# DuetReference.net
KiCad netlist of a schematic drawn in EAGLE
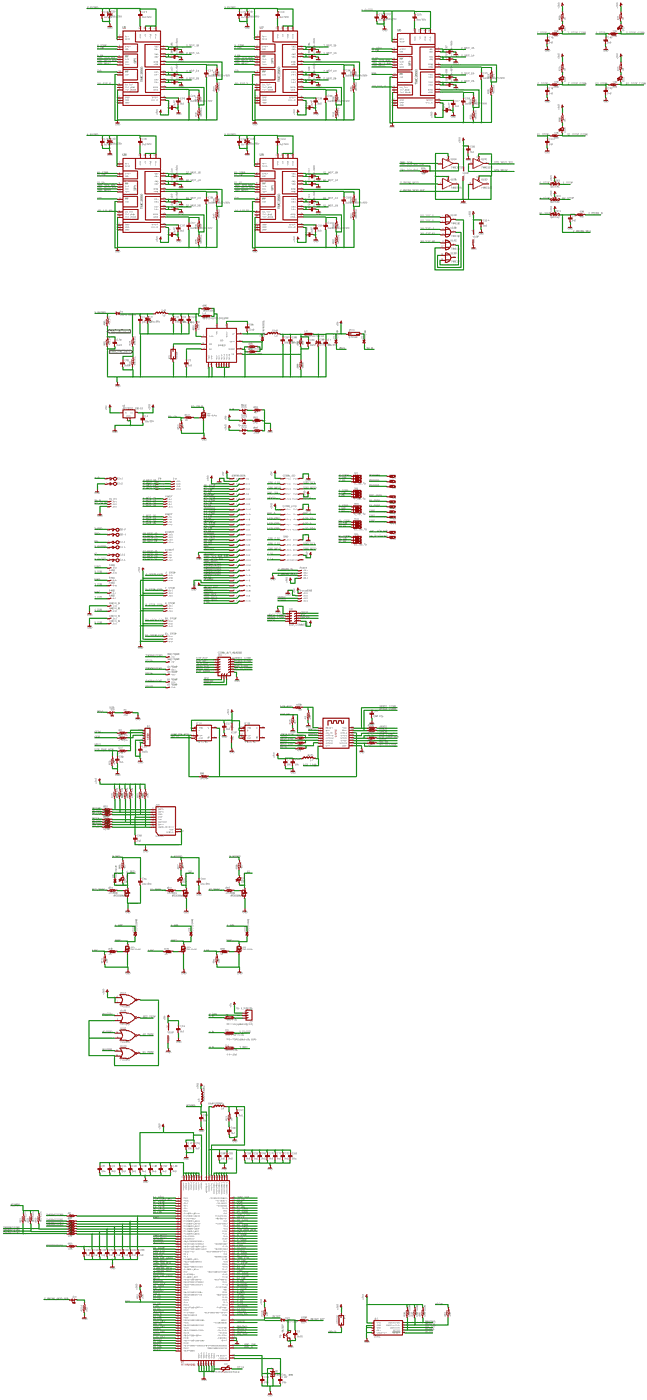
[diagram p0: schematic, sheet 1, overview]
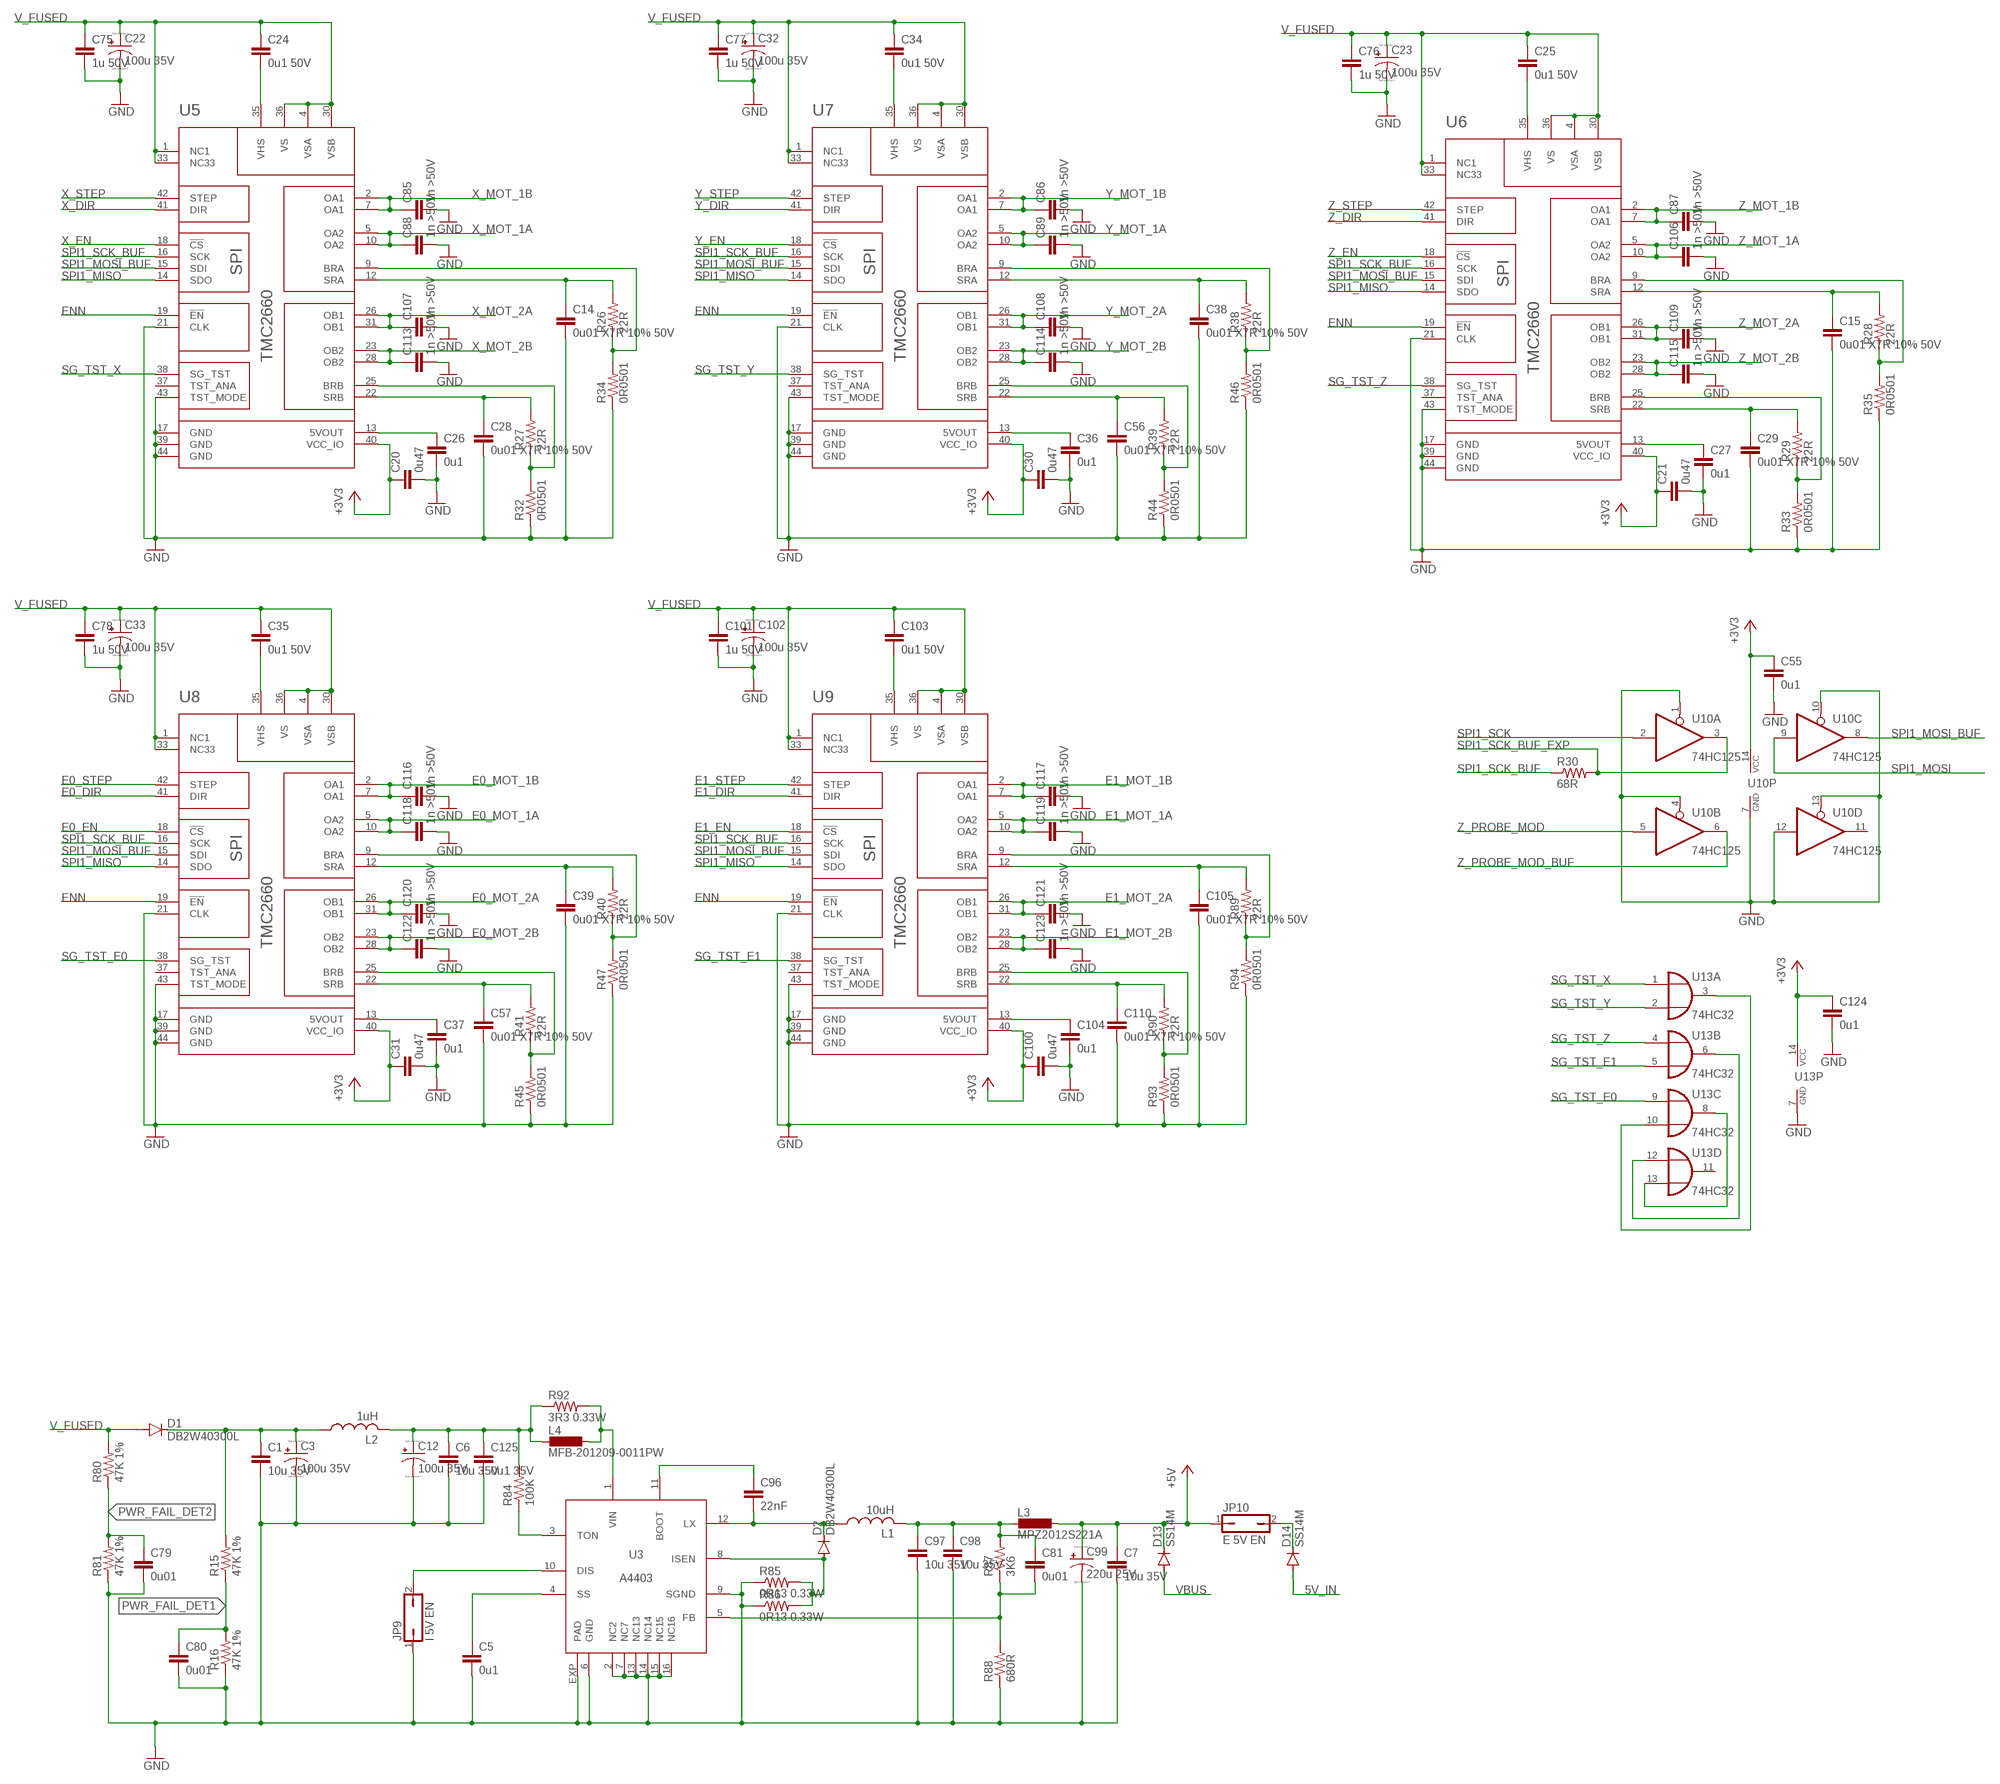
[diagram p1: schematic, sheet 1, part 1 of 5]
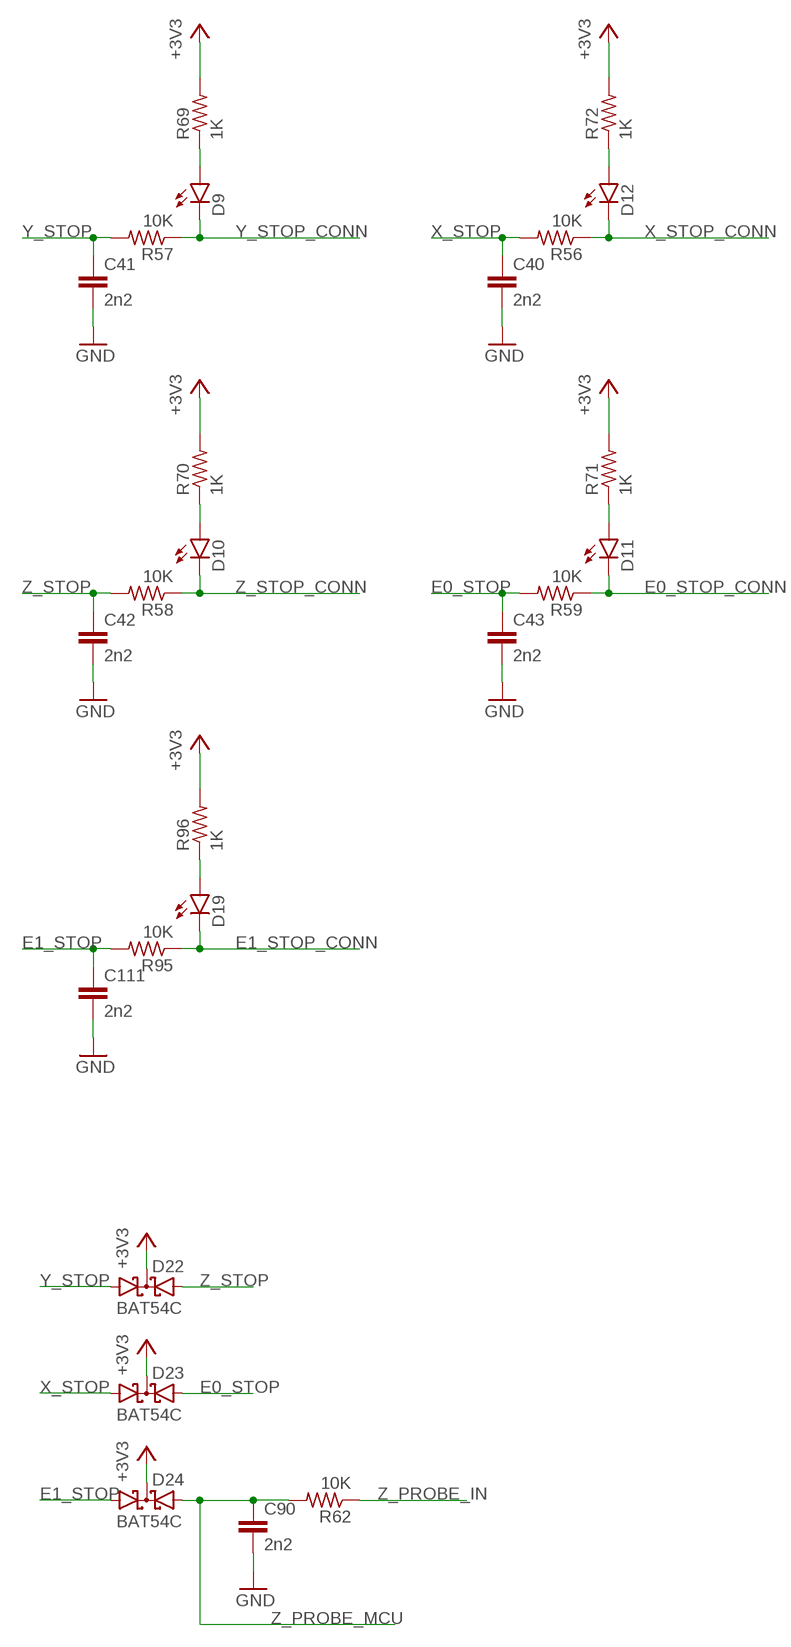
[diagram p2: schematic, sheet 1, part 2 of 5]
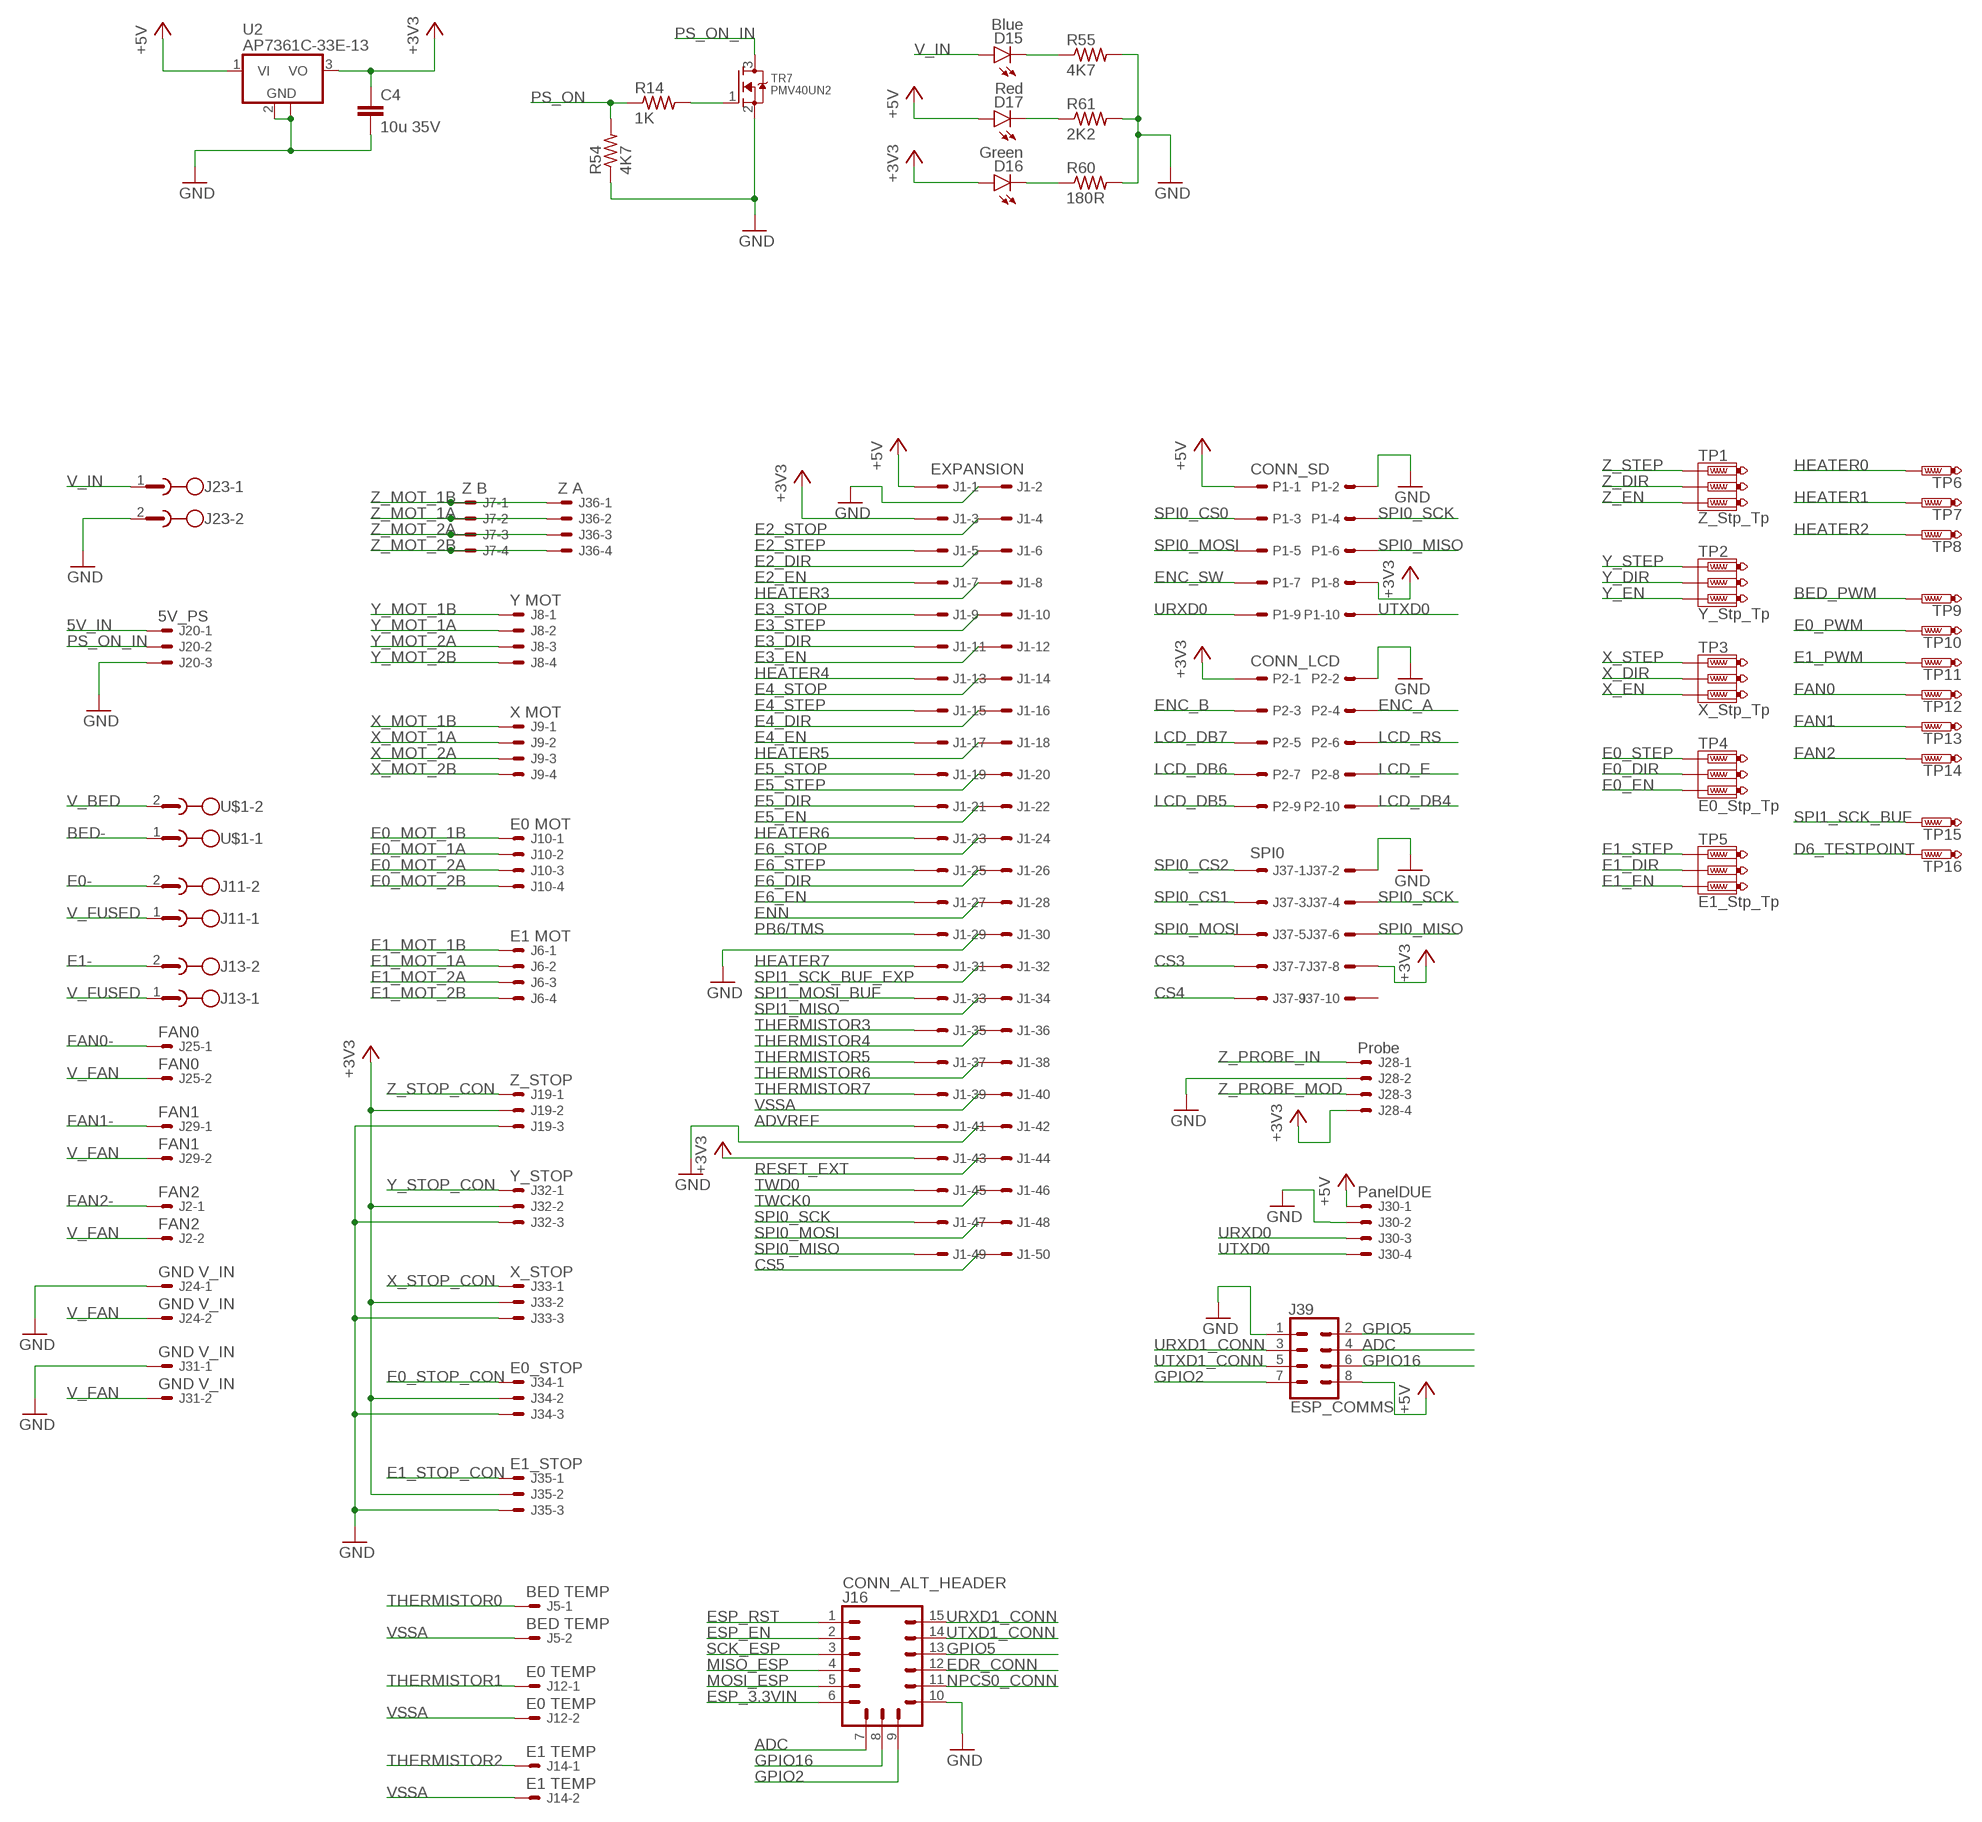
[diagram p3: schematic, sheet 1, part 3 of 5]
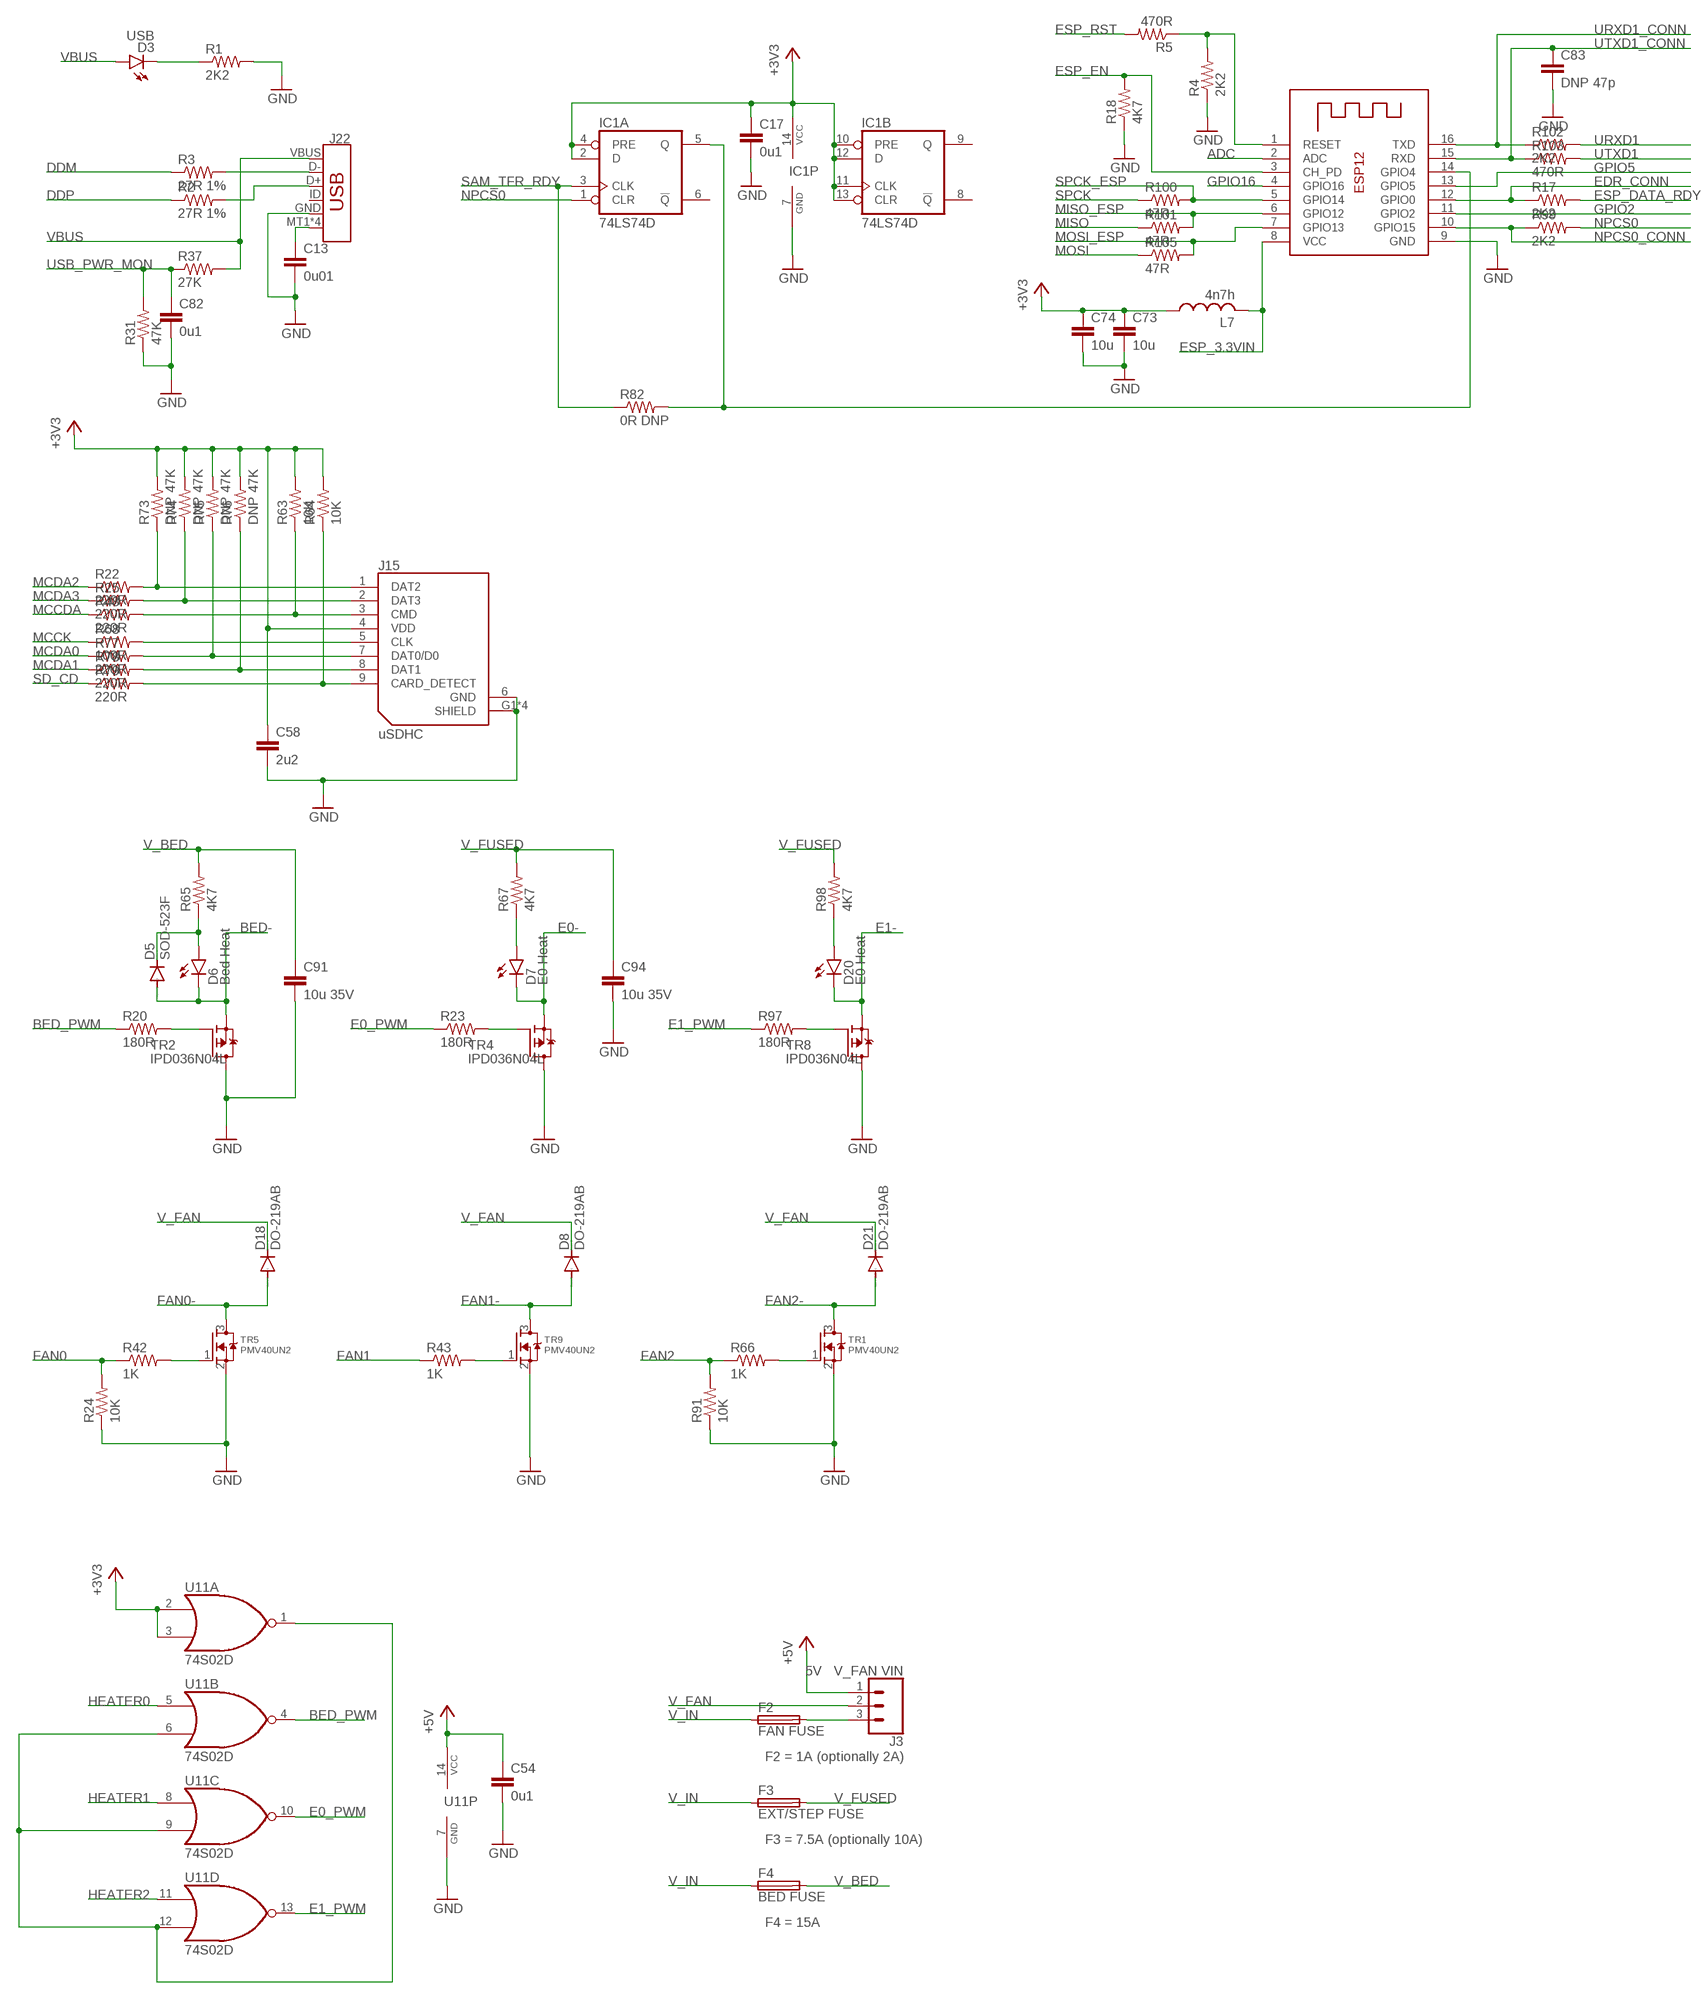
[diagram p4: schematic, sheet 1, part 4 of 5]
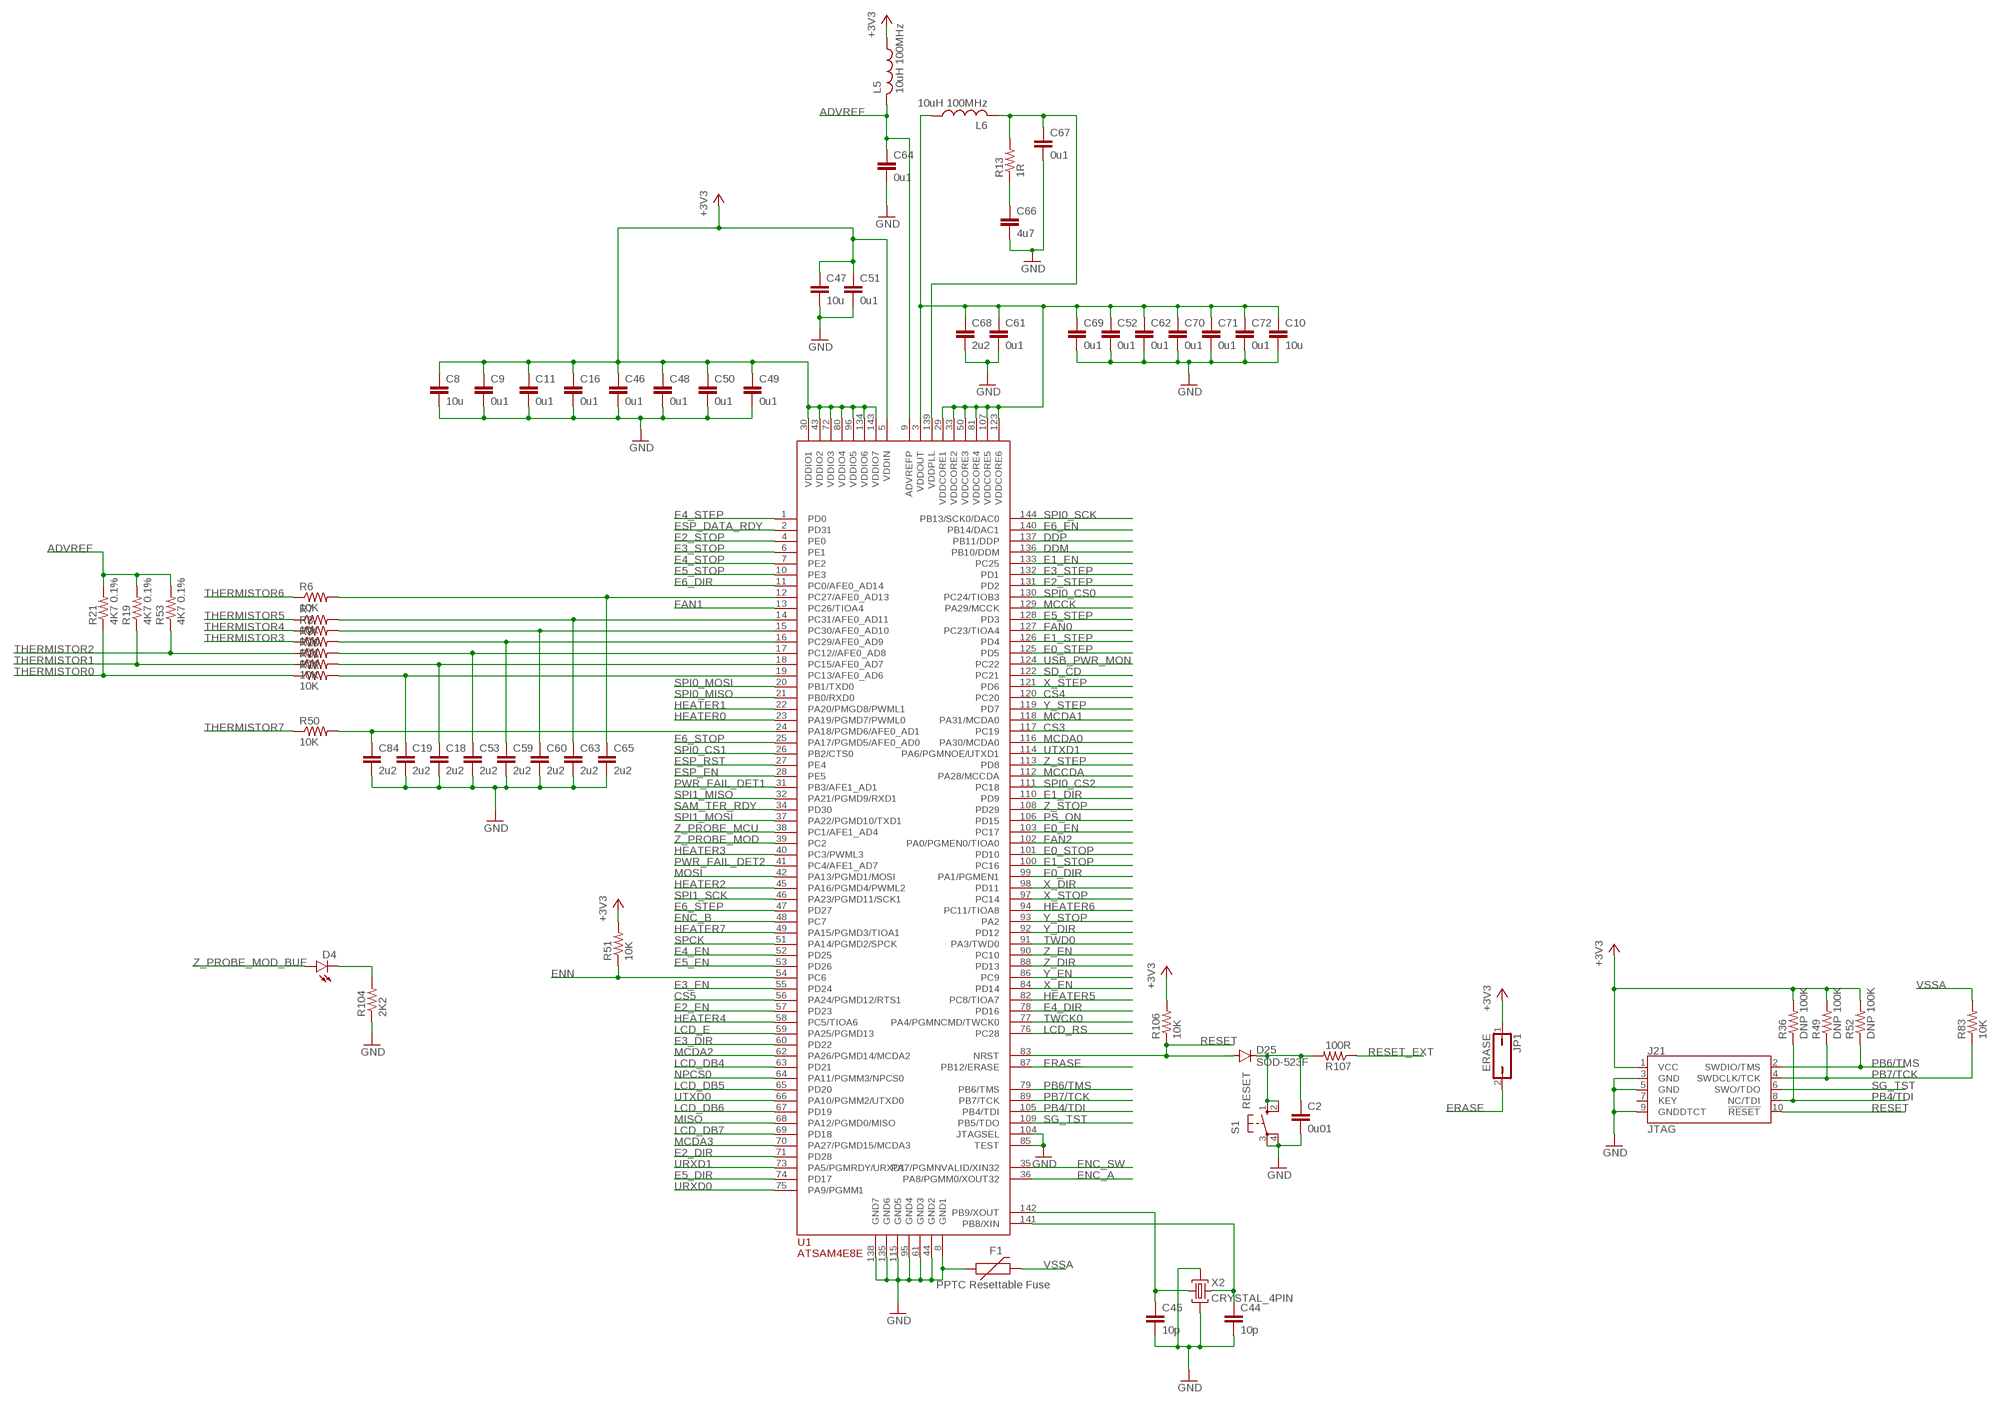
[diagram p5: schematic, sheet 1, part 5 of 5]

(export (version "E")
  (design (tool "Eeschema 10.0.6"))
  (components
    (comp (ref "C1")
      (value "10u 35V")
      (footprint "eagle-import:C0805")
      (libsource (lib "eagle-import") (part "C-EUC0805"))
    )
    (comp (ref "C2")
      (value "0u01")
      (footprint "eagle-import:C0805")
      (libsource (lib "eagle-import") (part "C-EUC0805"))
    )
    (comp (ref "C3")
      (value "100u 35V")
      (footprint "eagle-import:PANASONIC_D")
      (libsource (lib "eagle-import") (part "CPOL-USD"))
    )
    (comp (ref "C4")
      (value "10u 35V")
      (footprint "eagle-import:C0805")
      (libsource (lib "eagle-import") (part "C-EUC0805"))
    )
    (comp (ref "C5")
      (value "0u1")
      (footprint "eagle-import:C0805")
      (libsource (lib "eagle-import") (part "C-EUC0805"))
    )
    (comp (ref "C6")
      (value "10u 35V")
      (footprint "eagle-import:C0805")
      (libsource (lib "eagle-import") (part "C-EUC0805"))
    )
    (comp (ref "C7")
      (value "10u 35V")
      (footprint "eagle-import:C0805")
      (libsource (lib "eagle-import") (part "C-EUC0805"))
    )
    (comp (ref "C8")
      (value "10u")
      (footprint "eagle-import:C0805")
      (libsource (lib "eagle-import") (part "C-EUC0805"))
    )
    (comp (ref "C9")
      (value "0u1")
      (footprint "eagle-import:C0805")
      (libsource (lib "eagle-import") (part "C-EUC0805"))
    )
    (comp (ref "C10")
      (value "10u")
      (footprint "eagle-import:C0805")
      (libsource (lib "eagle-import") (part "C-EUC0805"))
    )
    (comp (ref "C11")
      (value "0u1")
      (footprint "eagle-import:C0805")
      (libsource (lib "eagle-import") (part "C-EUC0805"))
    )
    (comp (ref "C12")
      (value "100u 35V")
      (footprint "eagle-import:PANASONIC_D")
      (libsource (lib "eagle-import") (part "CPOL-USD"))
    )
    (comp (ref "C13")
      (value "0u01")
      (footprint "eagle-import:C0805")
      (libsource (lib "eagle-import") (part "C-EUC0805"))
    )
    (comp (ref "C14")
      (value "0u01 X7R 10% 50V")
      (footprint "eagle-import:C0805")
      (libsource (lib "eagle-import") (part "C-EUC0805"))
    )
    (comp (ref "C15")
      (value "0u01 X7R 10% 50V")
      (footprint "eagle-import:C0805")
      (libsource (lib "eagle-import") (part "C-EUC0805"))
    )
    (comp (ref "C16")
      (value "0u1")
      (footprint "eagle-import:C0805")
      (libsource (lib "eagle-import") (part "C-EUC0805"))
    )
    (comp (ref "C17")
      (value "0u1")
      (footprint "eagle-import:C0805")
      (libsource (lib "eagle-import") (part "C-EUC0805"))
    )
    (comp (ref "C18")
      (value "2u2")
      (footprint "eagle-import:C0805")
      (libsource (lib "eagle-import") (part "C-EUC0805"))
    )
    (comp (ref "C19")
      (value "2u2")
      (footprint "eagle-import:C0805")
      (libsource (lib "eagle-import") (part "C-EUC0805"))
    )
    (comp (ref "C20")
      (value "0u47")
      (footprint "eagle-import:C0805")
      (libsource (lib "eagle-import") (part "C-EUC0805"))
    )
    (comp (ref "C21")
      (value "0u47")
      (footprint "eagle-import:C0805")
      (libsource (lib "eagle-import") (part "C-EUC0805"))
    )
    (comp (ref "C22")
      (value "100u 35V")
      (footprint "eagle-import:PANASONIC_D")
      (libsource (lib "eagle-import") (part "CPOL-USD"))
    )
    (comp (ref "C23")
      (value "100u 35V")
      (footprint "eagle-import:PANASONIC_D")
      (libsource (lib "eagle-import") (part "CPOL-USD"))
    )
    (comp (ref "C24")
      (value "0u1 50V")
      (footprint "eagle-import:C0805")
      (libsource (lib "eagle-import") (part "C-EUC0805"))
    )
    (comp (ref "C25")
      (value "0u1 50V")
      (footprint "eagle-import:C0805")
      (libsource (lib "eagle-import") (part "C-EUC0805"))
    )
    (comp (ref "C26")
      (value "0u1")
      (footprint "eagle-import:C0805")
      (libsource (lib "eagle-import") (part "C-EUC0805"))
    )
    (comp (ref "C27")
      (value "0u1")
      (footprint "eagle-import:C0805")
      (libsource (lib "eagle-import") (part "C-EUC0805"))
    )
    (comp (ref "C28")
      (value "0u01 X7R 10% 50V")
      (footprint "eagle-import:C0805")
      (libsource (lib "eagle-import") (part "C-EUC0805"))
    )
    (comp (ref "C29")
      (value "0u01 X7R 10% 50V")
      (footprint "eagle-import:C0805")
      (libsource (lib "eagle-import") (part "C-EUC0805"))
    )
    (comp (ref "C30")
      (value "0u47")
      (footprint "eagle-import:C0805")
      (libsource (lib "eagle-import") (part "C-EUC0805"))
    )
    (comp (ref "C31")
      (value "0u47")
      (footprint "eagle-import:C0805")
      (libsource (lib "eagle-import") (part "C-EUC0805"))
    )
    (comp (ref "C32")
      (value "100u 35V")
      (footprint "eagle-import:PANASONIC_D")
      (libsource (lib "eagle-import") (part "CPOL-USD"))
    )
    (comp (ref "C33")
      (value "100u 35V")
      (footprint "eagle-import:PANASONIC_D")
      (libsource (lib "eagle-import") (part "CPOL-USD"))
    )
    (comp (ref "C34")
      (value "0u1 50V")
      (footprint "eagle-import:C0805")
      (libsource (lib "eagle-import") (part "C-EUC0805"))
    )
    (comp (ref "C35")
      (value "0u1 50V")
      (footprint "eagle-import:C0805")
      (libsource (lib "eagle-import") (part "C-EUC0805"))
    )
    (comp (ref "C36")
      (value "0u1")
      (footprint "eagle-import:C0805")
      (libsource (lib "eagle-import") (part "C-EUC0805"))
    )
    (comp (ref "C37")
      (value "0u1")
      (footprint "eagle-import:C0805")
      (libsource (lib "eagle-import") (part "C-EUC0805"))
    )
    (comp (ref "C38")
      (value "0u01 X7R 10% 50V")
      (footprint "eagle-import:C0805")
      (libsource (lib "eagle-import") (part "C-EUC0805"))
    )
    (comp (ref "C39")
      (value "0u01 X7R 10% 50V")
      (footprint "eagle-import:C0805")
      (libsource (lib "eagle-import") (part "C-EUC0805"))
    )
    (comp (ref "C40")
      (value "2n2")
      (footprint "eagle-import:C0805")
      (libsource (lib "eagle-import") (part "C-EUC0805"))
    )
    (comp (ref "C41")
      (value "2n2")
      (footprint "eagle-import:C0805")
      (libsource (lib "eagle-import") (part "C-EUC0805"))
    )
    (comp (ref "C42")
      (value "2n2")
      (footprint "eagle-import:C0805")
      (libsource (lib "eagle-import") (part "C-EUC0805"))
    )
    (comp (ref "C43")
      (value "2n2")
      (footprint "eagle-import:C0805")
      (libsource (lib "eagle-import") (part "C-EUC0805"))
    )
    (comp (ref "C44")
      (value "10p")
      (footprint "eagle-import:C0805")
      (libsource (lib "eagle-import") (part "C-EUC0805"))
    )
    (comp (ref "C45")
      (value "10p")
      (footprint "eagle-import:C0805")
      (libsource (lib "eagle-import") (part "C-EUC0805"))
    )
    (comp (ref "C46")
      (value "0u1")
      (footprint "eagle-import:C0805")
      (libsource (lib "eagle-import") (part "C-EUC0805"))
    )
    (comp (ref "C47")
      (value "10u")
      (footprint "eagle-import:C0805")
      (libsource (lib "eagle-import") (part "C-EUC0805"))
    )
    (comp (ref "C48")
      (value "0u1")
      (footprint "eagle-import:C0805")
      (libsource (lib "eagle-import") (part "C-EUC0805"))
    )
    (comp (ref "C49")
      (value "0u1")
      (footprint "eagle-import:C0805")
      (libsource (lib "eagle-import") (part "C-EUC0805"))
    )
    (comp (ref "C50")
      (value "0u1")
      (footprint "eagle-import:C0805")
      (libsource (lib "eagle-import") (part "C-EUC0805"))
    )
    (comp (ref "C51")
      (value "0u1")
      (footprint "eagle-import:C0805")
      (libsource (lib "eagle-import") (part "C-EUC0805"))
    )
    (comp (ref "C52")
      (value "0u1")
      (footprint "eagle-import:C0805")
      (libsource (lib "eagle-import") (part "C-EUC0805"))
    )
    (comp (ref "C53")
      (value "2u2")
      (footprint "eagle-import:C0805")
      (libsource (lib "eagle-import") (part "C-EUC0805"))
    )
    (comp (ref "C54")
      (value "0u1")
      (footprint "eagle-import:C0805")
      (libsource (lib "eagle-import") (part "C-EUC0805"))
    )
    (comp (ref "C55")
      (value "0u1")
      (footprint "eagle-import:C0805")
      (libsource (lib "eagle-import") (part "C-EUC0805"))
    )
    (comp (ref "C56")
      (value "0u01 X7R 10% 50V")
      (footprint "eagle-import:C0805")
      (libsource (lib "eagle-import") (part "C-EUC0805"))
    )
    (comp (ref "C57")
      (value "0u01 X7R 10% 50V")
      (footprint "eagle-import:C0805")
      (libsource (lib "eagle-import") (part "C-EUC0805"))
    )
    (comp (ref "C58")
      (value "2u2")
      (footprint "eagle-import:C0805")
      (libsource (lib "eagle-import") (part "C-EUC0805"))
    )
    (comp (ref "C59")
      (value "2u2")
      (footprint "eagle-import:C0805")
      (libsource (lib "eagle-import") (part "C-EUC0805"))
    )
    (comp (ref "C60")
      (value "2u2")
      (footprint "eagle-import:C0805")
      (libsource (lib "eagle-import") (part "C-EUC0805"))
    )
    (comp (ref "C61")
      (value "0u1")
      (footprint "eagle-import:C0805")
      (libsource (lib "eagle-import") (part "C-EUC0805"))
    )
    (comp (ref "C62")
      (value "0u1")
      (footprint "eagle-import:C0805")
      (libsource (lib "eagle-import") (part "C-EUC0805"))
    )
    (comp (ref "C63")
      (value "2u2")
      (footprint "eagle-import:C0805")
      (libsource (lib "eagle-import") (part "C-EUC0805"))
    )
    (comp (ref "C64")
      (value "0u1")
      (footprint "eagle-import:C0805")
      (libsource (lib "eagle-import") (part "C-EUC0805"))
    )
    (comp (ref "C65")
      (value "2u2")
      (footprint "eagle-import:C0805")
      (libsource (lib "eagle-import") (part "C-EUC0805"))
    )
    (comp (ref "C66")
      (value "4u7")
      (footprint "eagle-import:C0805")
      (libsource (lib "eagle-import") (part "C-EUC0805"))
    )
    (comp (ref "C67")
      (value "0u1")
      (footprint "eagle-import:C0805")
      (libsource (lib "eagle-import") (part "C-EUC0805"))
    )
    (comp (ref "C68")
      (value "2u2")
      (footprint "eagle-import:C0805")
      (libsource (lib "eagle-import") (part "C-EUC0805"))
    )
    (comp (ref "C69")
      (value "0u1")
      (footprint "eagle-import:C0805")
      (libsource (lib "eagle-import") (part "C-EUC0805"))
    )
    (comp (ref "C70")
      (value "0u1")
      (footprint "eagle-import:C0805")
      (libsource (lib "eagle-import") (part "C-EUC0805"))
    )
    (comp (ref "C71")
      (value "0u1")
      (footprint "eagle-import:C0805")
      (libsource (lib "eagle-import") (part "C-EUC0805"))
    )
    (comp (ref "C72")
      (value "0u1")
      (footprint "eagle-import:C0805")
      (libsource (lib "eagle-import") (part "C-EUC0805"))
    )
    (comp (ref "C73")
      (value "10u")
      (footprint "eagle-import:C0805")
      (libsource (lib "eagle-import") (part "C-EUC0805"))
    )
    (comp (ref "C74")
      (value "10u")
      (footprint "eagle-import:C0805")
      (libsource (lib "eagle-import") (part "C-EUC0805"))
    )
    (comp (ref "C75")
      (value "1u 50V")
      (footprint "eagle-import:C0805")
      (libsource (lib "eagle-import") (part "C-EUC0805"))
    )
    (comp (ref "C76")
      (value "1u 50V")
      (footprint "eagle-import:C0805")
      (libsource (lib "eagle-import") (part "C-EUC0805"))
    )
    (comp (ref "C77")
      (value "1u 50V")
      (footprint "eagle-import:C0805")
      (libsource (lib "eagle-import") (part "C-EUC0805"))
    )
    (comp (ref "C78")
      (value "1u 50V")
      (footprint "eagle-import:C0805")
      (libsource (lib "eagle-import") (part "C-EUC0805"))
    )
    (comp (ref "C79")
      (value "0u01")
      (footprint "eagle-import:C0805")
      (libsource (lib "eagle-import") (part "C-EUC0805"))
    )
    (comp (ref "C80")
      (value "0u01")
      (footprint "eagle-import:C0805")
      (libsource (lib "eagle-import") (part "C-EUC0805"))
    )
    (comp (ref "C81")
      (value "0u01")
      (footprint "eagle-import:C0805")
      (libsource (lib "eagle-import") (part "C-EUC0805"))
    )
    (comp (ref "C82")
      (value "0u1")
      (footprint "eagle-import:C0805")
      (libsource (lib "eagle-import") (part "C-EUC0805"))
    )
    (comp (ref "C83")
      (value "DNP 47p")
      (footprint "eagle-import:C0805")
      (libsource (lib "eagle-import") (part "C-EUC0805"))
    )
    (comp (ref "C84")
      (value "2u2")
      (footprint "eagle-import:C0805")
      (libsource (lib "eagle-import") (part "C-EUC0805"))
    )
    (comp (ref "C85")
      (value "1n >50V")
      (footprint "eagle-import:C0805")
      (libsource (lib "eagle-import") (part "C-EUC0805"))
    )
    (comp (ref "C86")
      (value "1n >50V")
      (footprint "eagle-import:C0805")
      (libsource (lib "eagle-import") (part "C-EUC0805"))
    )
    (comp (ref "C87")
      (value "1n >50V")
      (footprint "eagle-import:C0805")
      (libsource (lib "eagle-import") (part "C-EUC0805"))
    )
    (comp (ref "C88")
      (value "1n >50V")
      (footprint "eagle-import:C0805")
      (libsource (lib "eagle-import") (part "C-EUC0805"))
    )
    (comp (ref "C89")
      (value "1n >50V")
      (footprint "eagle-import:C0805")
      (libsource (lib "eagle-import") (part "C-EUC0805"))
    )
    (comp (ref "C90")
      (value "2n2")
      (footprint "eagle-import:C0805")
      (libsource (lib "eagle-import") (part "C-EUC0805"))
    )
    (comp (ref "C91")
      (value "10u 35V")
      (footprint "eagle-import:C0805")
      (libsource (lib "eagle-import") (part "C-EUC0805"))
    )
    (comp (ref "C94")
      (value "10u 35V")
      (footprint "eagle-import:C0805")
      (libsource (lib "eagle-import") (part "C-EUC0805"))
    )
    (comp (ref "C96")
      (value "22nF")
      (footprint "eagle-import:C0805")
      (libsource (lib "eagle-import") (part "C-EUC0805"))
    )
    (comp (ref "C97")
      (value "10u 35V")
      (footprint "eagle-import:C0805")
      (libsource (lib "eagle-import") (part "C-EUC0805"))
    )
    (comp (ref "C98")
      (value "10u 35V")
      (footprint "eagle-import:C0805")
      (libsource (lib "eagle-import") (part "C-EUC0805"))
    )
    (comp (ref "C99")
      (value "220u 25V")
      (footprint "eagle-import:PANASONIC_D")
      (libsource (lib "eagle-import") (part "CPOL-USD"))
    )
    (comp (ref "C100")
      (value "0u47")
      (footprint "eagle-import:C0805")
      (libsource (lib "eagle-import") (part "C-EUC0805"))
    )
    (comp (ref "C101")
      (value "1u 50V")
      (footprint "eagle-import:C0805")
      (libsource (lib "eagle-import") (part "C-EUC0805"))
    )
    (comp (ref "C102")
      (value "100u 35V")
      (footprint "eagle-import:PANASONIC_D")
      (libsource (lib "eagle-import") (part "CPOL-USD"))
    )
    (comp (ref "C103")
      (value "0u1 50V")
      (footprint "eagle-import:C0805")
      (libsource (lib "eagle-import") (part "C-EUC0805"))
    )
    (comp (ref "C104")
      (value "0u1")
      (footprint "eagle-import:C0805")
      (libsource (lib "eagle-import") (part "C-EUC0805"))
    )
    (comp (ref "C105")
      (value "0u01 X7R 10% 50V")
      (footprint "eagle-import:C0805")
      (libsource (lib "eagle-import") (part "C-EUC0805"))
    )
    (comp (ref "C106")
      (value "1n >50V")
      (footprint "eagle-import:C0805")
      (libsource (lib "eagle-import") (part "C-EUC0805"))
    )
    (comp (ref "C107")
      (value "1n >50V")
      (footprint "eagle-import:C0805")
      (libsource (lib "eagle-import") (part "C-EUC0805"))
    )
    (comp (ref "C108")
      (value "1n >50V")
      (footprint "eagle-import:C0805")
      (libsource (lib "eagle-import") (part "C-EUC0805"))
    )
    (comp (ref "C109")
      (value "1n >50V")
      (footprint "eagle-import:C0805")
      (libsource (lib "eagle-import") (part "C-EUC0805"))
    )
    (comp (ref "C110")
      (value "0u01 X7R 10% 50V")
      (footprint "eagle-import:C0805")
      (libsource (lib "eagle-import") (part "C-EUC0805"))
    )
    (comp (ref "C111")
      (value "2n2")
      (footprint "eagle-import:C0805")
      (libsource (lib "eagle-import") (part "C-EUC0805"))
    )
    (comp (ref "C113")
      (value "1n >50V")
      (footprint "eagle-import:C0805")
      (libsource (lib "eagle-import") (part "C-EUC0805"))
    )
    (comp (ref "C114")
      (value "1n >50V")
      (footprint "eagle-import:C0805")
      (libsource (lib "eagle-import") (part "C-EUC0805"))
    )
    (comp (ref "C115")
      (value "1n >50V")
      (footprint "eagle-import:C0805")
      (libsource (lib "eagle-import") (part "C-EUC0805"))
    )
    (comp (ref "C116")
      (value "1n >50V")
      (footprint "eagle-import:C0805")
      (libsource (lib "eagle-import") (part "C-EUC0805"))
    )
    (comp (ref "C117")
      (value "1n >50V")
      (footprint "eagle-import:C0805")
      (libsource (lib "eagle-import") (part "C-EUC0805"))
    )
    (comp (ref "C118")
      (value "1n >50V")
      (footprint "eagle-import:C0805")
      (libsource (lib "eagle-import") (part "C-EUC0805"))
    )
    (comp (ref "C119")
      (value "1n >50V")
      (footprint "eagle-import:C0805")
      (libsource (lib "eagle-import") (part "C-EUC0805"))
    )
    (comp (ref "C120")
      (value "1n >50V")
      (footprint "eagle-import:C0805")
      (libsource (lib "eagle-import") (part "C-EUC0805"))
    )
    (comp (ref "C121")
      (value "1n >50V")
      (footprint "eagle-import:C0805")
      (libsource (lib "eagle-import") (part "C-EUC0805"))
    )
    (comp (ref "C122")
      (value "1n >50V")
      (footprint "eagle-import:C0805")
      (libsource (lib "eagle-import") (part "C-EUC0805"))
    )
    (comp (ref "C123")
      (value "1n >50V")
      (footprint "eagle-import:C0805")
      (libsource (lib "eagle-import") (part "C-EUC0805"))
    )
    (comp (ref "C124")
      (value "0u1")
      (footprint "eagle-import:C0805")
      (libsource (lib "eagle-import") (part "C-EUC0805"))
    )
    (comp (ref "C125")
      (value "0u1 35V")
      (footprint "eagle-import:C0805")
      (libsource (lib "eagle-import") (part "C-EUC0805"))
    )
    (comp (ref "D1")
      (value "DB2W40300L")
      (footprint "eagle-import:SOD123")
      (libsource (lib "eagle-import") (part "DIODE-SOD123"))
    )
    (comp (ref "D2")
      (value "DB2W40300L")
      (footprint "eagle-import:SOD123")
      (libsource (lib "eagle-import") (part "DIODE-SOD123"))
    )
    (comp (ref "D3")
      (value "USB")
      (footprint "eagle-import:CHIPLED_0805")
      (libsource (lib "eagle-import") (part "LEDCHIPLED_0805"))
    )
    (comp (ref "D4")
      (value "LEDCHIPLED_0805")
      (footprint "eagle-import:CHIPLED_0805")
      (libsource (lib "eagle-import") (part "LEDCHIPLED_0805"))
    )
    (comp (ref "D5")
      (value "SOD-523F")
      (footprint "eagle-import:SOD523")
      (libsource (lib "eagle-import") (part "DIODE-SOD523"))
    )
    (comp (ref "D6")
      (value "Bed Heat")
      (footprint "eagle-import:CHIPLED_0805")
      (libsource (lib "eagle-import") (part "LEDCHIPLED_0805"))
    )
    (comp (ref "D7")
      (value "E0 Heat")
      (footprint "eagle-import:CHIPLED_0805")
      (libsource (lib "eagle-import") (part "LEDCHIPLED_0805"))
    )
    (comp (ref "D8")
      (value "DO-219AB")
      (footprint "eagle-import:SOD123")
      (libsource (lib "eagle-import") (part "DIODE-SOD123"))
    )
    (comp (ref "D9")
      (value "LEDCHIPLED_0805")
      (footprint "eagle-import:CHIPLED_0805")
      (libsource (lib "eagle-import") (part "LEDCHIPLED_0805"))
    )
    (comp (ref "D10")
      (value "LEDCHIPLED_0805")
      (footprint "eagle-import:CHIPLED_0805")
      (libsource (lib "eagle-import") (part "LEDCHIPLED_0805"))
    )
    (comp (ref "D11")
      (value "LEDCHIPLED_0805")
      (footprint "eagle-import:CHIPLED_0805")
      (libsource (lib "eagle-import") (part "LEDCHIPLED_0805"))
    )
    (comp (ref "D12")
      (value "LEDCHIPLED_0805")
      (footprint "eagle-import:CHIPLED_0805")
      (libsource (lib "eagle-import") (part "LEDCHIPLED_0805"))
    )
    (comp (ref "D13")
      (value "SS14M")
      (footprint "eagle-import:SMA")
      (libsource (lib "eagle-import") (part "S1M"))
    )
    (comp (ref "D14")
      (value "SS14M")
      (footprint "eagle-import:SMA")
      (libsource (lib "eagle-import") (part "S1M"))
    )
    (comp (ref "D15")
      (value "Blue")
      (footprint "eagle-import:CHIPLED_0805")
      (libsource (lib "eagle-import") (part "LEDCHIPLED_0805"))
    )
    (comp (ref "D16")
      (value "Green")
      (footprint "eagle-import:CHIPLED_0805")
      (libsource (lib "eagle-import") (part "LEDCHIPLED_0805"))
    )
    (comp (ref "D17")
      (value "Red")
      (footprint "eagle-import:CHIPLED_0805")
      (libsource (lib "eagle-import") (part "LEDCHIPLED_0805"))
    )
    (comp (ref "D18")
      (value "DO-219AB")
      (footprint "eagle-import:SOD123")
      (libsource (lib "eagle-import") (part "DIODE-SOD123"))
    )
    (comp (ref "D19")
      (value "LEDCHIPLED_0805")
      (footprint "eagle-import:CHIPLED_0805")
      (libsource (lib "eagle-import") (part "LEDCHIPLED_0805"))
    )
    (comp (ref "D20")
      (value "E0 Heat")
      (footprint "eagle-import:CHIPLED_0805")
      (libsource (lib "eagle-import") (part "LEDCHIPLED_0805"))
    )
    (comp (ref "D21")
      (value "DO-219AB")
      (footprint "eagle-import:SOD123")
      (libsource (lib "eagle-import") (part "DIODE-SOD123"))
    )
    (comp (ref "D22")
      (value "BAT54C")
      (footprint "eagle-import:SOT23")
      (libsource (lib "eagle-import") (part "BAT54C"))
    )
    (comp (ref "D23")
      (value "BAT54C")
      (footprint "eagle-import:SOT23")
      (libsource (lib "eagle-import") (part "BAT54C"))
    )
    (comp (ref "D24")
      (value "BAT54C")
      (footprint "eagle-import:SOT23")
      (libsource (lib "eagle-import") (part "BAT54C"))
    )
    (comp (ref "D25")
      (value "SOD-523F")
      (footprint "eagle-import:SOD523")
      (libsource (lib "eagle-import") (part "DIODE-SOD523"))
    )
    (comp (ref "F1")
      (value "PPTC Resettable Fuse")
      (footprint "eagle-import:1206")
      (libsource (lib "eagle-import") (part "PPTC_HALF-AMP"))
    )
    (comp (ref "F2")
      (value "FAN FUSE")
      (footprint "eagle-import:LITTLEFUSE")
      (libsource (lib "eagle-import") (part "FUSELITTLEFUSE"))
    )
    (comp (ref "F3")
      (value "EXT/STEP FUSE")
      (footprint "eagle-import:LITTLEFUSE")
      (libsource (lib "eagle-import") (part "FUSELITTLEFUSE"))
    )
    (comp (ref "F4")
      (value "BED FUSE")
      (footprint "eagle-import:LITTLEFUSE")
      (libsource (lib "eagle-import") (part "FUSELITTLEFUSE"))
    )
    (comp (ref "IC1")
      (value "74LS74D")
      (footprint "eagle-import:SO14")
      (libsource (lib "eagle-import") (part "7474DLS"))
    )
    (comp (ref "J1")
      (value "EXPANSION")
      (footprint "eagle-import:057-050-1")
      (libsource (lib "eagle-import") (part "057-050-1"))
    )
    (comp (ref "J2")
      (value "FAN2")
      (footprint "eagle-import:KK-156-2")
      (fields (field (name "MF") "MOLEX"))
      (libsource (lib "eagle-import") (part "KK-156-2"))
    )
    (comp (ref "J3")
      (value "5V V_FAN VIN")
      (footprint "eagle-import:1X03")
      (libsource (lib "eagle-import") (part "CONN_03"))
    )
    (comp (ref "J5")
      (value "BED TEMP")
      (footprint "eagle-import:KK-156-2")
      (fields (field (name "MF") "MOLEX"))
      (libsource (lib "eagle-import") (part "KK-156-2"))
    )
    (comp (ref "J6")
      (value "E1 MOT")
      (footprint "eagle-import:KK-156-4")
      (fields (field (name "MF") "MOLEX"))
      (libsource (lib "eagle-import") (part "KK-156-4"))
    )
    (comp (ref "J7")
      (value "Z B")
      (footprint "eagle-import:KK-156-4")
      (fields (field (name "MF") "MOLEX"))
      (libsource (lib "eagle-import") (part "KK-156-4"))
    )
    (comp (ref "J8")
      (value "Y MOT")
      (footprint "eagle-import:KK-156-4")
      (fields (field (name "MF") "MOLEX"))
      (libsource (lib "eagle-import") (part "KK-156-4"))
    )
    (comp (ref "J9")
      (value "X MOT")
      (footprint "eagle-import:KK-156-4")
      (fields (field (name "MF") "MOLEX"))
      (libsource (lib "eagle-import") (part "KK-156-4"))
    )
    (comp (ref "J10")
      (value "E0 MOT")
      (footprint "eagle-import:KK-156-4")
      (fields (field (name "MF") "MOLEX"))
      (libsource (lib "eagle-import") (part "KK-156-4"))
    )
    (comp (ref "J11")
      (value "E0 HEAT")
      (footprint "eagle-import:2-PIN-350")
      (libsource (lib "eagle-import") (part "2-PIN-350"))
    )
    (comp (ref "J12")
      (value "E0 TEMP")
      (footprint "eagle-import:KK-156-2")
      (fields (field (name "MF") "MOLEX"))
      (libsource (lib "eagle-import") (part "KK-156-2"))
    )
    (comp (ref "J13")
      (value "2-PIN-350")
      (footprint "eagle-import:2-PIN-350")
      (libsource (lib "eagle-import") (part "2-PIN-350"))
    )
    (comp (ref "J14")
      (value "E1 TEMP")
      (footprint "eagle-import:KK-156-2")
      (fields (field (name "MF") "MOLEX"))
      (libsource (lib "eagle-import") (part "KK-156-2"))
    )
    (comp (ref "J15")
      (value "uSDHC")
      (footprint "eagle-import:USDHC")
      (libsource (lib "eagle-import") (part "USDHC"))
    )
    (comp (ref "J16")
      (value "CONN_ALT_HEADER")
      (footprint "eagle-import:CONN_ALT_HEADER")
      (libsource (lib "eagle-import") (part "CONN_ALT_HEADER"))
    )
    (comp (ref "J19")
      (value "Z_STOP")
      (footprint "eagle-import:KK-156-3")
      (fields (field (name "MF") "MOLEX"))
      (libsource (lib "eagle-import") (part "KK-156-3"))
    )
    (comp (ref "J20")
      (value "5V_PS")
      (footprint "eagle-import:KK-156-3")
      (fields (field (name "MF") "MOLEX"))
      (libsource (lib "eagle-import") (part "KK-156-3"))
    )
    (comp (ref "J21")
      (value "JTAG")
      (footprint "eagle-import:2X5-PTH-1.27MM")
      (libsource (lib "eagle-import") (part "CORTEX_DEBUG_PTH"))
    )
    (comp (ref "J22")
      (value "USB_MICRO-B_SMT")
      (footprint "eagle-import:USB-MICROB")
      (libsource (lib "eagle-import") (part "USB_MICRO-B_SMT"))
    )
    (comp (ref "J23")
      (value "VIN")
      (footprint "eagle-import:2-PIN-635")
      (libsource (lib "eagle-import") (part "2-PIN-635"))
    )
    (comp (ref "J24")
      (value "GND V_IN")
      (footprint "eagle-import:KK-156-2")
      (fields (field (name "MF") "MOLEX"))
      (libsource (lib "eagle-import") (part "KK-156-2"))
    )
    (comp (ref "J25")
      (value "FAN0")
      (footprint "eagle-import:KK-156-2")
      (fields (field (name "MF") "MOLEX"))
      (libsource (lib "eagle-import") (part "KK-156-2"))
    )
    (comp (ref "J28")
      (value "Probe")
      (footprint "eagle-import:KK-156-4")
      (fields (field (name "MF") "MOLEX"))
      (libsource (lib "eagle-import") (part "KK-156-4"))
    )
    (comp (ref "J29")
      (value "FAN1")
      (footprint "eagle-import:KK-156-2")
      (fields (field (name "MF") "MOLEX"))
      (libsource (lib "eagle-import") (part "KK-156-2"))
    )
    (comp (ref "J30")
      (value "PanelDUE")
      (footprint "eagle-import:KK-156-4")
      (fields (field (name "MF") "MOLEX"))
      (libsource (lib "eagle-import") (part "KK-156-4"))
    )
    (comp (ref "J31")
      (value "GND V_IN")
      (footprint "eagle-import:KK-156-2")
      (fields (field (name "MF") "MOLEX"))
      (libsource (lib "eagle-import") (part "KK-156-2"))
    )
    (comp (ref "J32")
      (value "Y_STOP")
      (footprint "eagle-import:KK-156-3")
      (fields (field (name "MF") "MOLEX"))
      (libsource (lib "eagle-import") (part "KK-156-3"))
    )
    (comp (ref "J33")
      (value "X_STOP")
      (footprint "eagle-import:KK-156-3")
      (fields (field (name "MF") "MOLEX"))
      (libsource (lib "eagle-import") (part "KK-156-3"))
    )
    (comp (ref "J34")
      (value "E0_STOP")
      (footprint "eagle-import:KK-156-3")
      (fields (field (name "MF") "MOLEX"))
      (libsource (lib "eagle-import") (part "KK-156-3"))
    )
    (comp (ref "J35")
      (value "E1_STOP")
      (footprint "eagle-import:KK-156-3")
      (fields (field (name "MF") "MOLEX"))
      (libsource (lib "eagle-import") (part "KK-156-3"))
    )
    (comp (ref "J36")
      (value "Z A")
      (footprint "eagle-import:KK-156-4")
      (fields (field (name "MF") "MOLEX"))
      (libsource (lib "eagle-import") (part "KK-156-4"))
    )
    (comp (ref "J37")
      (value "SPI0")
      (footprint "eagle-import:057-010-1")
      (libsource (lib "eagle-import") (part "057-010-1"))
    )
    (comp (ref "J39")
      (value "ESP_COMMS")
      (footprint "eagle-import:2X4")
      (libsource (lib "eagle-import") (part "CONN_04X2"))
    )
    (comp (ref "JP1")
      (value "ERASE")
      (footprint "eagle-import:JP1")
      (libsource (lib "eagle-import") (part "JP1Q"))
    )
    (comp (ref "JP9")
      (value "I 5V EN")
      (footprint "eagle-import:JP1")
      (libsource (lib "eagle-import") (part "JP1Q"))
    )
    (comp (ref "JP10")
      (value "E 5V EN")
      (footprint "eagle-import:JP1")
      (libsource (lib "eagle-import") (part "JP1Q"))
    )
    (comp (ref "L1")
      (value "10uH")
      (footprint "eagle-import:L1812")
      (libsource (lib "eagle-import") (part "L-USL1812"))
    )
    (comp (ref "L2")
      (value "1uH")
      (footprint "eagle-import:L1812")
      (libsource (lib "eagle-import") (part "L-USL1812"))
    )
    (comp (ref "L3")
      (value "MPZ2012S221A")
      (footprint "eagle-import:L2012C")
      (libsource (lib "eagle-import") (part "L-EUL2012C"))
    )
    (comp (ref "L4")
      (value "MFB-201209-0011PW")
      (footprint "eagle-import:L2012C")
      (libsource (lib "eagle-import") (part "L-EUL2012C"))
    )
    (comp (ref "L5")
      (value "10uH 100MHz")
      (footprint "eagle-import:L1812")
      (libsource (lib "eagle-import") (part "L-USL1812"))
    )
    (comp (ref "L6")
      (value "10uH 100MHz")
      (footprint "eagle-import:L1812")
      (libsource (lib "eagle-import") (part "L-USL1812"))
    )
    (comp (ref "L7")
      (value "4n7h")
      (footprint "eagle-import:L1812")
      (libsource (lib "eagle-import") (part "L-USL1812"))
    )
    (comp (ref "P1")
      (value "CONN_SD")
      (footprint "eagle-import:057-010-1")
      (libsource (lib "eagle-import") (part "057-010-1"))
    )
    (comp (ref "P2")
      (value "CONN_LCD")
      (footprint "eagle-import:057-010-1")
      (libsource (lib "eagle-import") (part "057-010-1"))
    )
    (comp (ref "R1")
      (value "2K2")
      (footprint "eagle-import:R0805")
      (libsource (lib "eagle-import") (part "R-US_R0805"))
    )
    (comp (ref "R2")
      (value "27R 1%")
      (footprint "eagle-import:R0805")
      (libsource (lib "eagle-import") (part "R-US_R0805"))
    )
    (comp (ref "R3")
      (value "27R 1%")
      (footprint "eagle-import:R0805")
      (libsource (lib "eagle-import") (part "R-US_R0805"))
    )
    (comp (ref "R4")
      (value "2K2")
      (footprint "eagle-import:R0805")
      (libsource (lib "eagle-import") (part "R-US_R0805"))
    )
    (comp (ref "R5")
      (value "470R")
      (footprint "eagle-import:R0805")
      (libsource (lib "eagle-import") (part "R-US_R0805"))
    )
    (comp (ref "R6")
      (value "10K")
      (footprint "eagle-import:R0805")
      (libsource (lib "eagle-import") (part "R-US_R0805"))
    )
    (comp (ref "R7")
      (value "10K")
      (footprint "eagle-import:R0805")
      (libsource (lib "eagle-import") (part "R-US_R0805"))
    )
    (comp (ref "R8")
      (value "10K")
      (footprint "eagle-import:R0805")
      (libsource (lib "eagle-import") (part "R-US_R0805"))
    )
    (comp (ref "R9")
      (value "10K")
      (footprint "eagle-import:R0805")
      (libsource (lib "eagle-import") (part "R-US_R0805"))
    )
    (comp (ref "R10")
      (value "10K")
      (footprint "eagle-import:R0805")
      (libsource (lib "eagle-import") (part "R-US_R0805"))
    )
    (comp (ref "R11")
      (value "10K")
      (footprint "eagle-import:R0805")
      (libsource (lib "eagle-import") (part "R-US_R0805"))
    )
    (comp (ref "R12")
      (value "10K")
      (footprint "eagle-import:R0805")
      (libsource (lib "eagle-import") (part "R-US_R0805"))
    )
    (comp (ref "R13")
      (value "1R")
      (footprint "eagle-import:R0805")
      (libsource (lib "eagle-import") (part "R-US_R0805"))
    )
    (comp (ref "R14")
      (value "1K")
      (footprint "eagle-import:R0805")
      (libsource (lib "eagle-import") (part "R-US_R0805"))
    )
    (comp (ref "R15")
      (value "47K 1%")
      (footprint "eagle-import:R0805")
      (libsource (lib "eagle-import") (part "R-US_R0805"))
    )
    (comp (ref "R16")
      (value "47K 1%")
      (footprint "eagle-import:R0805")
      (libsource (lib "eagle-import") (part "R-US_R0805"))
    )
    (comp (ref "R17")
      (value "2K2")
      (footprint "eagle-import:R0805")
      (libsource (lib "eagle-import") (part "R-US_R0805"))
    )
    (comp (ref "R18")
      (value "4K7")
      (footprint "eagle-import:R0805")
      (libsource (lib "eagle-import") (part "R-US_R0805"))
    )
    (comp (ref "R19")
      (value "4K7 0.1%")
      (footprint "eagle-import:R0805")
      (libsource (lib "eagle-import") (part "R-US_R0805"))
    )
    (comp (ref "R20")
      (value "180R")
      (footprint "eagle-import:R0805")
      (libsource (lib "eagle-import") (part "R-US_R0805"))
    )
    (comp (ref "R21")
      (value "4K7 0.1%")
      (footprint "eagle-import:R0805")
      (libsource (lib "eagle-import") (part "R-US_R0805"))
    )
    (comp (ref "R22")
      (value "220R")
      (footprint "eagle-import:R0805")
      (libsource (lib "eagle-import") (part "R-US_R0805"))
    )
    (comp (ref "R23")
      (value "180R")
      (footprint "eagle-import:R0805")
      (libsource (lib "eagle-import") (part "R-US_R0805"))
    )
    (comp (ref "R24")
      (value "10K")
      (footprint "eagle-import:R0805")
      (libsource (lib "eagle-import") (part "R-US_R0805"))
    )
    (comp (ref "R25")
      (value "220R")
      (footprint "eagle-import:R0805")
      (libsource (lib "eagle-import") (part "R-US_R0805"))
    )
    (comp (ref "R26")
      (value "22R")
      (footprint "eagle-import:R0805")
      (libsource (lib "eagle-import") (part "R-US_R0805"))
    )
    (comp (ref "R27")
      (value "22R")
      (footprint "eagle-import:R0805")
      (libsource (lib "eagle-import") (part "R-US_R0805"))
    )
    (comp (ref "R28")
      (value "22R")
      (footprint "eagle-import:R0805")
      (libsource (lib "eagle-import") (part "R-US_R0805"))
    )
    (comp (ref "R29")
      (value "22R")
      (footprint "eagle-import:R0805")
      (libsource (lib "eagle-import") (part "R-US_R0805"))
    )
    (comp (ref "R30")
      (value "68R")
      (footprint "eagle-import:R0805")
      (libsource (lib "eagle-import") (part "R-US_R0805"))
    )
    (comp (ref "R31")
      (value "47K")
      (footprint "eagle-import:R0805")
      (libsource (lib "eagle-import") (part "R-US_R0805"))
    )
    (comp (ref "R32")
      (value "0R0501")
      (footprint "eagle-import:R0805")
      (libsource (lib "eagle-import") (part "R-US_R0805"))
    )
    (comp (ref "R33")
      (value "0R0501")
      (footprint "eagle-import:R0805")
      (libsource (lib "eagle-import") (part "R-US_R0805"))
    )
    (comp (ref "R34")
      (value "0R0501")
      (footprint "eagle-import:R0805")
      (libsource (lib "eagle-import") (part "R-US_R0805"))
    )
    (comp (ref "R35")
      (value "0R0501")
      (footprint "eagle-import:R0805")
      (libsource (lib "eagle-import") (part "R-US_R0805"))
    )
    (comp (ref "R36")
      (value "DNP 100K")
      (footprint "eagle-import:R0805")
      (libsource (lib "eagle-import") (part "R-US_R0805"))
    )
    (comp (ref "R37")
      (value "27K")
      (footprint "eagle-import:R0805")
      (libsource (lib "eagle-import") (part "R-US_R0805"))
    )
    (comp (ref "R38")
      (value "22R")
      (footprint "eagle-import:R0805")
      (libsource (lib "eagle-import") (part "R-US_R0805"))
    )
    (comp (ref "R39")
      (value "22R")
      (footprint "eagle-import:R0805")
      (libsource (lib "eagle-import") (part "R-US_R0805"))
    )
    (comp (ref "R40")
      (value "22R")
      (footprint "eagle-import:R0805")
      (libsource (lib "eagle-import") (part "R-US_R0805"))
    )
    (comp (ref "R41")
      (value "22R")
      (footprint "eagle-import:R0805")
      (libsource (lib "eagle-import") (part "R-US_R0805"))
    )
    (comp (ref "R42")
      (value "1K")
      (footprint "eagle-import:R0805")
      (libsource (lib "eagle-import") (part "R-US_R0805"))
    )
    (comp (ref "R43")
      (value "1K")
      (footprint "eagle-import:R0805")
      (libsource (lib "eagle-import") (part "R-US_R0805"))
    )
    (comp (ref "R44")
      (value "0R0501")
      (footprint "eagle-import:R0805")
      (libsource (lib "eagle-import") (part "R-US_R0805"))
    )
    (comp (ref "R45")
      (value "0R0501")
      (footprint "eagle-import:R0805")
      (libsource (lib "eagle-import") (part "R-US_R0805"))
    )
    (comp (ref "R46")
      (value "0R0501")
      (footprint "eagle-import:R0805")
      (libsource (lib "eagle-import") (part "R-US_R0805"))
    )
    (comp (ref "R47")
      (value "0R0501")
      (footprint "eagle-import:R0805")
      (libsource (lib "eagle-import") (part "R-US_R0805"))
    )
    (comp (ref "R48")
      (value "220R")
      (footprint "eagle-import:R0805")
      (libsource (lib "eagle-import") (part "R-US_R0805"))
    )
    (comp (ref "R49")
      (value "DNP 100K")
      (footprint "eagle-import:R0805")
      (libsource (lib "eagle-import") (part "R-US_R0805"))
    )
    (comp (ref "R50")
      (value "10K")
      (footprint "eagle-import:R0805")
      (libsource (lib "eagle-import") (part "R-US_R0805"))
    )
    (comp (ref "R51")
      (value "10K")
      (footprint "eagle-import:R0805")
      (libsource (lib "eagle-import") (part "R-US_R0805"))
    )
    (comp (ref "R52")
      (value "DNP 100K")
      (footprint "eagle-import:R0805")
      (libsource (lib "eagle-import") (part "R-US_R0805"))
    )
    (comp (ref "R53")
      (value "4K7 0.1%")
      (footprint "eagle-import:R0805")
      (libsource (lib "eagle-import") (part "R-US_R0805"))
    )
    (comp (ref "R54")
      (value "4K7")
      (footprint "eagle-import:R0805")
      (libsource (lib "eagle-import") (part "R-US_R0805"))
    )
    (comp (ref "R55")
      (value "4K7")
      (footprint "eagle-import:R0805")
      (libsource (lib "eagle-import") (part "R-US_R0805"))
    )
    (comp (ref "R56")
      (value "10K")
      (footprint "eagle-import:R0805")
      (libsource (lib "eagle-import") (part "R-US_R0805"))
    )
    (comp (ref "R57")
      (value "10K")
      (footprint "eagle-import:R0805")
      (libsource (lib "eagle-import") (part "R-US_R0805"))
    )
    (comp (ref "R58")
      (value "10K")
      (footprint "eagle-import:R0805")
      (libsource (lib "eagle-import") (part "R-US_R0805"))
    )
    (comp (ref "R59")
      (value "10K")
      (footprint "eagle-import:R0805")
      (libsource (lib "eagle-import") (part "R-US_R0805"))
    )
    (comp (ref "R60")
      (value "180R")
      (footprint "eagle-import:R0805")
      (libsource (lib "eagle-import") (part "R-US_R0805"))
    )
    (comp (ref "R61")
      (value "2K2")
      (footprint "eagle-import:R0805")
      (libsource (lib "eagle-import") (part "R-US_R0805"))
    )
    (comp (ref "R62")
      (value "10K")
      (footprint "eagle-import:R0805")
      (libsource (lib "eagle-import") (part "R-US_R0805"))
    )
    (comp (ref "R63")
      (value "10K")
      (footprint "eagle-import:R0805")
      (libsource (lib "eagle-import") (part "R-US_R0805"))
    )
    (comp (ref "R64")
      (value "10K")
      (footprint "eagle-import:R0805")
      (libsource (lib "eagle-import") (part "R-US_R0805"))
    )
    (comp (ref "R65")
      (value "4K7")
      (footprint "eagle-import:R0805")
      (libsource (lib "eagle-import") (part "R-US_R0805"))
    )
    (comp (ref "R66")
      (value "1K")
      (footprint "eagle-import:R0805")
      (libsource (lib "eagle-import") (part "R-US_R0805"))
    )
    (comp (ref "R67")
      (value "4K7")
      (footprint "eagle-import:R0805")
      (libsource (lib "eagle-import") (part "R-US_R0805"))
    )
    (comp (ref "R68")
      (value "100R")
      (footprint "eagle-import:R0805")
      (libsource (lib "eagle-import") (part "R-US_R0805"))
    )
    (comp (ref "R69")
      (value "1K")
      (footprint "eagle-import:R0805")
      (libsource (lib "eagle-import") (part "R-US_R0805"))
    )
    (comp (ref "R70")
      (value "1K")
      (footprint "eagle-import:R0805")
      (libsource (lib "eagle-import") (part "R-US_R0805"))
    )
    (comp (ref "R71")
      (value "1K")
      (footprint "eagle-import:R0805")
      (libsource (lib "eagle-import") (part "R-US_R0805"))
    )
    (comp (ref "R72")
      (value "1K")
      (footprint "eagle-import:R0805")
      (libsource (lib "eagle-import") (part "R-US_R0805"))
    )
    (comp (ref "R73")
      (value "DNP 47K")
      (footprint "eagle-import:R0805")
      (libsource (lib "eagle-import") (part "R-US_R0805"))
    )
    (comp (ref "R74")
      (value "DNP 47K")
      (footprint "eagle-import:R0805")
      (libsource (lib "eagle-import") (part "R-US_R0805"))
    )
    (comp (ref "R75")
      (value "DNP 47K")
      (footprint "eagle-import:R0805")
      (libsource (lib "eagle-import") (part "R-US_R0805"))
    )
    (comp (ref "R76")
      (value "DNP 47K")
      (footprint "eagle-import:R0805")
      (libsource (lib "eagle-import") (part "R-US_R0805"))
    )
    (comp (ref "R77")
      (value "220R")
      (footprint "eagle-import:R0805")
      (libsource (lib "eagle-import") (part "R-US_R0805"))
    )
    (comp (ref "R78")
      (value "220R")
      (footprint "eagle-import:R0805")
      (libsource (lib "eagle-import") (part "R-US_R0805"))
    )
    (comp (ref "R79")
      (value "220R")
      (footprint "eagle-import:R0805")
      (libsource (lib "eagle-import") (part "R-US_R0805"))
    )
    (comp (ref "R80")
      (value "47K 1%")
      (footprint "eagle-import:R0805")
      (libsource (lib "eagle-import") (part "R-US_R0805"))
    )
    (comp (ref "R81")
      (value "47K 1%")
      (footprint "eagle-import:R0805")
      (libsource (lib "eagle-import") (part "R-US_R0805"))
    )
    (comp (ref "R82")
      (value "0R DNP")
      (footprint "eagle-import:R0805")
      (libsource (lib "eagle-import") (part "R-US_R0805"))
    )
    (comp (ref "R83")
      (value "10K")
      (footprint "eagle-import:R0805")
      (libsource (lib "eagle-import") (part "R-US_R0805"))
    )
    (comp (ref "R84")
      (value "100K")
      (footprint "eagle-import:R0805")
      (libsource (lib "eagle-import") (part "R-US_R0805"))
    )
    (comp (ref "R85")
      (value "0R13 0.33W")
      (footprint "eagle-import:R0805")
      (libsource (lib "eagle-import") (part "R-US_R0805"))
    )
    (comp (ref "R86")
      (value "0R13 0.33W")
      (footprint "eagle-import:R0805")
      (libsource (lib "eagle-import") (part "R-US_R0805"))
    )
    (comp (ref "R87")
      (value "3K6")
      (footprint "eagle-import:R0805")
      (libsource (lib "eagle-import") (part "R-US_R0805"))
    )
    (comp (ref "R88")
      (value "680R")
      (footprint "eagle-import:R0805")
      (libsource (lib "eagle-import") (part "R-US_R0805"))
    )
    (comp (ref "R89")
      (value "22R")
      (footprint "eagle-import:R0805")
      (libsource (lib "eagle-import") (part "R-US_R0805"))
    )
    (comp (ref "R90")
      (value "22R")
      (footprint "eagle-import:R0805")
      (libsource (lib "eagle-import") (part "R-US_R0805"))
    )
    (comp (ref "R91")
      (value "10K")
      (footprint "eagle-import:R0805")
      (libsource (lib "eagle-import") (part "R-US_R0805"))
    )
    (comp (ref "R92")
      (value "3R3 0.33W")
      (footprint "eagle-import:R0805")
      (libsource (lib "eagle-import") (part "R-US_R0805"))
    )
    (comp (ref "R93")
      (value "0R0501")
      (footprint "eagle-import:R0805")
      (libsource (lib "eagle-import") (part "R-US_R0805"))
    )
    (comp (ref "R94")
      (value "0R0501")
      (footprint "eagle-import:R0805")
      (libsource (lib "eagle-import") (part "R-US_R0805"))
    )
    (comp (ref "R95")
      (value "10K")
      (footprint "eagle-import:R0805")
      (libsource (lib "eagle-import") (part "R-US_R0805"))
    )
    (comp (ref "R96")
      (value "1K")
      (footprint "eagle-import:R0805")
      (libsource (lib "eagle-import") (part "R-US_R0805"))
    )
    (comp (ref "R97")
      (value "180R")
      (footprint "eagle-import:R0805")
      (libsource (lib "eagle-import") (part "R-US_R0805"))
    )
    (comp (ref "R98")
      (value "4K7")
      (footprint "eagle-import:R0805")
      (libsource (lib "eagle-import") (part "R-US_R0805"))
    )
    (comp (ref "R99")
      (value "2K2")
      (footprint "eagle-import:R0805")
      (libsource (lib "eagle-import") (part "R-US_R0805"))
    )
    (comp (ref "R100")
      (value "47R")
      (footprint "eagle-import:R0805")
      (libsource (lib "eagle-import") (part "R-US_R0805"))
    )
    (comp (ref "R101")
      (value "47R")
      (footprint "eagle-import:R0805")
      (libsource (lib "eagle-import") (part "R-US_R0805"))
    )
    (comp (ref "R102")
      (value "2K2")
      (footprint "eagle-import:R0805")
      (libsource (lib "eagle-import") (part "R-US_R0805"))
    )
    (comp (ref "R103")
      (value "470R")
      (footprint "eagle-import:R0805")
      (libsource (lib "eagle-import") (part "R-US_R0805"))
    )
    (comp (ref "R104")
      (value "2K2")
      (footprint "eagle-import:R0805")
      (libsource (lib "eagle-import") (part "R-US_R0805"))
    )
    (comp (ref "R105")
      (value "47R")
      (footprint "eagle-import:R0805")
      (libsource (lib "eagle-import") (part "R-US_R0805"))
    )
    (comp (ref "R106")
      (value "10K")
      (footprint "eagle-import:R0805")
      (libsource (lib "eagle-import") (part "R-US_R0805"))
    )
    (comp (ref "R107")
      (value "100R")
      (footprint "eagle-import:R0805")
      (libsource (lib "eagle-import") (part "R-US_R0805"))
    )
    (comp (ref "S1")
      (value "RESET")
      (footprint "eagle-import:B3F-10XX")
      (fields (field (name "MPN") "B3F-1000"))
      (libsource (lib "eagle-import") (part "10-XX"))
    )
    (comp (ref "TP1")
      (value "Z_Stp_Tp")
      (footprint "eagle-import:TP-3-PIN")
      (libsource (lib "eagle-import") (part "TP-3PIN"))
    )
    (comp (ref "TP2")
      (value "Y_Stp_Tp")
      (footprint "eagle-import:TP-3-PIN")
      (libsource (lib "eagle-import") (part "TP-3PIN"))
    )
    (comp (ref "TP3")
      (value "X_Stp_Tp")
      (footprint "eagle-import:TP-3-PIN")
      (libsource (lib "eagle-import") (part "TP-3PIN"))
    )
    (comp (ref "TP4")
      (value "E0_Stp_Tp")
      (footprint "eagle-import:TP-3-PIN")
      (libsource (lib "eagle-import") (part "TP-3PIN"))
    )
    (comp (ref "TP5")
      (value "E1_Stp_Tp")
      (footprint "eagle-import:TP-3-PIN")
      (libsource (lib "eagle-import") (part "TP-3PIN"))
    )
    (comp (ref "TP6")
      (value "TP-VIA")
      (footprint "eagle-import:TP-VIA")
      (libsource (lib "eagle-import") (part "TP-VIA"))
    )
    (comp (ref "TP7")
      (value "TP-VIA")
      (footprint "eagle-import:TP-VIA")
      (libsource (lib "eagle-import") (part "TP-VIA"))
    )
    (comp (ref "TP8")
      (value "TP-VIA")
      (footprint "eagle-import:TP-VIA")
      (libsource (lib "eagle-import") (part "TP-VIA"))
    )
    (comp (ref "TP9")
      (value "TP-VIA")
      (footprint "eagle-import:TP-VIA")
      (libsource (lib "eagle-import") (part "TP-VIA"))
    )
    (comp (ref "TP10")
      (value "TP-VIA")
      (footprint "eagle-import:TP-VIA")
      (libsource (lib "eagle-import") (part "TP-VIA"))
    )
    (comp (ref "TP11")
      (value "TP-VIA")
      (footprint "eagle-import:TP-VIA")
      (libsource (lib "eagle-import") (part "TP-VIA"))
    )
    (comp (ref "TP12")
      (value "TP-VIA")
      (footprint "eagle-import:TP-VIA")
      (libsource (lib "eagle-import") (part "TP-VIA"))
    )
    (comp (ref "TP13")
      (value "TP-VIA")
      (footprint "eagle-import:TP-VIA")
      (libsource (lib "eagle-import") (part "TP-VIA"))
    )
    (comp (ref "TP14")
      (value "TP-VIA")
      (footprint "eagle-import:TP-VIA")
      (libsource (lib "eagle-import") (part "TP-VIA"))
    )
    (comp (ref "TP15")
      (value "TP-VIA")
      (footprint "eagle-import:TP-VIA")
      (libsource (lib "eagle-import") (part "TP-VIA"))
    )
    (comp (ref "TP16")
      (value "TP-VIA")
      (footprint "eagle-import:TP-VIA")
      (libsource (lib "eagle-import") (part "TP-VIA"))
    )
    (comp (ref "TR1")
      (value "PMV40UN2")
      (footprint "eagle-import:SOT23")
      (libsource (lib "eagle-import") (part "MOSFET-NREFLOW"))
    )
    (comp (ref "TR2")
      (value "IPD036N04L")
      (footprint "eagle-import:TO252")
      (libsource (lib "eagle-import") (part "SPD30P06PTO252"))
    )
    (comp (ref "TR4")
      (value "IPD036N04L")
      (footprint "eagle-import:TO252")
      (libsource (lib "eagle-import") (part "SPD30P06PTO252"))
    )
    (comp (ref "TR5")
      (value "PMV40UN2")
      (footprint "eagle-import:SOT23")
      (libsource (lib "eagle-import") (part "MOSFET-NREFLOW"))
    )
    (comp (ref "TR7")
      (value "PMV40UN2")
      (footprint "eagle-import:SOT23")
      (libsource (lib "eagle-import") (part "MOSFET-NREFLOW"))
    )
    (comp (ref "TR8")
      (value "IPD036N04L")
      (footprint "eagle-import:TO252")
      (libsource (lib "eagle-import") (part "SPD30P06PTO252"))
    )
    (comp (ref "TR9")
      (value "PMV40UN2")
      (footprint "eagle-import:SOT23")
      (libsource (lib "eagle-import") (part "MOSFET-NREFLOW"))
    )
    (comp (ref "U$1")
      (value "BED HEAT")
      (footprint "eagle-import:2-PIN-635")
      (libsource (lib "eagle-import") (part "2-PIN-635"))
    )
    (comp (ref "U1")
      (value "ATSAM4E8E")
      (footprint "eagle-import:LQFP144")
      (libsource (lib "eagle-import") (part "ATSAM4E8E"))
    )
    (comp (ref "U2")
      (value "AP7361C-33E-13")
      (footprint "eagle-import:SOT223")
      (libsource (lib "eagle-import") (part "UA78MDCY33"))
    )
    (comp (ref "U3")
      (value "A4403")
      (footprint "eagle-import:QFN16-4X4")
      (libsource (lib "eagle-import") (part "A4403"))
    )
    (comp (ref "U4")
      (value "ESP-12")
      (footprint "eagle-import:ESP-12")
      (libsource (lib "eagle-import") (part "ESP-12"))
    )
    (comp (ref "U5")
      (value "TMC2660")
      (footprint "eagle-import:TMC2660")
      (libsource (lib "eagle-import") (part "TMC2660"))
    )
    (comp (ref "U6")
      (value "TMC2660")
      (footprint "eagle-import:TMC2660")
      (libsource (lib "eagle-import") (part "TMC2660"))
    )
    (comp (ref "U7")
      (value "TMC2660")
      (footprint "eagle-import:TMC2660")
      (libsource (lib "eagle-import") (part "TMC2660"))
    )
    (comp (ref "U8")
      (value "TMC2660")
      (footprint "eagle-import:TMC2660")
      (libsource (lib "eagle-import") (part "TMC2660"))
    )
    (comp (ref "U9")
      (value "TMC2660")
      (footprint "eagle-import:TMC2660")
      (libsource (lib "eagle-import") (part "TMC2660"))
    )
    (comp (ref "U10")
      (value "74HC125")
      (footprint "eagle-import:SO14")
      (libsource (lib "eagle-import") (part "74125DAC"))
    )
    (comp (ref "U11")
      (value "74S02D")
      (footprint "eagle-import:SO14")
      (libsource (lib "eagle-import") (part "7402DS"))
    )
    (comp (ref "U13")
      (value "74HC32")
      (footprint "eagle-import:SO14")
      (libsource (lib "eagle-import") (part "7432DHC"))
    )
    (comp (ref "X2")
      (value "CRYSTAL_4PIN")
      (footprint "eagle-import:CRYSTAL-3.2-2.5")
      (libsource (lib "eagle-import") (part "CRYSTAL-3.2-2.5"))
    )
  )
  (nets
    (net (code "1") (name "+3V3") (class "Default")
      (node (ref "C100") (pin "1") (pinfunction "1_1") (pintype "passive"))
      (node (ref "C11") (pin "1") (pinfunction "1_1") (pintype "passive"))
      (node (ref "C124") (pin "1") (pinfunction "1_1") (pintype "passive"))
      (node (ref "C16") (pin "1") (pinfunction "1_1") (pintype "passive"))
      (node (ref "C17") (pin "1") (pinfunction "1_1") (pintype "passive"))
      (node (ref "C20") (pin "1") (pinfunction "1_1") (pintype "passive"))
      (node (ref "C21") (pin "1") (pinfunction "1_1") (pintype "passive"))
      (node (ref "C30") (pin "1") (pinfunction "1_1") (pintype "passive"))
      (node (ref "C31") (pin "1") (pinfunction "1_1") (pintype "passive"))
      (node (ref "C4") (pin "1") (pinfunction "1_1") (pintype "passive"))
      (node (ref "C46") (pin "1") (pinfunction "1_1") (pintype "passive"))
      (node (ref "C47") (pin "1") (pinfunction "1_1") (pintype "passive"))
      (node (ref "C48") (pin "1") (pinfunction "1_1") (pintype "passive"))
      (node (ref "C49") (pin "1") (pinfunction "1_1") (pintype "passive"))
      (node (ref "C50") (pin "1") (pinfunction "1_1") (pintype "passive"))
      (node (ref "C51") (pin "1") (pinfunction "1_1") (pintype "passive"))
      (node (ref "C55") (pin "1") (pinfunction "1_1") (pintype "passive"))
      (node (ref "C58") (pin "1") (pinfunction "1_1") (pintype "passive"))
      (node (ref "C73") (pin "1") (pinfunction "1_1") (pintype "passive"))
      (node (ref "C74") (pin "1") (pinfunction "1_1") (pintype "passive"))
      (node (ref "C8") (pin "1") (pinfunction "1_1") (pintype "passive"))
      (node (ref "C9") (pin "1") (pinfunction "1_1") (pintype "passive"))
      (node (ref "D16") (pin "A") (pinfunction "A_A") (pintype "passive"))
      (node (ref "D22") (pin "3") (pinfunction "CC_3") (pintype "passive"))
      (node (ref "D23") (pin "3") (pinfunction "CC_3") (pintype "passive"))
      (node (ref "D24") (pin "3") (pinfunction "CC_3") (pintype "passive"))
      (node (ref "IC1") (pin "10") (pinfunction "PRE_10") (pintype "input"))
      (node (ref "IC1") (pin "11") (pinfunction "CLK_11") (pintype "input"))
      (node (ref "IC1") (pin "12") (pinfunction "D_12") (pintype "input"))
      (node (ref "IC1") (pin "13") (pinfunction "CLR_13") (pintype "input"))
      (node (ref "IC1") (pin "14") (pinfunction "VCC_14") (pintype "power_in"))
      (node (ref "IC1") (pin "2") (pinfunction "D_2") (pintype "input"))
      (node (ref "IC1") (pin "4") (pinfunction "PRE_4") (pintype "input"))
      (node (ref "J1") (pin "3") (pinfunction "S_3") (pintype "passive"))
      (node (ref "J1") (pin "43") (pinfunction "S_43") (pintype "passive"))
      (node (ref "J15") (pin "4") (pinfunction "VDD_4") (pintype "bidirectional"))
      (node (ref "J19") (pin "2") (pinfunction "S_2") (pintype "passive"))
      (node (ref "J21") (pin "1") (pinfunction "VCC_1") (pintype "bidirectional"))
      (node (ref "J28") (pin "4") (pinfunction "S_4") (pintype "passive"))
      (node (ref "J32") (pin "2") (pinfunction "S_2") (pintype "passive"))
      (node (ref "J33") (pin "2") (pinfunction "S_2") (pintype "passive"))
      (node (ref "J34") (pin "2") (pinfunction "S_2") (pintype "passive"))
      (node (ref "J35") (pin "2") (pinfunction "S_2") (pintype "passive"))
      (node (ref "J37") (pin "8") (pinfunction "S_8") (pintype "passive"))
      (node (ref "JP1") (pin "1") (pinfunction "1_1") (pintype "passive"))
      (node (ref "L5") (pin "1") (pinfunction "1_1") (pintype "passive"))
      (node (ref "L7") (pin "1") (pinfunction "1_1") (pintype "passive"))
      (node (ref "P1") (pin "8") (pinfunction "S_8") (pintype "passive"))
      (node (ref "P2") (pin "1") (pinfunction "S_1") (pintype "passive"))
      (node (ref "R106") (pin "2") (pinfunction "2_2") (pintype "passive"))
      (node (ref "R36") (pin "2") (pinfunction "2_2") (pintype "passive"))
      (node (ref "R49") (pin "2") (pinfunction "2_2") (pintype "passive"))
      (node (ref "R51") (pin "2") (pinfunction "2_2") (pintype "passive"))
      (node (ref "R52") (pin "2") (pinfunction "2_2") (pintype "passive"))
      (node (ref "R63") (pin "2") (pinfunction "2_2") (pintype "passive"))
      (node (ref "R64") (pin "2") (pinfunction "2_2") (pintype "passive"))
      (node (ref "R69") (pin "2") (pinfunction "2_2") (pintype "passive"))
      (node (ref "R70") (pin "2") (pinfunction "2_2") (pintype "passive"))
      (node (ref "R71") (pin "2") (pinfunction "2_2") (pintype "passive"))
      (node (ref "R72") (pin "2") (pinfunction "2_2") (pintype "passive"))
      (node (ref "R73") (pin "2") (pinfunction "2_2") (pintype "passive"))
      (node (ref "R74") (pin "2") (pinfunction "2_2") (pintype "passive"))
      (node (ref "R75") (pin "2") (pinfunction "2_2") (pintype "passive"))
      (node (ref "R76") (pin "2") (pinfunction "2_2") (pintype "passive"))
      (node (ref "R96") (pin "2") (pinfunction "2_2") (pintype "passive"))
      (node (ref "U1") (pin "134") (pinfunction "VDDIO6_134") (pintype "power_in"))
      (node (ref "U1") (pin "143") (pinfunction "VDDIO7_143") (pintype "power_in"))
      (node (ref "U1") (pin "30") (pinfunction "VDDIO1_30") (pintype "power_in"))
      (node (ref "U1") (pin "43") (pinfunction "VDDIO2_43") (pintype "power_in"))
      (node (ref "U1") (pin "5") (pinfunction "VDDIN_5") (pintype "power_in"))
      (node (ref "U1") (pin "72") (pinfunction "VDDIO3_72") (pintype "power_in"))
      (node (ref "U1") (pin "80") (pinfunction "VDDIO4_80") (pintype "power_in"))
      (node (ref "U1") (pin "96") (pinfunction "VDDIO5_96") (pintype "power_in"))
      (node (ref "U10") (pin "14") (pinfunction "VCC_14") (pintype "power_in"))
      (node (ref "U11") (pin "2") (pinfunction "I0_2") (pintype "input"))
      (node (ref "U11") (pin "3") (pinfunction "I1_3") (pintype "input"))
      (node (ref "U13") (pin "14") (pinfunction "VCC_14") (pintype "power_in"))
      (node (ref "U2") (pin "3") (pinfunction "VO_3") (pintype "passive"))
      (node (ref "U5") (pin "40") (pinfunction "VCC_IO_40") (pintype "input"))
      (node (ref "U6") (pin "40") (pinfunction "VCC_IO_40") (pintype "input"))
      (node (ref "U7") (pin "40") (pinfunction "VCC_IO_40") (pintype "input"))
      (node (ref "U8") (pin "40") (pinfunction "VCC_IO_40") (pintype "input"))
      (node (ref "U9") (pin "40") (pinfunction "VCC_IO_40") (pintype "input"))
    )
    (net (code "2") (name "+5V") (class "Default")
      (node (ref "C54") (pin "1") (pinfunction "1_1") (pintype "passive"))
      (node (ref "C7") (pin "1") (pinfunction "1_1") (pintype "passive"))
      (node (ref "C99") (pin "+") (pinfunction "+_+") (pintype "passive"))
      (node (ref "D13") (pin "C") (pinfunction "C_C") (pintype "passive"))
      (node (ref "D17") (pin "A") (pinfunction "A_A") (pintype "passive"))
      (node (ref "J1") (pin "1") (pinfunction "S_1") (pintype "passive"))
      (node (ref "J3") (pin "1") (pinfunction "1_1") (pintype "passive"))
      (node (ref "J30") (pin "1") (pinfunction "S_1") (pintype "passive"))
      (node (ref "J39") (pin "8") (pinfunction "8_8") (pintype "passive"))
      (node (ref "JP10") (pin "1") (pinfunction "1_1") (pintype "passive"))
      (node (ref "L3") (pin "1") (pinfunction "1_1") (pintype "passive"))
      (node (ref "P1") (pin "1") (pinfunction "S_1") (pintype "passive"))
      (node (ref "U11") (pin "14") (pinfunction "VCC_14") (pintype "power_in"))
      (node (ref "U2") (pin "1") (pinfunction "VI_1") (pintype "input"))
    )
    (net (code "3") (name "/5V_IN") (class "Default")
      (node (ref "D14") (pin "A") (pinfunction "A_A") (pintype "passive"))
      (node (ref "J20") (pin "1") (pinfunction "S_1") (pintype "passive"))
    )
    (net (code "4") (name "/ADC") (class "Default")
      (node (ref "J16") (pin "7") (pinfunction "7_7") (pintype "passive"))
      (node (ref "J39") (pin "4") (pinfunction "4_4") (pintype "passive"))
      (node (ref "U4") (pin "2") (pinfunction "ADC_2") (pintype "passive"))
    )
    (net (code "5") (name "/ADVREF") (class "Default")
      (node (ref "C64") (pin "1") (pinfunction "1_1") (pintype "passive"))
      (node (ref "J1") (pin "41") (pinfunction "S_41") (pintype "passive"))
      (node (ref "L5") (pin "2") (pinfunction "2_2") (pintype "passive"))
      (node (ref "R19") (pin "2") (pinfunction "2_2") (pintype "passive"))
      (node (ref "R21") (pin "2") (pinfunction "2_2") (pintype "passive"))
      (node (ref "R53") (pin "2") (pinfunction "2_2") (pintype "passive"))
      (node (ref "U1") (pin "9") (pinfunction "ADVREFP_9") (pintype "power_in"))
    )
    (net (code "6") (name "/BED-") (class "Default")
      (node (ref "D5") (pin "A") (pinfunction "A_A") (pintype "passive"))
      (node (ref "D6") (pin "C") (pinfunction "C_C") (pintype "passive"))
      (node (ref "TR2") (pin "2") (pinfunction "S_2") (pintype "passive"))
      (node (ref "U$1") (pin "1") (pinfunction "1_1") (pintype "passive"))
    )
    (net (code "7") (name "/BED_PWM") (class "Default")
      (node (ref "R20") (pin "1") (pinfunction "1_1") (pintype "passive"))
      (node (ref "TP9") (pin "TP") (pinfunction "TP_TP") (pintype "input"))
      (node (ref "U11") (pin "4") (pinfunction "O_4") (pintype "output"))
    )
    (net (code "8") (name "/CS3") (class "Default")
      (node (ref "J37") (pin "7") (pinfunction "S_7") (pintype "passive"))
      (node (ref "U1") (pin "117") (pinfunction "PC19_117") (pintype "bidirectional"))
    )
    (net (code "9") (name "/CS4") (class "Default")
      (node (ref "J37") (pin "9") (pinfunction "S_9") (pintype "passive"))
      (node (ref "U1") (pin "120") (pinfunction "PC20_120") (pintype "bidirectional"))
    )
    (net (code "10") (name "/CS5") (class "Default")
      (node (ref "J1") (pin "50") (pinfunction "S_50") (pintype "passive"))
      (node (ref "U1") (pin "56") (pinfunction "PA24/PGMD12/RTS1_56") (pintype "bidirectional"))
    )
    (net (code "11") (name "/D6_TESTPOINT") (class "Default")
      (node (ref "TP16") (pin "TP") (pinfunction "TP_TP") (pintype "input"))
    )
    (net (code "12") (name "/DDM") (class "Default")
      (node (ref "R3") (pin "1") (pinfunction "1_1") (pintype "passive"))
      (node (ref "U1") (pin "136") (pinfunction "PB10/DDM_136") (pintype "bidirectional"))
    )
    (net (code "13") (name "/DDP") (class "Default")
      (node (ref "R2") (pin "1") (pinfunction "1_1") (pintype "passive"))
      (node (ref "U1") (pin "137") (pinfunction "PB11/DDP_137") (pintype "bidirectional"))
    )
    (net (code "14") (name "/E0-") (class "Default")
      (node (ref "D7") (pin "C") (pinfunction "C_C") (pintype "passive"))
      (node (ref "J11") (pin "2") (pinfunction "1_2") (pintype "passive"))
      (node (ref "TR4") (pin "2") (pinfunction "S_2") (pintype "passive"))
    )
    (net (code "15") (name "/E0_DIR") (class "Default")
      (node (ref "TP4") (pin "2") (pinfunction "TP1_2") (pintype "input"))
      (node (ref "U1") (pin "99") (pinfunction "PA1/PGMEN1_99") (pintype "bidirectional"))
      (node (ref "U8") (pin "41") (pinfunction "DIR_41") (pintype "input"))
    )
    (net (code "16") (name "/E0_EN") (class "Default")
      (node (ref "TP4") (pin "3") (pinfunction "TP2_3") (pintype "input"))
      (node (ref "U1") (pin "103") (pinfunction "PC17_103") (pintype "bidirectional"))
      (node (ref "U8") (pin "18") (pinfunction "~{CS}_18") (pintype "input"))
    )
    (net (code "17") (name "/E0_MOT_1A") (class "Default")
      (node (ref "C118") (pin "1") (pinfunction "1_1") (pintype "passive"))
      (node (ref "J10") (pin "2") (pinfunction "S_2") (pintype "passive"))
      (node (ref "U8") (pin "10") (pinfunction "OA2_10") (pintype "output"))
      (node (ref "U8") (pin "5") (pinfunction "OA2_5") (pintype "output"))
    )
    (net (code "18") (name "/E0_MOT_1B") (class "Default")
      (node (ref "C116") (pin "1") (pinfunction "1_1") (pintype "passive"))
      (node (ref "J10") (pin "1") (pinfunction "S_1") (pintype "passive"))
      (node (ref "U8") (pin "2") (pinfunction "OA1_2") (pintype "output"))
      (node (ref "U8") (pin "7") (pinfunction "OA1_7") (pintype "output"))
    )
    (net (code "19") (name "/E0_MOT_2A") (class "Default")
      (node (ref "C120") (pin "1") (pinfunction "1_1") (pintype "passive"))
      (node (ref "J10") (pin "3") (pinfunction "S_3") (pintype "passive"))
      (node (ref "U8") (pin "26") (pinfunction "OB1_26") (pintype "output"))
      (node (ref "U8") (pin "31") (pinfunction "OB1_31") (pintype "output"))
    )
    (net (code "20") (name "/E0_MOT_2B") (class "Default")
      (node (ref "C122") (pin "1") (pinfunction "1_1") (pintype "passive"))
      (node (ref "J10") (pin "4") (pinfunction "S_4") (pintype "passive"))
      (node (ref "U8") (pin "23") (pinfunction "OB2_23") (pintype "output"))
      (node (ref "U8") (pin "28") (pinfunction "OB2_28") (pintype "output"))
    )
    (net (code "21") (name "/E0_PWM") (class "Default")
      (node (ref "R23") (pin "1") (pinfunction "1_1") (pintype "passive"))
      (node (ref "TP10") (pin "TP") (pinfunction "TP_TP") (pintype "input"))
      (node (ref "U11") (pin "10") (pinfunction "O_10") (pintype "output"))
    )
    (net (code "22") (name "/E0_STEP") (class "Default")
      (node (ref "TP4") (pin "1") (pinfunction "TP_1") (pintype "input"))
      (node (ref "U1") (pin "125") (pinfunction "PD5_125") (pintype "bidirectional"))
      (node (ref "U8") (pin "42") (pinfunction "STEP_42") (pintype "input"))
    )
    (net (code "23") (name "/E0_STOP") (class "Default")
      (node (ref "C43") (pin "1") (pinfunction "1_1") (pintype "passive"))
      (node (ref "D23") (pin "2") (pinfunction "A2_2") (pintype "passive"))
      (node (ref "R59") (pin "2") (pinfunction "2_2") (pintype "passive"))
      (node (ref "U1") (pin "101") (pinfunction "PD10_101") (pintype "bidirectional"))
    )
    (net (code "24") (name "/E0_STOP_CON") (class "Default")
      (node (ref "J34") (pin "1") (pinfunction "S_1") (pintype "passive"))
    )
    (net (code "25") (name "/E0_STOP_CONN") (class "Default")
      (node (ref "D11") (pin "C") (pinfunction "C_C") (pintype "passive"))
      (node (ref "R59") (pin "1") (pinfunction "1_1") (pintype "passive"))
    )
    (net (code "26") (name "/E1-") (class "Default")
      (node (ref "D20") (pin "C") (pinfunction "C_C") (pintype "passive"))
      (node (ref "J13") (pin "2") (pinfunction "1_2") (pintype "passive"))
      (node (ref "TR8") (pin "2") (pinfunction "S_2") (pintype "passive"))
    )
    (net (code "27") (name "/E1_DIR") (class "Default")
      (node (ref "TP5") (pin "2") (pinfunction "TP1_2") (pintype "input"))
      (node (ref "U1") (pin "110") (pinfunction "PD9_110") (pintype "bidirectional"))
      (node (ref "U9") (pin "41") (pinfunction "DIR_41") (pintype "input"))
    )
    (net (code "28") (name "/E1_EN") (class "Default")
      (node (ref "TP5") (pin "3") (pinfunction "TP2_3") (pintype "input"))
      (node (ref "U1") (pin "133") (pinfunction "PC25_133") (pintype "bidirectional"))
      (node (ref "U9") (pin "18") (pinfunction "~{CS}_18") (pintype "input"))
    )
    (net (code "29") (name "/E1_MOT_1A") (class "Default")
      (node (ref "C119") (pin "1") (pinfunction "1_1") (pintype "passive"))
      (node (ref "J6") (pin "2") (pinfunction "S_2") (pintype "passive"))
      (node (ref "U9") (pin "10") (pinfunction "OA2_10") (pintype "output"))
      (node (ref "U9") (pin "5") (pinfunction "OA2_5") (pintype "output"))
    )
    (net (code "30") (name "/E1_MOT_1B") (class "Default")
      (node (ref "C117") (pin "1") (pinfunction "1_1") (pintype "passive"))
      (node (ref "J6") (pin "1") (pinfunction "S_1") (pintype "passive"))
      (node (ref "U9") (pin "2") (pinfunction "OA1_2") (pintype "output"))
      (node (ref "U9") (pin "7") (pinfunction "OA1_7") (pintype "output"))
    )
    (net (code "31") (name "/E1_MOT_2A") (class "Default")
      (node (ref "C121") (pin "1") (pinfunction "1_1") (pintype "passive"))
      (node (ref "J6") (pin "3") (pinfunction "S_3") (pintype "passive"))
      (node (ref "U9") (pin "26") (pinfunction "OB1_26") (pintype "output"))
      (node (ref "U9") (pin "31") (pinfunction "OB1_31") (pintype "output"))
    )
    (net (code "32") (name "/E1_MOT_2B") (class "Default")
      (node (ref "C123") (pin "1") (pinfunction "1_1") (pintype "passive"))
      (node (ref "J6") (pin "4") (pinfunction "S_4") (pintype "passive"))
      (node (ref "U9") (pin "23") (pinfunction "OB2_23") (pintype "output"))
      (node (ref "U9") (pin "28") (pinfunction "OB2_28") (pintype "output"))
    )
    (net (code "33") (name "/E1_PWM") (class "Default")
      (node (ref "R97") (pin "1") (pinfunction "1_1") (pintype "passive"))
      (node (ref "TP11") (pin "TP") (pinfunction "TP_TP") (pintype "input"))
      (node (ref "U11") (pin "13") (pinfunction "O_13") (pintype "output"))
    )
    (net (code "34") (name "/E1_STEP") (class "Default")
      (node (ref "TP5") (pin "1") (pinfunction "TP_1") (pintype "input"))
      (node (ref "U1") (pin "126") (pinfunction "PD4_126") (pintype "bidirectional"))
      (node (ref "U9") (pin "42") (pinfunction "STEP_42") (pintype "input"))
    )
    (net (code "35") (name "/E1_STOP") (class "Default")
      (node (ref "C111") (pin "1") (pinfunction "1_1") (pintype "passive"))
      (node (ref "D24") (pin "1") (pinfunction "A1_1") (pintype "passive"))
      (node (ref "R95") (pin "2") (pinfunction "2_2") (pintype "passive"))
      (node (ref "U1") (pin "100") (pinfunction "PC16_100") (pintype "bidirectional"))
    )
    (net (code "36") (name "/E1_STOP_CON") (class "Default")
      (node (ref "J35") (pin "1") (pinfunction "S_1") (pintype "passive"))
    )
    (net (code "37") (name "/E1_STOP_CONN") (class "Default")
      (node (ref "D19") (pin "C") (pinfunction "C_C") (pintype "passive"))
      (node (ref "R95") (pin "1") (pinfunction "1_1") (pintype "passive"))
    )
    (net (code "38") (name "/E2_DIR") (class "Default")
      (node (ref "J1") (pin "6") (pinfunction "S_6") (pintype "passive"))
      (node (ref "U1") (pin "71") (pinfunction "PD28_71") (pintype "bidirectional"))
    )
    (net (code "39") (name "/E2_EN") (class "Default")
      (node (ref "J1") (pin "7") (pinfunction "S_7") (pintype "passive"))
      (node (ref "U1") (pin "57") (pinfunction "PD23_57") (pintype "bidirectional"))
    )
    (net (code "40") (name "/E2_STEP") (class "Default")
      (node (ref "J1") (pin "5") (pinfunction "S_5") (pintype "passive"))
      (node (ref "U1") (pin "131") (pinfunction "PD2_131") (pintype "bidirectional"))
    )
    (net (code "41") (name "/E2_STOP") (class "Default")
      (node (ref "J1") (pin "4") (pinfunction "S_4") (pintype "passive"))
      (node (ref "U1") (pin "4") (pinfunction "PE0_4") (pintype "bidirectional"))
    )
    (net (code "42") (name "/E3_DIR") (class "Default")
      (node (ref "J1") (pin "11") (pinfunction "S_11") (pintype "passive"))
      (node (ref "U1") (pin "60") (pinfunction "PD22_60") (pintype "bidirectional"))
    )
    (net (code "43") (name "/E3_EN") (class "Default")
      (node (ref "J1") (pin "12") (pinfunction "S_12") (pintype "passive"))
      (node (ref "U1") (pin "55") (pinfunction "PD24_55") (pintype "bidirectional"))
    )
    (net (code "44") (name "/E3_STEP") (class "Default")
      (node (ref "J1") (pin "10") (pinfunction "S_10") (pintype "passive"))
      (node (ref "U1") (pin "132") (pinfunction "PD1_132") (pintype "bidirectional"))
    )
    (net (code "45") (name "/E3_STOP") (class "Default")
      (node (ref "J1") (pin "9") (pinfunction "S_9") (pintype "passive"))
      (node (ref "U1") (pin "6") (pinfunction "PE1_6") (pintype "bidirectional"))
    )
    (net (code "46") (name "/E4_DIR") (class "Default")
      (node (ref "J1") (pin "16") (pinfunction "S_16") (pintype "passive"))
      (node (ref "U1") (pin "78") (pinfunction "PD16_78") (pintype "bidirectional"))
    )
    (net (code "47") (name "/E4_EN") (class "Default")
      (node (ref "J1") (pin "17") (pinfunction "S_17") (pintype "passive"))
      (node (ref "U1") (pin "52") (pinfunction "PD25_52") (pintype "bidirectional"))
    )
    (net (code "48") (name "/E4_STEP") (class "Default")
      (node (ref "J1") (pin "15") (pinfunction "S_15") (pintype "passive"))
      (node (ref "U1") (pin "1") (pinfunction "PD0_1") (pintype "bidirectional"))
    )
    (net (code "49") (name "/E4_STOP") (class "Default")
      (node (ref "J1") (pin "14") (pinfunction "S_14") (pintype "passive"))
      (node (ref "U1") (pin "7") (pinfunction "PE2_7") (pintype "bidirectional"))
    )
    (net (code "50") (name "/E5_DIR") (class "Default")
      (node (ref "J1") (pin "21") (pinfunction "S_21") (pintype "passive"))
      (node (ref "U1") (pin "74") (pinfunction "PD17_74") (pintype "bidirectional"))
    )
    (net (code "51") (name "/E5_EN") (class "Default")
      (node (ref "J1") (pin "22") (pinfunction "S_22") (pintype "passive"))
      (node (ref "U1") (pin "53") (pinfunction "PD26_53") (pintype "bidirectional"))
    )
    (net (code "52") (name "/E5_STEP") (class "Default")
      (node (ref "J1") (pin "20") (pinfunction "S_20") (pintype "passive"))
      (node (ref "U1") (pin "128") (pinfunction "PD3_128") (pintype "bidirectional"))
    )
    (net (code "53") (name "/E5_STOP") (class "Default")
      (node (ref "J1") (pin "19") (pinfunction "S_19") (pintype "passive"))
      (node (ref "U1") (pin "10") (pinfunction "PE3_10") (pintype "bidirectional"))
    )
    (net (code "54") (name "/E6_DIR") (class "Default")
      (node (ref "J1") (pin "26") (pinfunction "S_26") (pintype "passive"))
      (node (ref "U1") (pin "11") (pinfunction "PC0/AFE0_AD14_11") (pintype "bidirectional"))
    )
    (net (code "55") (name "/E6_EN") (class "Default")
      (node (ref "J1") (pin "27") (pinfunction "S_27") (pintype "passive"))
      (node (ref "U1") (pin "140") (pinfunction "PB14/DAC1_140") (pintype "bidirectional"))
    )
    (net (code "56") (name "/E6_STEP") (class "Default")
      (node (ref "J1") (pin "25") (pinfunction "S_25") (pintype "passive"))
      (node (ref "U1") (pin "47") (pinfunction "PD27_47") (pintype "bidirectional"))
    )
    (net (code "57") (name "/E6_STOP") (class "Default")
      (node (ref "J1") (pin "24") (pinfunction "S_24") (pintype "passive"))
      (node (ref "U1") (pin "25") (pinfunction "PA17/PGMD5/AFE0_AD0_25") (pintype "bidirectional"))
    )
    (net (code "58") (name "/EDR_CONN") (class "Default")
      (node (ref "J16") (pin "12") (pinfunction "12_12") (pintype "passive"))
      (node (ref "R17") (pin "1") (pinfunction "1_1") (pintype "passive"))
      (node (ref "U4") (pin "12") (pinfunction "GPIO0_12") (pintype "bidirectional"))
    )
    (net (code "59") (name "/ENC_A") (class "Default")
      (node (ref "P2") (pin "4") (pinfunction "S_4") (pintype "passive"))
      (node (ref "U1") (pin "36") (pinfunction "PA8/PGMM0/XOUT32_36") (pintype "bidirectional"))
    )
    (net (code "60") (name "/ENC_B") (class "Default")
      (node (ref "P2") (pin "3") (pinfunction "S_3") (pintype "passive"))
      (node (ref "U1") (pin "48") (pinfunction "PC7_48") (pintype "bidirectional"))
    )
    (net (code "61") (name "/ENC_SW") (class "Default")
      (node (ref "P1") (pin "7") (pinfunction "S_7") (pintype "passive"))
      (node (ref "U1") (pin "35") (pinfunction "PA7/PGMNVALID/XIN32_35") (pintype "bidirectional"))
    )
    (net (code "62") (name "/ENN") (class "Default")
      (node (ref "J1") (pin "28") (pinfunction "S_28") (pintype "passive"))
      (node (ref "R51") (pin "1") (pinfunction "1_1") (pintype "passive"))
      (node (ref "U1") (pin "54") (pinfunction "PC6_54") (pintype "bidirectional"))
      (node (ref "U5") (pin "19") (pinfunction "~{EN}_19") (pintype "input"))
      (node (ref "U6") (pin "19") (pinfunction "~{EN}_19") (pintype "input"))
      (node (ref "U7") (pin "19") (pinfunction "~{EN}_19") (pintype "input"))
      (node (ref "U8") (pin "19") (pinfunction "~{EN}_19") (pintype "input"))
      (node (ref "U9") (pin "19") (pinfunction "~{EN}_19") (pintype "input"))
    )
    (net (code "63") (name "/ERASE") (class "Default")
      (node (ref "JP1") (pin "2") (pinfunction "2_2") (pintype "passive"))
      (node (ref "U1") (pin "87") (pinfunction "PB12/ERASE_87") (pintype "bidirectional"))
    )
    (net (code "64") (name "/ESP_3.3VIN") (class "Default")
      (node (ref "J16") (pin "6") (pinfunction "6_6") (pintype "passive"))
      (node (ref "L7") (pin "2") (pinfunction "2_2") (pintype "passive"))
      (node (ref "U4") (pin "8") (pinfunction "VCC_8") (pintype "power_in"))
    )
    (net (code "65") (name "/ESP_DATA_RDY") (class "Default")
      (node (ref "R17") (pin "2") (pinfunction "2_2") (pintype "passive"))
      (node (ref "U1") (pin "2") (pinfunction "PD31_2") (pintype "bidirectional"))
    )
    (net (code "66") (name "/ESP_EN") (class "Default")
      (node (ref "J16") (pin "2") (pinfunction "2_2") (pintype "passive"))
      (node (ref "R18") (pin "2") (pinfunction "2_2") (pintype "passive"))
      (node (ref "U1") (pin "28") (pinfunction "PE5_28") (pintype "bidirectional"))
      (node (ref "U4") (pin "3") (pinfunction "CH_PD_3") (pintype "input"))
    )
    (net (code "67") (name "/ESP_RST") (class "Default")
      (node (ref "J16") (pin "1") (pinfunction "1_1") (pintype "passive"))
      (node (ref "R5") (pin "2") (pinfunction "2_2") (pintype "passive"))
      (node (ref "U1") (pin "27") (pinfunction "PE4_27") (pintype "bidirectional"))
    )
    (net (code "68") (name "/FAN0") (class "Default")
      (node (ref "R24") (pin "2") (pinfunction "2_2") (pintype "passive"))
      (node (ref "R42") (pin "1") (pinfunction "1_1") (pintype "passive"))
      (node (ref "TP12") (pin "TP") (pinfunction "TP_TP") (pintype "input"))
      (node (ref "U1") (pin "127") (pinfunction "PC23/TIOA4_127") (pintype "bidirectional"))
    )
    (net (code "69") (name "/FAN0-") (class "Default")
      (node (ref "D18") (pin "A") (pinfunction "A_A") (pintype "passive"))
      (node (ref "J25") (pin "1") (pinfunction "S_1") (pintype "passive"))
      (node (ref "TR5") (pin "3") (pinfunction "D_3") (pintype "bidirectional"))
    )
    (net (code "70") (name "/FAN1") (class "Default")
      (node (ref "R43") (pin "1") (pinfunction "1_1") (pintype "passive"))
      (node (ref "TP13") (pin "TP") (pinfunction "TP_TP") (pintype "input"))
      (node (ref "U1") (pin "13") (pinfunction "PC26/TIOA4_13") (pintype "bidirectional"))
    )
    (net (code "71") (name "/FAN1-") (class "Default")
      (node (ref "D8") (pin "A") (pinfunction "A_A") (pintype "passive"))
      (node (ref "J29") (pin "1") (pinfunction "S_1") (pintype "passive"))
      (node (ref "TR9") (pin "3") (pinfunction "D_3") (pintype "bidirectional"))
    )
    (net (code "72") (name "/FAN2") (class "Default")
      (node (ref "R66") (pin "1") (pinfunction "1_1") (pintype "passive"))
      (node (ref "R91") (pin "2") (pinfunction "2_2") (pintype "passive"))
      (node (ref "TP14") (pin "TP") (pinfunction "TP_TP") (pintype "input"))
      (node (ref "U1") (pin "102") (pinfunction "PA0/PGMEN0/TIOA0_102") (pintype "bidirectional"))
    )
    (net (code "73") (name "/FAN2-") (class "Default")
      (node (ref "D21") (pin "A") (pinfunction "A_A") (pintype "passive"))
      (node (ref "J2") (pin "1") (pinfunction "S_1") (pintype "passive"))
      (node (ref "TR1") (pin "3") (pinfunction "D_3") (pintype "bidirectional"))
    )
    (net (code "74") (name "/GPIO2") (class "Default")
      (node (ref "J16") (pin "9") (pinfunction "9_9") (pintype "passive"))
      (node (ref "J39") (pin "7") (pinfunction "7_7") (pintype "passive"))
      (node (ref "U4") (pin "11") (pinfunction "GPIO2_11") (pintype "bidirectional"))
    )
    (net (code "75") (name "/GPIO5") (class "Default")
      (node (ref "J16") (pin "13") (pinfunction "13_13") (pintype "passive"))
      (node (ref "J39") (pin "2") (pinfunction "2_2") (pintype "passive"))
      (node (ref "U4") (pin "13") (pinfunction "GPIO5_13") (pintype "bidirectional"))
    )
    (net (code "76") (name "/GPIO16") (class "Default")
      (node (ref "J16") (pin "8") (pinfunction "8_8") (pintype "passive"))
      (node (ref "J39") (pin "6") (pinfunction "6_6") (pintype "passive"))
      (node (ref "U4") (pin "4") (pinfunction "GPIO16_4") (pintype "bidirectional"))
    )
    (net (code "77") (name "/HEATER0") (class "Default")
      (node (ref "TP6") (pin "TP") (pinfunction "TP_TP") (pintype "input"))
      (node (ref "U1") (pin "23") (pinfunction "PA19/PGMD7/PWML0_23") (pintype "bidirectional"))
      (node (ref "U11") (pin "5") (pinfunction "I0_5") (pintype "input"))
    )
    (net (code "78") (name "/HEATER1") (class "Default")
      (node (ref "TP7") (pin "TP") (pinfunction "TP_TP") (pintype "input"))
      (node (ref "U1") (pin "22") (pinfunction "PA20/PMGD8/PWML1_22") (pintype "bidirectional"))
      (node (ref "U11") (pin "8") (pinfunction "I0_8") (pintype "input"))
    )
    (net (code "79") (name "/HEATER2") (class "Default")
      (node (ref "TP8") (pin "TP") (pinfunction "TP_TP") (pintype "input"))
      (node (ref "U1") (pin "45") (pinfunction "PA16/PGMD4/PWML2_45") (pintype "bidirectional"))
      (node (ref "U11") (pin "11") (pinfunction "I0_11") (pintype "input"))
    )
    (net (code "80") (name "/HEATER3") (class "Default")
      (node (ref "J1") (pin "8") (pinfunction "S_8") (pintype "passive"))
      (node (ref "U1") (pin "40") (pinfunction "PC3/PWML3_40") (pintype "bidirectional"))
    )
    (net (code "81") (name "/HEATER4") (class "Default")
      (node (ref "J1") (pin "13") (pinfunction "S_13") (pintype "passive"))
      (node (ref "U1") (pin "58") (pinfunction "PC5/TIOA6_58") (pintype "bidirectional"))
    )
    (net (code "82") (name "/HEATER5") (class "Default")
      (node (ref "J1") (pin "18") (pinfunction "S_18") (pintype "passive"))
      (node (ref "U1") (pin "82") (pinfunction "PC8/TIOA7_82") (pintype "bidirectional"))
    )
    (net (code "83") (name "/HEATER6") (class "Default")
      (node (ref "J1") (pin "23") (pinfunction "S_23") (pintype "passive"))
      (node (ref "U1") (pin "94") (pinfunction "PC11/TIOA8_94") (pintype "bidirectional"))
    )
    (net (code "84") (name "/HEATER7") (class "Default")
      (node (ref "J1") (pin "31") (pinfunction "S_31") (pintype "passive"))
      (node (ref "U1") (pin "49") (pinfunction "PA15/PGMD3/TIOA1_49") (pintype "bidirectional"))
    )
    (net (code "85") (name "/LCD_DB4") (class "Default")
      (node (ref "P2") (pin "10") (pinfunction "S_10") (pintype "passive"))
      (node (ref "U1") (pin "63") (pinfunction "PD21_63") (pintype "bidirectional"))
    )
    (net (code "86") (name "/LCD_DB5") (class "Default")
      (node (ref "P2") (pin "9") (pinfunction "S_9") (pintype "passive"))
      (node (ref "U1") (pin "65") (pinfunction "PD20_65") (pintype "bidirectional"))
    )
    (net (code "87") (name "/LCD_DB6") (class "Default")
      (node (ref "P2") (pin "7") (pinfunction "S_7") (pintype "passive"))
      (node (ref "U1") (pin "67") (pinfunction "PD19_67") (pintype "bidirectional"))
    )
    (net (code "88") (name "/LCD_DB7") (class "Default")
      (node (ref "P2") (pin "5") (pinfunction "S_5") (pintype "passive"))
      (node (ref "U1") (pin "69") (pinfunction "PD18_69") (pintype "bidirectional"))
    )
    (net (code "89") (name "/LCD_E") (class "Default")
      (node (ref "P2") (pin "8") (pinfunction "S_8") (pintype "passive"))
      (node (ref "U1") (pin "59") (pinfunction "PA25/PGMD13_59") (pintype "bidirectional"))
    )
    (net (code "90") (name "/LCD_RS") (class "Default")
      (node (ref "P2") (pin "6") (pinfunction "S_6") (pintype "passive"))
      (node (ref "U1") (pin "76") (pinfunction "PC28_76") (pintype "bidirectional"))
    )
    (net (code "91") (name "/MCCDA") (class "Default")
      (node (ref "R48") (pin "1") (pinfunction "1_1") (pintype "passive"))
      (node (ref "U1") (pin "112") (pinfunction "PA28/MCCDA_112") (pintype "bidirectional"))
    )
    (net (code "92") (name "/MCCK") (class "Default")
      (node (ref "R68") (pin "1") (pinfunction "1_1") (pintype "passive"))
      (node (ref "U1") (pin "129") (pinfunction "PA29/MCCK_129") (pintype "bidirectional"))
    )
    (net (code "93") (name "/MCDA0") (class "Default")
      (node (ref "R77") (pin "1") (pinfunction "1_1") (pintype "passive"))
      (node (ref "U1") (pin "116") (pinfunction "PA30/MCDA0_116") (pintype "bidirectional"))
    )
    (net (code "94") (name "/MCDA1") (class "Default")
      (node (ref "R78") (pin "1") (pinfunction "1_1") (pintype "passive"))
      (node (ref "U1") (pin "118") (pinfunction "PA31/MCDA0_118") (pintype "bidirectional"))
    )
    (net (code "95") (name "/MCDA2") (class "Default")
      (node (ref "R22") (pin "1") (pinfunction "1_1") (pintype "passive"))
      (node (ref "U1") (pin "62") (pinfunction "PA26/PGMD14/MCDA2_62") (pintype "bidirectional"))
    )
    (net (code "96") (name "/MCDA3") (class "Default")
      (node (ref "R25") (pin "1") (pinfunction "1_1") (pintype "passive"))
      (node (ref "U1") (pin "70") (pinfunction "PA27/PGMD15/MCDA3_70") (pintype "bidirectional"))
    )
    (net (code "97") (name "/MISO") (class "Default")
      (node (ref "R101") (pin "1") (pinfunction "1_1") (pintype "passive"))
      (node (ref "U1") (pin "68") (pinfunction "PA12/PGMD0/MISO_68") (pintype "bidirectional"))
    )
    (net (code "98") (name "/MISO_ESP") (class "Default")
      (node (ref "J16") (pin "4") (pinfunction "4_4") (pintype "passive"))
      (node (ref "R101") (pin "2") (pinfunction "2_2") (pintype "passive"))
      (node (ref "U4") (pin "6") (pinfunction "GPIO12_6") (pintype "bidirectional"))
    )
    (net (code "99") (name "/MOSI") (class "Default")
      (node (ref "R105") (pin "1") (pinfunction "1_1") (pintype "passive"))
      (node (ref "U1") (pin "42") (pinfunction "PA13/PGMD1/MOSI_42") (pintype "bidirectional"))
    )
    (net (code "100") (name "/MOSI_ESP") (class "Default")
      (node (ref "J16") (pin "5") (pinfunction "5_5") (pintype "passive"))
      (node (ref "R105") (pin "2") (pinfunction "2_2") (pintype "passive"))
      (node (ref "U4") (pin "7") (pinfunction "GPIO13_7") (pintype "bidirectional"))
    )
    (net (code "101") (name "/NPCS0") (class "Default")
      (node (ref "IC1") (pin "1") (pinfunction "CLR_1") (pintype "input"))
      (node (ref "R99") (pin "2") (pinfunction "2_2") (pintype "passive"))
      (node (ref "U1") (pin "64") (pinfunction "PA11/PGMM3/NPCS0_64") (pintype "bidirectional"))
    )
    (net (code "102") (name "/NPCS0_CONN") (class "Default")
      (node (ref "J16") (pin "11") (pinfunction "11_11") (pintype "passive"))
      (node (ref "R99") (pin "1") (pinfunction "1_1") (pintype "passive"))
      (node (ref "U4") (pin "10") (pinfunction "GPIO15_10") (pintype "bidirectional"))
    )
    (net (code "103") (name "/PB4{slash}TDI") (class "Default")
      (node (ref "J21") (pin "8") (pinfunction "NC/TDI_8") (pintype "bidirectional"))
      (node (ref "R36") (pin "1") (pinfunction "1_1") (pintype "passive"))
      (node (ref "U1") (pin "105") (pinfunction "PB4/TDI_105") (pintype "bidirectional"))
    )
    (net (code "104") (name "/PB6{slash}TMS") (class "Default")
      (node (ref "J1") (pin "29") (pinfunction "S_29") (pintype "passive"))
      (node (ref "J21") (pin "2") (pinfunction "SWDIO/TMS_2") (pintype "bidirectional"))
      (node (ref "R52") (pin "1") (pinfunction "1_1") (pintype "passive"))
      (node (ref "U1") (pin "79") (pinfunction "PB6/TMS_79") (pintype "bidirectional"))
    )
    (net (code "105") (name "/PB7{slash}TCK") (class "Default")
      (node (ref "J21") (pin "4") (pinfunction "SWDCLK/TCK_4") (pintype "bidirectional"))
      (node (ref "R49") (pin "1") (pinfunction "1_1") (pintype "passive"))
      (node (ref "R83") (pin "1") (pinfunction "1_1") (pintype "passive"))
      (node (ref "U1") (pin "89") (pinfunction "PB7/TCK_89") (pintype "bidirectional"))
    )
    (net (code "106") (name "/PS_ON") (class "Default")
      (node (ref "R14") (pin "1") (pinfunction "1_1") (pintype "passive"))
      (node (ref "R54") (pin "2") (pinfunction "2_2") (pintype "passive"))
      (node (ref "U1") (pin "106") (pinfunction "PD15_106") (pintype "bidirectional"))
    )
    (net (code "107") (name "/PS_ON_IN") (class "Default")
      (node (ref "J20") (pin "2") (pinfunction "S_2") (pintype "passive"))
      (node (ref "TR7") (pin "3") (pinfunction "D_3") (pintype "bidirectional"))
    )
    (net (code "108") (name "/RESET") (class "Default")
      (node (ref "D25") (pin "A") (pinfunction "A_A") (pintype "passive"))
      (node (ref "J21") (pin "10") (pinfunction "~{RESET}_10") (pintype "bidirectional"))
      (node (ref "R106") (pin "1") (pinfunction "1_1") (pintype "passive"))
      (node (ref "U1") (pin "83") (pinfunction "NRST_83") (pintype "bidirectional"))
    )
    (net (code "109") (name "/RESET_EXT") (class "Default")
      (node (ref "J1") (pin "44") (pinfunction "S_44") (pintype "passive"))
      (node (ref "R107") (pin "1") (pinfunction "1_1") (pintype "passive"))
    )
    (net (code "110") (name "/SAM_TFR_RDY") (class "Default")
      (node (ref "IC1") (pin "3") (pinfunction "CLK_3") (pintype "input"))
      (node (ref "R82") (pin "1") (pinfunction "1_1") (pintype "passive"))
      (node (ref "U1") (pin "34") (pinfunction "PD30_34") (pintype "bidirectional"))
    )
    (net (code "111") (name "/SCK_ESP") (class "Default")
      (node (ref "J16") (pin "3") (pinfunction "3_3") (pintype "passive"))
    )
    (net (code "112") (name "/SD_CD") (class "Default")
      (node (ref "R79") (pin "1") (pinfunction "1_1") (pintype "passive"))
      (node (ref "U1") (pin "122") (pinfunction "PC21_122") (pintype "bidirectional"))
    )
    (net (code "113") (name "/SG_TST") (class "Default")
      (node (ref "J21") (pin "6") (pinfunction "SWO/TDO_6") (pintype "bidirectional"))
      (node (ref "U1") (pin "109") (pinfunction "PB5/TDO_109") (pintype "bidirectional"))
    )
    (net (code "114") (name "/SG_TST_E0") (class "Default")
      (node (ref "U13") (pin "9") (pinfunction "I0_9") (pintype "input"))
      (node (ref "U8") (pin "38") (pinfunction "SG_TST_38") (pintype "output"))
    )
    (net (code "115") (name "/SG_TST_E1") (class "Default")
      (node (ref "U13") (pin "5") (pinfunction "I1_5") (pintype "input"))
      (node (ref "U9") (pin "38") (pinfunction "SG_TST_38") (pintype "output"))
    )
    (net (code "116") (name "/SG_TST_X") (class "Default")
      (node (ref "U13") (pin "1") (pinfunction "I0_1") (pintype "input"))
      (node (ref "U5") (pin "38") (pinfunction "SG_TST_38") (pintype "output"))
    )
    (net (code "117") (name "/SG_TST_Y") (class "Default")
      (node (ref "U13") (pin "2") (pinfunction "I1_2") (pintype "input"))
      (node (ref "U7") (pin "38") (pinfunction "SG_TST_38") (pintype "output"))
    )
    (net (code "118") (name "/SG_TST_Z") (class "Default")
      (node (ref "U13") (pin "4") (pinfunction "I0_4") (pintype "input"))
      (node (ref "U6") (pin "38") (pinfunction "SG_TST_38") (pintype "output"))
    )
    (net (code "119") (name "/SPCK") (class "Default")
      (node (ref "R100") (pin "1") (pinfunction "1_1") (pintype "passive"))
      (node (ref "U1") (pin "51") (pinfunction "PA14/PGMD2/SPCK_51") (pintype "bidirectional"))
    )
    (net (code "120") (name "/SPCK_ESP") (class "Default")
      (node (ref "R100") (pin "2") (pinfunction "2_2") (pintype "passive"))
      (node (ref "U4") (pin "5") (pinfunction "GPIO14_5") (pintype "bidirectional"))
    )
    (net (code "121") (name "/SPI0_CS0") (class "Default")
      (node (ref "P1") (pin "3") (pinfunction "S_3") (pintype "passive"))
      (node (ref "U1") (pin "130") (pinfunction "PC24/TIOB3_130") (pintype "bidirectional"))
    )
    (net (code "122") (name "/SPI0_CS1") (class "Default")
      (node (ref "J37") (pin "3") (pinfunction "S_3") (pintype "passive"))
      (node (ref "U1") (pin "26") (pinfunction "PB2/CTS0_26") (pintype "bidirectional"))
    )
    (net (code "123") (name "/SPI0_CS2") (class "Default")
      (node (ref "J37") (pin "1") (pinfunction "S_1") (pintype "passive"))
      (node (ref "U1") (pin "111") (pinfunction "PC18_111") (pintype "bidirectional"))
    )
    (net (code "124") (name "/SPI0_MISO") (class "Default")
      (node (ref "J1") (pin "49") (pinfunction "S_49") (pintype "passive"))
      (node (ref "J37") (pin "6") (pinfunction "S_6") (pintype "passive"))
      (node (ref "P1") (pin "6") (pinfunction "S_6") (pintype "passive"))
      (node (ref "U1") (pin "21") (pinfunction "PB0/RXD0_21") (pintype "bidirectional"))
    )
    (net (code "125") (name "/SPI0_MOSI") (class "Default")
      (node (ref "J1") (pin "48") (pinfunction "S_48") (pintype "passive"))
      (node (ref "J37") (pin "5") (pinfunction "S_5") (pintype "passive"))
      (node (ref "P1") (pin "5") (pinfunction "S_5") (pintype "passive"))
      (node (ref "U1") (pin "20") (pinfunction "PB1/TXD0_20") (pintype "bidirectional"))
    )
    (net (code "126") (name "/SPI0_SCK") (class "Default")
      (node (ref "J1") (pin "47") (pinfunction "S_47") (pintype "passive"))
      (node (ref "J37") (pin "4") (pinfunction "S_4") (pintype "passive"))
      (node (ref "P1") (pin "4") (pinfunction "S_4") (pintype "passive"))
      (node (ref "U1") (pin "144") (pinfunction "PB13/SCK0/DAC0_144") (pintype "bidirectional"))
    )
    (net (code "127") (name "/SPI1_MISO") (class "Default")
      (node (ref "J1") (pin "34") (pinfunction "S_34") (pintype "passive"))
      (node (ref "U1") (pin "32") (pinfunction "PA21/PGMD9/RXD1_32") (pintype "bidirectional"))
      (node (ref "U5") (pin "14") (pinfunction "SDO_14") (pintype "tri_state"))
      (node (ref "U6") (pin "14") (pinfunction "SDO_14") (pintype "tri_state"))
      (node (ref "U7") (pin "14") (pinfunction "SDO_14") (pintype "tri_state"))
      (node (ref "U8") (pin "14") (pinfunction "SDO_14") (pintype "tri_state"))
      (node (ref "U9") (pin "14") (pinfunction "SDO_14") (pintype "tri_state"))
    )
    (net (code "128") (name "/SPI1_MOSI") (class "Default")
      (node (ref "U1") (pin "37") (pinfunction "PA22/PGMD10/TXD1_37") (pintype "bidirectional"))
      (node (ref "U10") (pin "9") (pinfunction "I_9") (pintype "input"))
    )
    (net (code "129") (name "/SPI1_MOSI_BUF") (class "Default")
      (node (ref "J1") (pin "33") (pinfunction "S_33") (pintype "passive"))
      (node (ref "U10") (pin "8") (pinfunction "O_8") (pintype "tri_state"))
      (node (ref "U5") (pin "15") (pinfunction "SDI_15") (pintype "input"))
      (node (ref "U6") (pin "15") (pinfunction "SDI_15") (pintype "input"))
      (node (ref "U7") (pin "15") (pinfunction "SDI_15") (pintype "input"))
      (node (ref "U8") (pin "15") (pinfunction "SDI_15") (pintype "input"))
      (node (ref "U9") (pin "15") (pinfunction "SDI_15") (pintype "input"))
    )
    (net (code "130") (name "/SPI1_SCK") (class "Default")
      (node (ref "U1") (pin "46") (pinfunction "PA23/PGMD11/SCK1_46") (pintype "bidirectional"))
      (node (ref "U10") (pin "2") (pinfunction "I_2") (pintype "input"))
    )
    (net (code "131") (name "/SPI1_SCK_BUF") (class "Default")
      (node (ref "R30") (pin "1") (pinfunction "1_1") (pintype "passive"))
      (node (ref "TP15") (pin "TP") (pinfunction "TP_TP") (pintype "input"))
      (node (ref "U5") (pin "16") (pinfunction "SCK_16") (pintype "input"))
      (node (ref "U6") (pin "16") (pinfunction "SCK_16") (pintype "input"))
      (node (ref "U7") (pin "16") (pinfunction "SCK_16") (pintype "input"))
      (node (ref "U8") (pin "16") (pinfunction "SCK_16") (pintype "input"))
      (node (ref "U9") (pin "16") (pinfunction "SCK_16") (pintype "input"))
    )
    (net (code "132") (name "/SPI1_SCK_BUF_EXP") (class "Default")
      (node (ref "J1") (pin "32") (pinfunction "S_32") (pintype "passive"))
      (node (ref "R30") (pin "2") (pinfunction "2_2") (pintype "passive"))
      (node (ref "U10") (pin "3") (pinfunction "O_3") (pintype "tri_state"))
    )
    (net (code "133") (name "/THERMISTOR0") (class "Default")
      (node (ref "J5") (pin "1") (pinfunction "S_1") (pintype "passive"))
      (node (ref "R12") (pin "1") (pinfunction "1_1") (pintype "passive"))
      (node (ref "R21") (pin "1") (pinfunction "1_1") (pintype "passive"))
    )
    (net (code "134") (name "/THERMISTOR1") (class "Default")
      (node (ref "J12") (pin "1") (pinfunction "S_1") (pintype "passive"))
      (node (ref "R11") (pin "1") (pinfunction "1_1") (pintype "passive"))
      (node (ref "R19") (pin "1") (pinfunction "1_1") (pintype "passive"))
    )
    (net (code "135") (name "/THERMISTOR2") (class "Default")
      (node (ref "J14") (pin "1") (pinfunction "S_1") (pintype "passive"))
      (node (ref "R10") (pin "1") (pinfunction "1_1") (pintype "passive"))
      (node (ref "R53") (pin "1") (pinfunction "1_1") (pintype "passive"))
    )
    (net (code "136") (name "/THERMISTOR3") (class "Default")
      (node (ref "J1") (pin "35") (pinfunction "S_35") (pintype "passive"))
      (node (ref "R9") (pin "1") (pinfunction "1_1") (pintype "passive"))
    )
    (net (code "137") (name "/THERMISTOR4") (class "Default")
      (node (ref "J1") (pin "36") (pinfunction "S_36") (pintype "passive"))
      (node (ref "R8") (pin "1") (pinfunction "1_1") (pintype "passive"))
    )
    (net (code "138") (name "/THERMISTOR5") (class "Default")
      (node (ref "J1") (pin "37") (pinfunction "S_37") (pintype "passive"))
      (node (ref "R7") (pin "1") (pinfunction "1_1") (pintype "passive"))
    )
    (net (code "139") (name "/THERMISTOR6") (class "Default")
      (node (ref "J1") (pin "38") (pinfunction "S_38") (pintype "passive"))
      (node (ref "R6") (pin "1") (pinfunction "1_1") (pintype "passive"))
    )
    (net (code "140") (name "/THERMISTOR7") (class "Default")
      (node (ref "J1") (pin "39") (pinfunction "S_39") (pintype "passive"))
      (node (ref "R50") (pin "1") (pinfunction "1_1") (pintype "passive"))
    )
    (net (code "141") (name "/TWCK0") (class "Default")
      (node (ref "J1") (pin "46") (pinfunction "S_46") (pintype "passive"))
      (node (ref "U1") (pin "77") (pinfunction "PA4/PGMNCMD/TWCK0_77") (pintype "bidirectional"))
    )
    (net (code "142") (name "/TWD0") (class "Default")
      (node (ref "J1") (pin "45") (pinfunction "S_45") (pintype "passive"))
      (node (ref "U1") (pin "91") (pinfunction "PA3/TWD0_91") (pintype "bidirectional"))
    )
    (net (code "143") (name "/URXD0") (class "Default")
      (node (ref "J30") (pin "3") (pinfunction "S_3") (pintype "passive"))
      (node (ref "P1") (pin "9") (pinfunction "S_9") (pintype "passive"))
      (node (ref "U1") (pin "75") (pinfunction "PA9/PGMM1_75") (pintype "bidirectional"))
    )
    (net (code "144") (name "/URXD1") (class "Default")
      (node (ref "R102") (pin "2") (pinfunction "2_2") (pintype "passive"))
      (node (ref "U1") (pin "73") (pinfunction "PA5/PGMRDY/URXD1_73") (pintype "bidirectional"))
    )
    (net (code "145") (name "/URXD1_CONN") (class "Default")
      (node (ref "J16") (pin "15") (pinfunction "15_15") (pintype "passive"))
      (node (ref "J39") (pin "3") (pinfunction "3_3") (pintype "passive"))
      (node (ref "R102") (pin "1") (pinfunction "1_1") (pintype "passive"))
      (node (ref "U4") (pin "16") (pinfunction "TXD_16") (pintype "output"))
    )
    (net (code "146") (name "/USB_PWR_MON") (class "Default")
      (node (ref "C82") (pin "1") (pinfunction "1_1") (pintype "passive"))
      (node (ref "R31") (pin "2") (pinfunction "2_2") (pintype "passive"))
      (node (ref "R37") (pin "1") (pinfunction "1_1") (pintype "passive"))
      (node (ref "U1") (pin "124") (pinfunction "PC22_124") (pintype "bidirectional"))
    )
    (net (code "147") (name "/UTXD0") (class "Default")
      (node (ref "J30") (pin "4") (pinfunction "S_4") (pintype "passive"))
      (node (ref "P1") (pin "10") (pinfunction "S_10") (pintype "passive"))
      (node (ref "U1") (pin "66") (pinfunction "PA10/PGMM2/UTXD0_66") (pintype "bidirectional"))
    )
    (net (code "148") (name "/UTXD1") (class "Default")
      (node (ref "R103") (pin "2") (pinfunction "2_2") (pintype "passive"))
      (node (ref "U1") (pin "114") (pinfunction "PA6/PGMNOE/UTXD1_114") (pintype "bidirectional"))
    )
    (net (code "149") (name "/UTXD1_CONN") (class "Default")
      (node (ref "C83") (pin "1") (pinfunction "1_1") (pintype "passive"))
      (node (ref "J16") (pin "14") (pinfunction "14_14") (pintype "passive"))
      (node (ref "J39") (pin "5") (pinfunction "5_5") (pintype "passive"))
      (node (ref "R103") (pin "1") (pinfunction "1_1") (pintype "passive"))
      (node (ref "U4") (pin "15") (pinfunction "RXD_15") (pintype "input"))
    )
    (net (code "150") (name "/VBUS") (class "Default")
      (node (ref "D13") (pin "A") (pinfunction "A_A") (pintype "passive"))
      (node (ref "D3") (pin "A") (pinfunction "A_A") (pintype "passive"))
      (node (ref "J22") (pin "VBUS") (pinfunction "VBUS_VBUS") (pintype "power_in"))
      (node (ref "R37") (pin "2") (pinfunction "2_2") (pintype "passive"))
    )
    (net (code "151") (name "/VSSA") (class "Default")
      (node (ref "F1") (pin "2") (pinfunction "2_2") (pintype "bidirectional"))
      (node (ref "J1") (pin "40") (pinfunction "S_40") (pintype "passive"))
      (node (ref "J12") (pin "2") (pinfunction "S_2") (pintype "passive"))
      (node (ref "J14") (pin "2") (pinfunction "S_2") (pintype "passive"))
      (node (ref "J5") (pin "2") (pinfunction "S_2") (pintype "passive"))
      (node (ref "R83") (pin "2") (pinfunction "2_2") (pintype "passive"))
    )
    (net (code "152") (name "/V_BED") (class "Default")
      (node (ref "C91") (pin "1") (pinfunction "1_1") (pintype "passive"))
      (node (ref "F4") (pin "2") (pinfunction "2_2") (pintype "passive"))
      (node (ref "R65") (pin "2") (pinfunction "2_2") (pintype "passive"))
      (node (ref "U$1") (pin "2") (pinfunction "1_2") (pintype "passive"))
    )
    (net (code "153") (name "/V_FAN") (class "Default")
      (node (ref "D18") (pin "C") (pinfunction "C_C") (pintype "passive"))
      (node (ref "D21") (pin "C") (pinfunction "C_C") (pintype "passive"))
      (node (ref "D8") (pin "C") (pinfunction "C_C") (pintype "passive"))
      (node (ref "J2") (pin "2") (pinfunction "S_2") (pintype "passive"))
      (node (ref "J24") (pin "2") (pinfunction "S_2") (pintype "passive"))
      (node (ref "J25") (pin "2") (pinfunction "S_2") (pintype "passive"))
      (node (ref "J29") (pin "2") (pinfunction "S_2") (pintype "passive"))
      (node (ref "J3") (pin "2") (pinfunction "2_2") (pintype "passive"))
      (node (ref "J31") (pin "2") (pinfunction "S_2") (pintype "passive"))
    )
    (net (code "154") (name "/V_FUSED") (class "Default")
      (node (ref "C101") (pin "1") (pinfunction "1_1") (pintype "passive"))
      (node (ref "C102") (pin "+") (pinfunction "+_+") (pintype "passive"))
      (node (ref "C103") (pin "1") (pinfunction "1_1") (pintype "passive"))
      (node (ref "C22") (pin "+") (pinfunction "+_+") (pintype "passive"))
      (node (ref "C23") (pin "+") (pinfunction "+_+") (pintype "passive"))
      (node (ref "C24") (pin "1") (pinfunction "1_1") (pintype "passive"))
      (node (ref "C25") (pin "1") (pinfunction "1_1") (pintype "passive"))
      (node (ref "C32") (pin "+") (pinfunction "+_+") (pintype "passive"))
      (node (ref "C33") (pin "+") (pinfunction "+_+") (pintype "passive"))
      (node (ref "C34") (pin "1") (pinfunction "1_1") (pintype "passive"))
      (node (ref "C35") (pin "1") (pinfunction "1_1") (pintype "passive"))
      (node (ref "C75") (pin "1") (pinfunction "1_1") (pintype "passive"))
      (node (ref "C76") (pin "1") (pinfunction "1_1") (pintype "passive"))
      (node (ref "C77") (pin "1") (pinfunction "1_1") (pintype "passive"))
      (node (ref "C78") (pin "1") (pinfunction "1_1") (pintype "passive"))
      (node (ref "C94") (pin "1") (pinfunction "1_1") (pintype "passive"))
      (node (ref "D1") (pin "A") (pinfunction "A_A") (pintype "passive"))
      (node (ref "F3") (pin "2") (pinfunction "2_2") (pintype "passive"))
      (node (ref "J11") (pin "1") (pinfunction "1_1") (pintype "passive"))
      (node (ref "J13") (pin "1") (pinfunction "1_1") (pintype "passive"))
      (node (ref "R67") (pin "2") (pinfunction "2_2") (pintype "passive"))
      (node (ref "R80") (pin "2") (pinfunction "2_2") (pintype "passive"))
      (node (ref "R98") (pin "2") (pinfunction "2_2") (pintype "passive"))
      (node (ref "U5") (pin "1") (pinfunction "NC1_1") (pintype "input"))
      (node (ref "U5") (pin "30") (pinfunction "VSB_30") (pintype "input"))
      (node (ref "U5") (pin "33") (pinfunction "NC33_33") (pintype "input"))
      (node (ref "U5") (pin "36") (pinfunction "VS_36") (pintype "input"))
      (node (ref "U5") (pin "4") (pinfunction "VSA_4") (pintype "input"))
      (node (ref "U6") (pin "1") (pinfunction "NC1_1") (pintype "input"))
      (node (ref "U6") (pin "30") (pinfunction "VSB_30") (pintype "input"))
      (node (ref "U6") (pin "33") (pinfunction "NC33_33") (pintype "input"))
      (node (ref "U6") (pin "36") (pinfunction "VS_36") (pintype "input"))
      (node (ref "U6") (pin "4") (pinfunction "VSA_4") (pintype "input"))
      (node (ref "U7") (pin "1") (pinfunction "NC1_1") (pintype "input"))
      (node (ref "U7") (pin "30") (pinfunction "VSB_30") (pintype "input"))
      (node (ref "U7") (pin "33") (pinfunction "NC33_33") (pintype "input"))
      (node (ref "U7") (pin "36") (pinfunction "VS_36") (pintype "input"))
      (node (ref "U7") (pin "4") (pinfunction "VSA_4") (pintype "input"))
      (node (ref "U8") (pin "1") (pinfunction "NC1_1") (pintype "input"))
      (node (ref "U8") (pin "30") (pinfunction "VSB_30") (pintype "input"))
      (node (ref "U8") (pin "33") (pinfunction "NC33_33") (pintype "input"))
      (node (ref "U8") (pin "36") (pinfunction "VS_36") (pintype "input"))
      (node (ref "U8") (pin "4") (pinfunction "VSA_4") (pintype "input"))
      (node (ref "U9") (pin "1") (pinfunction "NC1_1") (pintype "input"))
      (node (ref "U9") (pin "30") (pinfunction "VSB_30") (pintype "input"))
      (node (ref "U9") (pin "33") (pinfunction "NC33_33") (pintype "input"))
      (node (ref "U9") (pin "36") (pinfunction "VS_36") (pintype "input"))
      (node (ref "U9") (pin "4") (pinfunction "VSA_4") (pintype "input"))
    )
    (net (code "155") (name "/V_IN") (class "Default")
      (node (ref "D15") (pin "A") (pinfunction "A_A") (pintype "passive"))
      (node (ref "F2") (pin "1") (pinfunction "1_1") (pintype "passive"))
      (node (ref "F3") (pin "1") (pinfunction "1_1") (pintype "passive"))
      (node (ref "F4") (pin "1") (pinfunction "1_1") (pintype "passive"))
      (node (ref "J23") (pin "1") (pinfunction "1_1") (pintype "passive"))
    )
    (net (code "156") (name "/X_DIR") (class "Default")
      (node (ref "TP3") (pin "2") (pinfunction "TP1_2") (pintype "input"))
      (node (ref "U1") (pin "98") (pinfunction "PD11_98") (pintype "bidirectional"))
      (node (ref "U5") (pin "41") (pinfunction "DIR_41") (pintype "input"))
    )
    (net (code "157") (name "/X_EN") (class "Default")
      (node (ref "TP3") (pin "3") (pinfunction "TP2_3") (pintype "input"))
      (node (ref "U1") (pin "84") (pinfunction "PD14_84") (pintype "bidirectional"))
      (node (ref "U5") (pin "18") (pinfunction "~{CS}_18") (pintype "input"))
    )
    (net (code "158") (name "/X_MOT_1A") (class "Default")
      (node (ref "C88") (pin "1") (pinfunction "1_1") (pintype "passive"))
      (node (ref "J9") (pin "2") (pinfunction "S_2") (pintype "passive"))
      (node (ref "U5") (pin "10") (pinfunction "OA2_10") (pintype "output"))
      (node (ref "U5") (pin "5") (pinfunction "OA2_5") (pintype "output"))
    )
    (net (code "159") (name "/X_MOT_1B") (class "Default")
      (node (ref "C85") (pin "1") (pinfunction "1_1") (pintype "passive"))
      (node (ref "J9") (pin "1") (pinfunction "S_1") (pintype "passive"))
      (node (ref "U5") (pin "2") (pinfunction "OA1_2") (pintype "output"))
      (node (ref "U5") (pin "7") (pinfunction "OA1_7") (pintype "output"))
    )
    (net (code "160") (name "/X_MOT_2A") (class "Default")
      (node (ref "C107") (pin "1") (pinfunction "1_1") (pintype "passive"))
      (node (ref "J9") (pin "3") (pinfunction "S_3") (pintype "passive"))
      (node (ref "U5") (pin "26") (pinfunction "OB1_26") (pintype "output"))
      (node (ref "U5") (pin "31") (pinfunction "OB1_31") (pintype "output"))
    )
    (net (code "161") (name "/X_MOT_2B") (class "Default")
      (node (ref "C113") (pin "1") (pinfunction "1_1") (pintype "passive"))
      (node (ref "J9") (pin "4") (pinfunction "S_4") (pintype "passive"))
      (node (ref "U5") (pin "23") (pinfunction "OB2_23") (pintype "output"))
      (node (ref "U5") (pin "28") (pinfunction "OB2_28") (pintype "output"))
    )
    (net (code "162") (name "/X_STEP") (class "Default")
      (node (ref "TP3") (pin "1") (pinfunction "TP_1") (pintype "input"))
      (node (ref "U1") (pin "121") (pinfunction "PD6_121") (pintype "bidirectional"))
      (node (ref "U5") (pin "42") (pinfunction "STEP_42") (pintype "input"))
    )
    (net (code "163") (name "/X_STOP") (class "Default")
      (node (ref "C40") (pin "1") (pinfunction "1_1") (pintype "passive"))
      (node (ref "D23") (pin "1") (pinfunction "A1_1") (pintype "passive"))
      (node (ref "R56") (pin "2") (pinfunction "2_2") (pintype "passive"))
      (node (ref "U1") (pin "97") (pinfunction "PC14_97") (pintype "bidirectional"))
    )
    (net (code "164") (name "/X_STOP_CON") (class "Default")
      (node (ref "J33") (pin "1") (pinfunction "S_1") (pintype "passive"))
    )
    (net (code "165") (name "/X_STOP_CONN") (class "Default")
      (node (ref "D12") (pin "C") (pinfunction "C_C") (pintype "passive"))
      (node (ref "R56") (pin "1") (pinfunction "1_1") (pintype "passive"))
    )
    (net (code "166") (name "/Y_DIR") (class "Default")
      (node (ref "TP2") (pin "2") (pinfunction "TP1_2") (pintype "input"))
      (node (ref "U1") (pin "92") (pinfunction "PD12_92") (pintype "bidirectional"))
      (node (ref "U7") (pin "41") (pinfunction "DIR_41") (pintype "input"))
    )
    (net (code "167") (name "/Y_EN") (class "Default")
      (node (ref "TP2") (pin "3") (pinfunction "TP2_3") (pintype "input"))
      (node (ref "U1") (pin "86") (pinfunction "PC9_86") (pintype "bidirectional"))
      (node (ref "U7") (pin "18") (pinfunction "~{CS}_18") (pintype "input"))
    )
    (net (code "168") (name "/Y_MOT_1A") (class "Default")
      (node (ref "C89") (pin "1") (pinfunction "1_1") (pintype "passive"))
      (node (ref "J8") (pin "2") (pinfunction "S_2") (pintype "passive"))
      (node (ref "U7") (pin "10") (pinfunction "OA2_10") (pintype "output"))
      (node (ref "U7") (pin "5") (pinfunction "OA2_5") (pintype "output"))
    )
    (net (code "169") (name "/Y_MOT_1B") (class "Default")
      (node (ref "C86") (pin "1") (pinfunction "1_1") (pintype "passive"))
      (node (ref "J8") (pin "1") (pinfunction "S_1") (pintype "passive"))
      (node (ref "U7") (pin "2") (pinfunction "OA1_2") (pintype "output"))
      (node (ref "U7") (pin "7") (pinfunction "OA1_7") (pintype "output"))
    )
    (net (code "170") (name "/Y_MOT_2A") (class "Default")
      (node (ref "C108") (pin "1") (pinfunction "1_1") (pintype "passive"))
      (node (ref "J8") (pin "3") (pinfunction "S_3") (pintype "passive"))
      (node (ref "U7") (pin "26") (pinfunction "OB1_26") (pintype "output"))
      (node (ref "U7") (pin "31") (pinfunction "OB1_31") (pintype "output"))
    )
    (net (code "171") (name "/Y_MOT_2B") (class "Default")
      (node (ref "C114") (pin "1") (pinfunction "1_1") (pintype "passive"))
      (node (ref "J8") (pin "4") (pinfunction "S_4") (pintype "passive"))
      (node (ref "U7") (pin "23") (pinfunction "OB2_23") (pintype "output"))
      (node (ref "U7") (pin "28") (pinfunction "OB2_28") (pintype "output"))
    )
    (net (code "172") (name "/Y_STEP") (class "Default")
      (node (ref "TP2") (pin "1") (pinfunction "TP_1") (pintype "input"))
      (node (ref "U1") (pin "119") (pinfunction "PD7_119") (pintype "bidirectional"))
      (node (ref "U7") (pin "42") (pinfunction "STEP_42") (pintype "input"))
    )
    (net (code "173") (name "/Y_STOP") (class "Default")
      (node (ref "C41") (pin "1") (pinfunction "1_1") (pintype "passive"))
      (node (ref "D22") (pin "1") (pinfunction "A1_1") (pintype "passive"))
      (node (ref "R57") (pin "2") (pinfunction "2_2") (pintype "passive"))
      (node (ref "U1") (pin "93") (pinfunction "PA2_93") (pintype "bidirectional"))
    )
    (net (code "174") (name "/Y_STOP_CON") (class "Default")
      (node (ref "J32") (pin "1") (pinfunction "S_1") (pintype "passive"))
    )
    (net (code "175") (name "/Y_STOP_CONN") (class "Default")
      (node (ref "D9") (pin "C") (pinfunction "C_C") (pintype "passive"))
      (node (ref "R57") (pin "1") (pinfunction "1_1") (pintype "passive"))
    )
    (net (code "176") (name "/Z_DIR") (class "Default")
      (node (ref "TP1") (pin "2") (pinfunction "TP1_2") (pintype "input"))
      (node (ref "U1") (pin "88") (pinfunction "PD13_88") (pintype "bidirectional"))
      (node (ref "U6") (pin "41") (pinfunction "DIR_41") (pintype "input"))
    )
    (net (code "177") (name "/Z_EN") (class "Default")
      (node (ref "TP1") (pin "3") (pinfunction "TP2_3") (pintype "input"))
      (node (ref "U1") (pin "90") (pinfunction "PC10_90") (pintype "bidirectional"))
      (node (ref "U6") (pin "18") (pinfunction "~{CS}_18") (pintype "input"))
    )
    (net (code "178") (name "/Z_MOT_1A") (class "Default")
      (node (ref "C106") (pin "1") (pinfunction "1_1") (pintype "passive"))
      (node (ref "J36") (pin "2") (pinfunction "S_2") (pintype "passive"))
      (node (ref "J7") (pin "2") (pinfunction "S_2") (pintype "passive"))
      (node (ref "U6") (pin "10") (pinfunction "OA2_10") (pintype "output"))
      (node (ref "U6") (pin "5") (pinfunction "OA2_5") (pintype "output"))
    )
    (net (code "179") (name "/Z_MOT_1B") (class "Default")
      (node (ref "C87") (pin "1") (pinfunction "1_1") (pintype "passive"))
      (node (ref "J36") (pin "1") (pinfunction "S_1") (pintype "passive"))
      (node (ref "J7") (pin "1") (pinfunction "S_1") (pintype "passive"))
      (node (ref "U6") (pin "2") (pinfunction "OA1_2") (pintype "output"))
      (node (ref "U6") (pin "7") (pinfunction "OA1_7") (pintype "output"))
    )
    (net (code "180") (name "/Z_MOT_2A") (class "Default")
      (node (ref "C109") (pin "1") (pinfunction "1_1") (pintype "passive"))
      (node (ref "J36") (pin "3") (pinfunction "S_3") (pintype "passive"))
      (node (ref "J7") (pin "3") (pinfunction "S_3") (pintype "passive"))
      (node (ref "U6") (pin "26") (pinfunction "OB1_26") (pintype "output"))
      (node (ref "U6") (pin "31") (pinfunction "OB1_31") (pintype "output"))
    )
    (net (code "181") (name "/Z_MOT_2B") (class "Default")
      (node (ref "C115") (pin "1") (pinfunction "1_1") (pintype "passive"))
      (node (ref "J36") (pin "4") (pinfunction "S_4") (pintype "passive"))
      (node (ref "J7") (pin "4") (pinfunction "S_4") (pintype "passive"))
      (node (ref "U6") (pin "23") (pinfunction "OB2_23") (pintype "output"))
      (node (ref "U6") (pin "28") (pinfunction "OB2_28") (pintype "output"))
    )
    (net (code "182") (name "/Z_PROBE_IN") (class "Default")
      (node (ref "J28") (pin "1") (pinfunction "S_1") (pintype "passive"))
      (node (ref "R62") (pin "1") (pinfunction "1_1") (pintype "passive"))
    )
    (net (code "183") (name "/Z_PROBE_MCU") (class "Default")
      (node (ref "C90") (pin "1") (pinfunction "1_1") (pintype "passive"))
      (node (ref "D24") (pin "2") (pinfunction "A2_2") (pintype "passive"))
      (node (ref "R62") (pin "2") (pinfunction "2_2") (pintype "passive"))
      (node (ref "U1") (pin "38") (pinfunction "PC1/AFE1_AD4_38") (pintype "bidirectional"))
    )
    (net (code "184") (name "/Z_PROBE_MOD") (class "Default")
      (node (ref "J28") (pin "3") (pinfunction "S_3") (pintype "passive"))
      (node (ref "U1") (pin "39") (pinfunction "PC2_39") (pintype "bidirectional"))
      (node (ref "U10") (pin "5") (pinfunction "I_5") (pintype "input"))
    )
    (net (code "185") (name "/Z_PROBE_MOD_BUF") (class "Default")
      (node (ref "D4") (pin "A") (pinfunction "A_A") (pintype "passive"))
      (node (ref "U10") (pin "6") (pinfunction "O_6") (pintype "tri_state"))
    )
    (net (code "186") (name "/Z_STEP") (class "Default")
      (node (ref "TP1") (pin "1") (pinfunction "TP_1") (pintype "input"))
      (node (ref "U1") (pin "113") (pinfunction "PD8_113") (pintype "bidirectional"))
      (node (ref "U6") (pin "42") (pinfunction "STEP_42") (pintype "input"))
    )
    (net (code "187") (name "/Z_STOP") (class "Default")
      (node (ref "C42") (pin "1") (pinfunction "1_1") (pintype "passive"))
      (node (ref "D22") (pin "2") (pinfunction "A2_2") (pintype "passive"))
      (node (ref "R58") (pin "2") (pinfunction "2_2") (pintype "passive"))
      (node (ref "U1") (pin "108") (pinfunction "PD29_108") (pintype "bidirectional"))
    )
    (net (code "188") (name "/Z_STOP_CON") (class "Default")
      (node (ref "J19") (pin "1") (pinfunction "S_1") (pintype "passive"))
    )
    (net (code "189") (name "/Z_STOP_CONN") (class "Default")
      (node (ref "D10") (pin "C") (pinfunction "C_C") (pintype "passive"))
      (node (ref "R58") (pin "1") (pinfunction "1_1") (pintype "passive"))
    )
    (net (code "190") (name "GND") (class "Default")
      (node (ref "C1") (pin "2") (pinfunction "2_2") (pintype "passive"))
      (node (ref "C10") (pin "2") (pinfunction "2_2") (pintype "passive"))
      (node (ref "C100") (pin "2") (pinfunction "2_2") (pintype "passive"))
      (node (ref "C101") (pin "2") (pinfunction "2_2") (pintype "passive"))
      (node (ref "C102") (pin "-") (pinfunction "-_-") (pintype "passive"))
      (node (ref "C104") (pin "2") (pinfunction "2_2") (pintype "passive"))
      (node (ref "C105") (pin "2") (pinfunction "2_2") (pintype "passive"))
      (node (ref "C106") (pin "2") (pinfunction "2_2") (pintype "passive"))
      (node (ref "C107") (pin "2") (pinfunction "2_2") (pintype "passive"))
      (node (ref "C108") (pin "2") (pinfunction "2_2") (pintype "passive"))
      (node (ref "C109") (pin "2") (pinfunction "2_2") (pintype "passive"))
      (node (ref "C11") (pin "2") (pinfunction "2_2") (pintype "passive"))
      (node (ref "C110") (pin "2") (pinfunction "2_2") (pintype "passive"))
      (node (ref "C111") (pin "2") (pinfunction "2_2") (pintype "passive"))
      (node (ref "C113") (pin "2") (pinfunction "2_2") (pintype "passive"))
      (node (ref "C114") (pin "2") (pinfunction "2_2") (pintype "passive"))
      (node (ref "C115") (pin "2") (pinfunction "2_2") (pintype "passive"))
      (node (ref "C116") (pin "2") (pinfunction "2_2") (pintype "passive"))
      (node (ref "C117") (pin "2") (pinfunction "2_2") (pintype "passive"))
      (node (ref "C118") (pin "2") (pinfunction "2_2") (pintype "passive"))
      (node (ref "C119") (pin "2") (pinfunction "2_2") (pintype "passive"))
      (node (ref "C12") (pin "-") (pinfunction "-_-") (pintype "passive"))
      (node (ref "C120") (pin "2") (pinfunction "2_2") (pintype "passive"))
      (node (ref "C121") (pin "2") (pinfunction "2_2") (pintype "passive"))
      (node (ref "C122") (pin "2") (pinfunction "2_2") (pintype "passive"))
      (node (ref "C123") (pin "2") (pinfunction "2_2") (pintype "passive"))
      (node (ref "C124") (pin "2") (pinfunction "2_2") (pintype "passive"))
      (node (ref "C125") (pin "2") (pinfunction "2_2") (pintype "passive"))
      (node (ref "C13") (pin "2") (pinfunction "2_2") (pintype "passive"))
      (node (ref "C14") (pin "2") (pinfunction "2_2") (pintype "passive"))
      (node (ref "C15") (pin "2") (pinfunction "2_2") (pintype "passive"))
      (node (ref "C16") (pin "2") (pinfunction "2_2") (pintype "passive"))
      (node (ref "C17") (pin "2") (pinfunction "2_2") (pintype "passive"))
      (node (ref "C18") (pin "2") (pinfunction "2_2") (pintype "passive"))
      (node (ref "C19") (pin "2") (pinfunction "2_2") (pintype "passive"))
      (node (ref "C2") (pin "2") (pinfunction "2_2") (pintype "passive"))
      (node (ref "C20") (pin "2") (pinfunction "2_2") (pintype "passive"))
      (node (ref "C21") (pin "2") (pinfunction "2_2") (pintype "passive"))
      (node (ref "C22") (pin "-") (pinfunction "-_-") (pintype "passive"))
      (node (ref "C23") (pin "-") (pinfunction "-_-") (pintype "passive"))
      (node (ref "C26") (pin "2") (pinfunction "2_2") (pintype "passive"))
      (node (ref "C27") (pin "2") (pinfunction "2_2") (pintype "passive"))
      (node (ref "C28") (pin "2") (pinfunction "2_2") (pintype "passive"))
      (node (ref "C29") (pin "2") (pinfunction "2_2") (pintype "passive"))
      (node (ref "C3") (pin "-") (pinfunction "-_-") (pintype "passive"))
      (node (ref "C30") (pin "2") (pinfunction "2_2") (pintype "passive"))
      (node (ref "C31") (pin "2") (pinfunction "2_2") (pintype "passive"))
      (node (ref "C32") (pin "-") (pinfunction "-_-") (pintype "passive"))
      (node (ref "C33") (pin "-") (pinfunction "-_-") (pintype "passive"))
      (node (ref "C36") (pin "2") (pinfunction "2_2") (pintype "passive"))
      (node (ref "C37") (pin "2") (pinfunction "2_2") (pintype "passive"))
      (node (ref "C38") (pin "2") (pinfunction "2_2") (pintype "passive"))
      (node (ref "C39") (pin "2") (pinfunction "2_2") (pintype "passive"))
      (node (ref "C4") (pin "2") (pinfunction "2_2") (pintype "passive"))
      (node (ref "C40") (pin "2") (pinfunction "2_2") (pintype "passive"))
      (node (ref "C41") (pin "2") (pinfunction "2_2") (pintype "passive"))
      (node (ref "C42") (pin "2") (pinfunction "2_2") (pintype "passive"))
      (node (ref "C43") (pin "2") (pinfunction "2_2") (pintype "passive"))
      (node (ref "C44") (pin "2") (pinfunction "2_2") (pintype "passive"))
      (node (ref "C45") (pin "2") (pinfunction "2_2") (pintype "passive"))
      (node (ref "C46") (pin "2") (pinfunction "2_2") (pintype "passive"))
      (node (ref "C47") (pin "2") (pinfunction "2_2") (pintype "passive"))
      (node (ref "C48") (pin "2") (pinfunction "2_2") (pintype "passive"))
      (node (ref "C49") (pin "2") (pinfunction "2_2") (pintype "passive"))
      (node (ref "C5") (pin "2") (pinfunction "2_2") (pintype "passive"))
      (node (ref "C50") (pin "2") (pinfunction "2_2") (pintype "passive"))
      (node (ref "C51") (pin "2") (pinfunction "2_2") (pintype "passive"))
      (node (ref "C52") (pin "2") (pinfunction "2_2") (pintype "passive"))
      (node (ref "C53") (pin "2") (pinfunction "2_2") (pintype "passive"))
      (node (ref "C54") (pin "2") (pinfunction "2_2") (pintype "passive"))
      (node (ref "C55") (pin "2") (pinfunction "2_2") (pintype "passive"))
      (node (ref "C56") (pin "2") (pinfunction "2_2") (pintype "passive"))
      (node (ref "C57") (pin "2") (pinfunction "2_2") (pintype "passive"))
      (node (ref "C58") (pin "2") (pinfunction "2_2") (pintype "passive"))
      (node (ref "C59") (pin "2") (pinfunction "2_2") (pintype "passive"))
      (node (ref "C6") (pin "2") (pinfunction "2_2") (pintype "passive"))
      (node (ref "C60") (pin "2") (pinfunction "2_2") (pintype "passive"))
      (node (ref "C61") (pin "2") (pinfunction "2_2") (pintype "passive"))
      (node (ref "C62") (pin "2") (pinfunction "2_2") (pintype "passive"))
      (node (ref "C63") (pin "2") (pinfunction "2_2") (pintype "passive"))
      (node (ref "C64") (pin "2") (pinfunction "2_2") (pintype "passive"))
      (node (ref "C65") (pin "2") (pinfunction "2_2") (pintype "passive"))
      (node (ref "C66") (pin "2") (pinfunction "2_2") (pintype "passive"))
      (node (ref "C67") (pin "2") (pinfunction "2_2") (pintype "passive"))
      (node (ref "C68") (pin "2") (pinfunction "2_2") (pintype "passive"))
      (node (ref "C69") (pin "2") (pinfunction "2_2") (pintype "passive"))
      (node (ref "C7") (pin "2") (pinfunction "2_2") (pintype "passive"))
      (node (ref "C70") (pin "2") (pinfunction "2_2") (pintype "passive"))
      (node (ref "C71") (pin "2") (pinfunction "2_2") (pintype "passive"))
      (node (ref "C72") (pin "2") (pinfunction "2_2") (pintype "passive"))
      (node (ref "C73") (pin "2") (pinfunction "2_2") (pintype "passive"))
      (node (ref "C74") (pin "2") (pinfunction "2_2") (pintype "passive"))
      (node (ref "C75") (pin "2") (pinfunction "2_2") (pintype "passive"))
      (node (ref "C76") (pin "2") (pinfunction "2_2") (pintype "passive"))
      (node (ref "C77") (pin "2") (pinfunction "2_2") (pintype "passive"))
      (node (ref "C78") (pin "2") (pinfunction "2_2") (pintype "passive"))
      (node (ref "C79") (pin "2") (pinfunction "2_2") (pintype "passive"))
      (node (ref "C8") (pin "2") (pinfunction "2_2") (pintype "passive"))
      (node (ref "C80") (pin "2") (pinfunction "2_2") (pintype "passive"))
      (node (ref "C82") (pin "2") (pinfunction "2_2") (pintype "passive"))
      (node (ref "C83") (pin "2") (pinfunction "2_2") (pintype "passive"))
      (node (ref "C84") (pin "2") (pinfunction "2_2") (pintype "passive"))
      (node (ref "C85") (pin "2") (pinfunction "2_2") (pintype "passive"))
      (node (ref "C86") (pin "2") (pinfunction "2_2") (pintype "passive"))
      (node (ref "C87") (pin "2") (pinfunction "2_2") (pintype "passive"))
      (node (ref "C88") (pin "2") (pinfunction "2_2") (pintype "passive"))
      (node (ref "C89") (pin "2") (pinfunction "2_2") (pintype "passive"))
      (node (ref "C9") (pin "2") (pinfunction "2_2") (pintype "passive"))
      (node (ref "C90") (pin "2") (pinfunction "2_2") (pintype "passive"))
      (node (ref "C91") (pin "2") (pinfunction "2_2") (pintype "passive"))
      (node (ref "C94") (pin "2") (pinfunction "2_2") (pintype "passive"))
      (node (ref "C97") (pin "2") (pinfunction "2_2") (pintype "passive"))
      (node (ref "C98") (pin "2") (pinfunction "2_2") (pintype "passive"))
      (node (ref "C99") (pin "-") (pinfunction "-_-") (pintype "passive"))
      (node (ref "F1") (pin "1") (pinfunction "1_1") (pintype "bidirectional"))
      (node (ref "IC1") (pin "7") (pinfunction "GND_7") (pintype "power_in"))
      (node (ref "J1") (pin "2") (pinfunction "S_2") (pintype "passive"))
      (node (ref "J1") (pin "30") (pinfunction "S_30") (pintype "passive"))
      (node (ref "J1") (pin "42") (pinfunction "S_42") (pintype "passive"))
      (node (ref "J15") (pin "6") (pinfunction "GND_6") (pintype "bidirectional"))
      (node (ref "J15") (pin "G1") (pinfunction "SHIELD_G1") (pintype "bidirectional"))
      (node (ref "J15") (pin "G2") (pinfunction "SHIELD_G2") (pintype "bidirectional"))
      (node (ref "J15") (pin "G3") (pinfunction "SHIELD_G3") (pintype "bidirectional"))
      (node (ref "J15") (pin "G4") (pinfunction "SHIELD_G4") (pintype "bidirectional"))
      (node (ref "J16") (pin "10") (pinfunction "10_10") (pintype "passive"))
      (node (ref "J19") (pin "3") (pinfunction "S_3") (pintype "passive"))
      (node (ref "J20") (pin "3") (pinfunction "S_3") (pintype "passive"))
      (node (ref "J21") (pin "3") (pinfunction "GND_3") (pintype "bidirectional"))
      (node (ref "J21") (pin "5") (pinfunction "GND_5") (pintype "bidirectional"))
      (node (ref "J21") (pin "9") (pinfunction "GNDDTCT_9") (pintype "bidirectional"))
      (node (ref "J22") (pin "GND") (pinfunction "GND_GND") (pintype "power_in"))
      (node (ref "J23") (pin "2") (pinfunction "1_2") (pintype "passive"))
      (node (ref "J24") (pin "1") (pinfunction "S_1") (pintype "passive"))
      (node (ref "J28") (pin "2") (pinfunction "S_2") (pintype "passive"))
      (node (ref "J30") (pin "2") (pinfunction "S_2") (pintype "passive"))
      (node (ref "J31") (pin "1") (pinfunction "S_1") (pintype "passive"))
      (node (ref "J32") (pin "3") (pinfunction "S_3") (pintype "passive"))
      (node (ref "J33") (pin "3") (pinfunction "S_3") (pintype "passive"))
      (node (ref "J34") (pin "3") (pinfunction "S_3") (pintype "passive"))
      (node (ref "J35") (pin "3") (pinfunction "S_3") (pintype "passive"))
      (node (ref "J37") (pin "2") (pinfunction "S_2") (pintype "passive"))
      (node (ref "J39") (pin "1") (pinfunction "1_1") (pintype "passive"))
      (node (ref "JP9") (pin "1") (pinfunction "1_1") (pintype "passive"))
      (node (ref "P1") (pin "2") (pinfunction "S_2") (pintype "passive"))
      (node (ref "P2") (pin "2") (pinfunction "S_2") (pintype "passive"))
      (node (ref "R1") (pin "2") (pinfunction "2_2") (pintype "passive"))
      (node (ref "R104") (pin "1") (pinfunction "1_1") (pintype "passive"))
      (node (ref "R16") (pin "1") (pinfunction "1_1") (pintype "passive"))
      (node (ref "R18") (pin "1") (pinfunction "1_1") (pintype "passive"))
      (node (ref "R24") (pin "1") (pinfunction "1_1") (pintype "passive"))
      (node (ref "R31") (pin "1") (pinfunction "1_1") (pintype "passive"))
      (node (ref "R32") (pin "1") (pinfunction "1_1") (pintype "passive"))
      (node (ref "R33") (pin "1") (pinfunction "1_1") (pintype "passive"))
      (node (ref "R34") (pin "1") (pinfunction "1_1") (pintype "passive"))
      (node (ref "R35") (pin "1") (pinfunction "1_1") (pintype "passive"))
      (node (ref "R4") (pin "1") (pinfunction "1_1") (pintype "passive"))
      (node (ref "R44") (pin "1") (pinfunction "1_1") (pintype "passive"))
      (node (ref "R45") (pin "1") (pinfunction "1_1") (pintype "passive"))
      (node (ref "R46") (pin "1") (pinfunction "1_1") (pintype "passive"))
      (node (ref "R47") (pin "1") (pinfunction "1_1") (pintype "passive"))
      (node (ref "R54") (pin "1") (pinfunction "1_1") (pintype "passive"))
      (node (ref "R55") (pin "2") (pinfunction "2_2") (pintype "passive"))
      (node (ref "R60") (pin "2") (pinfunction "2_2") (pintype "passive"))
      (node (ref "R61") (pin "2") (pinfunction "2_2") (pintype "passive"))
      (node (ref "R81") (pin "1") (pinfunction "1_1") (pintype "passive"))
      (node (ref "R85") (pin "1") (pinfunction "1_1") (pintype "passive"))
      (node (ref "R86") (pin "1") (pinfunction "1_1") (pintype "passive"))
      (node (ref "R88") (pin "1") (pinfunction "1_1") (pintype "passive"))
      (node (ref "R91") (pin "1") (pinfunction "1_1") (pintype "passive"))
      (node (ref "R93") (pin "1") (pinfunction "1_1") (pintype "passive"))
      (node (ref "R94") (pin "1") (pinfunction "1_1") (pintype "passive"))
      (node (ref "S1") (pin "3") (pinfunction "P_3") (pintype "passive"))
      (node (ref "S1") (pin "4") (pinfunction "P1_4") (pintype "passive"))
      (node (ref "TR1") (pin "2") (pinfunction "S_2") (pintype "bidirectional"))
      (node (ref "TR2") (pin "3") (pinfunction "D_3") (pintype "passive"))
      (node (ref "TR4") (pin "3") (pinfunction "D_3") (pintype "passive"))
      (node (ref "TR5") (pin "2") (pinfunction "S_2") (pintype "bidirectional"))
      (node (ref "TR7") (pin "2") (pinfunction "S_2") (pintype "bidirectional"))
      (node (ref "TR8") (pin "3") (pinfunction "D_3") (pintype "passive"))
      (node (ref "TR9") (pin "2") (pinfunction "S_2") (pintype "bidirectional"))
      (node (ref "U1") (pin "104") (pinfunction "JTAGSEL_104") (pintype "input"))
      (node (ref "U1") (pin "115") (pinfunction "GND5_115") (pintype "power_in"))
      (node (ref "U1") (pin "135") (pinfunction "GND6_135") (pintype "power_in"))
      (node (ref "U1") (pin "138") (pinfunction "GND7_138") (pintype "power_in"))
      (node (ref "U1") (pin "44") (pinfunction "GND2_44") (pintype "power_in"))
      (node (ref "U1") (pin "61") (pinfunction "GND3_61") (pintype "power_in"))
      (node (ref "U1") (pin "8") (pinfunction "GND1_8") (pintype "power_in"))
      (node (ref "U1") (pin "85") (pinfunction "TEST_85") (pintype "input"))
      (node (ref "U1") (pin "95") (pinfunction "GND4_95") (pintype "power_in"))
      (node (ref "U10") (pin "1") (pinfunction "OE_1") (pintype "input"))
      (node (ref "U10") (pin "10") (pinfunction "OE_10") (pintype "input"))
      (node (ref "U10") (pin "12") (pinfunction "I_12") (pintype "input"))
      (node (ref "U10") (pin "13") (pinfunction "OE_13") (pintype "input"))
      (node (ref "U10") (pin "4") (pinfunction "OE_4") (pintype "input"))
      (node (ref "U10") (pin "7") (pinfunction "GND_7") (pintype "power_in"))
      (node (ref "U11") (pin "7") (pinfunction "GND_7") (pintype "power_in"))
      (node (ref "U13") (pin "7") (pinfunction "GND_7") (pintype "power_in"))
      (node (ref "U2") (pin "2") (pinfunction "GND_2") (pintype "passive"))
      (node (ref "U2") (pin "4") (pinfunction "GND_4") (pintype "passive"))
      (node (ref "U3") (pin "13") (pinfunction "NC13_13") (pintype "bidirectional"))
      (node (ref "U3") (pin "14") (pinfunction "NC14_14") (pintype "bidirectional"))
      (node (ref "U3") (pin "15") (pinfunction "NC15_15") (pintype "bidirectional"))
      (node (ref "U3") (pin "16") (pinfunction "NC16_16") (pintype "bidirectional"))
      (node (ref "U3") (pin "2") (pinfunction "NC2_2") (pintype "bidirectional"))
      (node (ref "U3") (pin "6") (pinfunction "GND_6") (pintype "bidirectional"))
      (node (ref "U3") (pin "7") (pinfunction "NC7_7") (pintype "bidirectional"))
      (node (ref "U3") (pin "9") (pinfunction "SGND_9") (pintype "bidirectional"))
      (node (ref "U3") (pin "EXP") (pinfunction "PAD_EXP") (pintype "bidirectional"))
      (node (ref "U4") (pin "9") (pinfunction "GND_9") (pintype "power_in"))
      (node (ref "U5") (pin "17") (pinfunction "GND_17") (pintype "input"))
      (node (ref "U5") (pin "21") (pinfunction "CLK_21") (pintype "input"))
      (node (ref "U5") (pin "39") (pinfunction "GND_39") (pintype "input"))
      (node (ref "U5") (pin "43") (pinfunction "TST_MODE_43") (pintype "input"))
      (node (ref "U5") (pin "44") (pinfunction "GND_44") (pintype "input"))
      (node (ref "U6") (pin "17") (pinfunction "GND_17") (pintype "input"))
      (node (ref "U6") (pin "21") (pinfunction "CLK_21") (pintype "input"))
      (node (ref "U6") (pin "39") (pinfunction "GND_39") (pintype "input"))
      (node (ref "U6") (pin "43") (pinfunction "TST_MODE_43") (pintype "input"))
      (node (ref "U6") (pin "44") (pinfunction "GND_44") (pintype "input"))
      (node (ref "U7") (pin "17") (pinfunction "GND_17") (pintype "input"))
      (node (ref "U7") (pin "21") (pinfunction "CLK_21") (pintype "input"))
      (node (ref "U7") (pin "39") (pinfunction "GND_39") (pintype "input"))
      (node (ref "U7") (pin "43") (pinfunction "TST_MODE_43") (pintype "input"))
      (node (ref "U7") (pin "44") (pinfunction "GND_44") (pintype "input"))
      (node (ref "U8") (pin "17") (pinfunction "GND_17") (pintype "input"))
      (node (ref "U8") (pin "21") (pinfunction "CLK_21") (pintype "input"))
      (node (ref "U8") (pin "39") (pinfunction "GND_39") (pintype "input"))
      (node (ref "U8") (pin "43") (pinfunction "TST_MODE_43") (pintype "input"))
      (node (ref "U8") (pin "44") (pinfunction "GND_44") (pintype "input"))
      (node (ref "U9") (pin "17") (pinfunction "GND_17") (pintype "input"))
      (node (ref "U9") (pin "21") (pinfunction "CLK_21") (pintype "input"))
      (node (ref "U9") (pin "39") (pinfunction "GND_39") (pintype "input"))
      (node (ref "U9") (pin "43") (pinfunction "TST_MODE_43") (pintype "input"))
      (node (ref "U9") (pin "44") (pinfunction "GND_44") (pintype "input"))
      (node (ref "X2") (pin "2") (pinfunction "GND_2") (pintype "passive"))
      (node (ref "X2") (pin "4") (pinfunction "GND_4") (pintype "passive"))
    )
    (net (code "191") (name "Net-(C1-Pad1)") (class "Default")
      (node (ref "C1") (pin "1") (pinfunction "1_1") (pintype "passive"))
      (node (ref "C3") (pin "+") (pinfunction "+_+") (pintype "passive"))
      (node (ref "D1") (pin "C") (pinfunction "C_C") (pintype "passive"))
      (node (ref "L2") (pin "1") (pinfunction "1_1") (pintype "passive"))
      (node (ref "R15") (pin "2") (pinfunction "2_2") (pintype "passive"))
    )
    (net (code "192") (name "Net-(C12-Pad+)") (class "Default")
      (node (ref "C12") (pin "+") (pinfunction "+_+") (pintype "passive"))
      (node (ref "C125") (pin "1") (pinfunction "1_1") (pintype "passive"))
      (node (ref "C6") (pin "1") (pinfunction "1_1") (pintype "passive"))
      (node (ref "L2") (pin "2") (pinfunction "2_2") (pintype "passive"))
      (node (ref "L4") (pin "2") (pinfunction "2_2") (pintype "passive"))
      (node (ref "R84") (pin "2") (pinfunction "2_2") (pintype "passive"))
      (node (ref "R92") (pin "1") (pinfunction "1_1") (pintype "passive"))
    )
    (net (code "193") (name "Net-(C13-Pad1)") (class "Default")
      (node (ref "C13") (pin "1") (pinfunction "1_1") (pintype "passive"))
      (node (ref "J22") (pin "MT1") (pinfunction "SHIELD_MT1") (pintype "bidirectional"))
      (node (ref "J22") (pin "MT2") (pinfunction "SHIELD_MT2") (pintype "bidirectional"))
      (node (ref "J22") (pin "P$1") (pinfunction "SHIELD_P$1") (pintype "bidirectional"))
      (node (ref "J22") (pin "P$2") (pinfunction "SHIELD_P$2") (pintype "bidirectional"))
    )
    (net (code "194") (name "Net-(C66-Pad1)") (class "Default")
      (node (ref "C66") (pin "1") (pinfunction "1_1") (pintype "passive"))
      (node (ref "R13") (pin "1") (pinfunction "1_1") (pintype "passive"))
    )
    (net (code "195") (name "Net-(C81-Pad1)") (class "Default")
      (node (ref "C81") (pin "1") (pinfunction "1_1") (pintype "passive"))
      (node (ref "C97") (pin "1") (pinfunction "1_1") (pintype "passive"))
      (node (ref "C98") (pin "1") (pinfunction "1_1") (pintype "passive"))
      (node (ref "L1") (pin "2") (pinfunction "2_2") (pintype "passive"))
      (node (ref "L3") (pin "2") (pinfunction "2_2") (pintype "passive"))
      (node (ref "R87") (pin "2") (pinfunction "2_2") (pintype "passive"))
    )
    (net (code "196") (name "Net-(D3-PadC)") (class "Default")
      (node (ref "D3") (pin "C") (pinfunction "C_C") (pintype "passive"))
      (node (ref "R1") (pin "1") (pinfunction "1_1") (pintype "passive"))
    )
    (net (code "197") (name "Net-(D4-PadC)") (class "Default")
      (node (ref "D4") (pin "C") (pinfunction "C_C") (pintype "passive"))
      (node (ref "R104") (pin "2") (pinfunction "2_2") (pintype "passive"))
    )
    (net (code "198") (name "Net-(D5-PadC)") (class "Default")
      (node (ref "D5") (pin "C") (pinfunction "C_C") (pintype "passive"))
      (node (ref "D6") (pin "A") (pinfunction "A_A") (pintype "passive"))
      (node (ref "R65") (pin "1") (pinfunction "1_1") (pintype "passive"))
    )
    (net (code "199") (name "Net-(D7-PadA)") (class "Default")
      (node (ref "D7") (pin "A") (pinfunction "A_A") (pintype "passive"))
      (node (ref "R67") (pin "1") (pinfunction "1_1") (pintype "passive"))
    )
    (net (code "200") (name "Net-(D9-PadA)") (class "Default")
      (node (ref "D9") (pin "A") (pinfunction "A_A") (pintype "passive"))
      (node (ref "R69") (pin "1") (pinfunction "1_1") (pintype "passive"))
    )
    (net (code "201") (name "Net-(D10-PadA)") (class "Default")
      (node (ref "D10") (pin "A") (pinfunction "A_A") (pintype "passive"))
      (node (ref "R70") (pin "1") (pinfunction "1_1") (pintype "passive"))
    )
    (net (code "202") (name "Net-(D11-PadA)") (class "Default")
      (node (ref "D11") (pin "A") (pinfunction "A_A") (pintype "passive"))
      (node (ref "R71") (pin "1") (pinfunction "1_1") (pintype "passive"))
    )
    (net (code "203") (name "Net-(D12-PadA)") (class "Default")
      (node (ref "D12") (pin "A") (pinfunction "A_A") (pintype "passive"))
      (node (ref "R72") (pin "1") (pinfunction "1_1") (pintype "passive"))
    )
    (net (code "204") (name "Net-(D14-PadC)") (class "Default")
      (node (ref "D14") (pin "C") (pinfunction "C_C") (pintype "passive"))
      (node (ref "JP10") (pin "2") (pinfunction "2_2") (pintype "passive"))
    )
    (net (code "205") (name "Net-(D15-PadC)") (class "Default")
      (node (ref "D15") (pin "C") (pinfunction "C_C") (pintype "passive"))
      (node (ref "R55") (pin "1") (pinfunction "1_1") (pintype "passive"))
    )
    (net (code "206") (name "Net-(D16-PadC)") (class "Default")
      (node (ref "D16") (pin "C") (pinfunction "C_C") (pintype "passive"))
      (node (ref "R60") (pin "1") (pinfunction "1_1") (pintype "passive"))
    )
    (net (code "207") (name "Net-(D17-PadC)") (class "Default")
      (node (ref "D17") (pin "C") (pinfunction "C_C") (pintype "passive"))
      (node (ref "R61") (pin "1") (pinfunction "1_1") (pintype "passive"))
    )
    (net (code "208") (name "Net-(D19-PadA)") (class "Default")
      (node (ref "D19") (pin "A") (pinfunction "A_A") (pintype "passive"))
      (node (ref "R96") (pin "1") (pinfunction "1_1") (pintype "passive"))
    )
    (net (code "209") (name "Net-(D20-PadA)") (class "Default")
      (node (ref "D20") (pin "A") (pinfunction "A_A") (pintype "passive"))
      (node (ref "R98") (pin "1") (pinfunction "1_1") (pintype "passive"))
    )
    (net (code "210") (name "Net-(F2-Pad2)") (class "Default")
      (node (ref "F2") (pin "2") (pinfunction "2_2") (pintype "passive"))
      (node (ref "J3") (pin "3") (pinfunction "3_3") (pintype "passive"))
    )
    (net (code "211") (name "Net-(IC1A-Q)") (class "Default")
      (node (ref "IC1") (pin "5") (pinfunction "Q_5") (pintype "output"))
      (node (ref "R82") (pin "2") (pinfunction "2_2") (pintype "passive"))
      (node (ref "U4") (pin "14") (pinfunction "GPIO4_14") (pintype "bidirectional"))
    )
    (net (code "212") (name "Net-(J15-CARD_DETECT)") (class "Default")
      (node (ref "J15") (pin "9") (pinfunction "CARD_DETECT_9") (pintype "bidirectional"))
      (node (ref "R64") (pin "1") (pinfunction "1_1") (pintype "passive"))
      (node (ref "R79") (pin "2") (pinfunction "2_2") (pintype "passive"))
    )
    (net (code "213") (name "Net-(J15-CLK)") (class "Default")
      (node (ref "J15") (pin "5") (pinfunction "CLK_5") (pintype "bidirectional"))
      (node (ref "R68") (pin "2") (pinfunction "2_2") (pintype "passive"))
    )
    (net (code "214") (name "Net-(J15-CMD)") (class "Default")
      (node (ref "J15") (pin "3") (pinfunction "CMD_3") (pintype "bidirectional"))
      (node (ref "R48") (pin "2") (pinfunction "2_2") (pintype "passive"))
      (node (ref "R63") (pin "1") (pinfunction "1_1") (pintype "passive"))
    )
    (net (code "215") (name "Net-(J15-DAT0{slash}D0)") (class "Default")
      (node (ref "J15") (pin "7") (pinfunction "DAT0/D0_7") (pintype "bidirectional"))
      (node (ref "R75") (pin "1") (pinfunction "1_1") (pintype "passive"))
      (node (ref "R77") (pin "2") (pinfunction "2_2") (pintype "passive"))
    )
    (net (code "216") (name "Net-(J15-DAT1)") (class "Default")
      (node (ref "J15") (pin "8") (pinfunction "DAT1_8") (pintype "bidirectional"))
      (node (ref "R76") (pin "1") (pinfunction "1_1") (pintype "passive"))
      (node (ref "R78") (pin "2") (pinfunction "2_2") (pintype "passive"))
    )
    (net (code "217") (name "Net-(J15-DAT2)") (class "Default")
      (node (ref "J15") (pin "1") (pinfunction "DAT2_1") (pintype "bidirectional"))
      (node (ref "R22") (pin "2") (pinfunction "2_2") (pintype "passive"))
      (node (ref "R73") (pin "1") (pinfunction "1_1") (pintype "passive"))
    )
    (net (code "218") (name "Net-(J15-DAT3)") (class "Default")
      (node (ref "J15") (pin "2") (pinfunction "DAT3_2") (pintype "bidirectional"))
      (node (ref "R25") (pin "2") (pinfunction "2_2") (pintype "passive"))
      (node (ref "R74") (pin "1") (pinfunction "1_1") (pintype "passive"))
    )
    (net (code "219") (name "Net-(J22-PadD+)") (class "Default")
      (node (ref "J22") (pin "D+") (pinfunction "D+_D+") (pintype "bidirectional"))
      (node (ref "R2") (pin "2") (pinfunction "2_2") (pintype "passive"))
    )
    (net (code "220") (name "Net-(J22-PadD-)") (class "Default")
      (node (ref "J22") (pin "D-") (pinfunction "D-_D-") (pintype "bidirectional"))
      (node (ref "R3") (pin "2") (pinfunction "2_2") (pintype "passive"))
    )
    (net (code "221") (name "Net-(S1-S)") (class "Default")
      (node (ref "C2") (pin "1") (pinfunction "1_1") (pintype "passive"))
      (node (ref "D25") (pin "C") (pinfunction "C_C") (pintype "passive"))
      (node (ref "R107") (pin "2") (pinfunction "2_2") (pintype "passive"))
      (node (ref "S1") (pin "1") (pinfunction "S_1") (pintype "passive"))
      (node (ref "S1") (pin "2") (pinfunction "S1_2") (pintype "passive"))
    )
    (net (code "222") (name "Net-(TR1-G)") (class "Default")
      (node (ref "R66") (pin "2") (pinfunction "2_2") (pintype "passive"))
      (node (ref "TR1") (pin "1") (pinfunction "G_1") (pintype "bidirectional"))
    )
    (net (code "223") (name "Net-(TR2-G)") (class "Default")
      (node (ref "R20") (pin "2") (pinfunction "2_2") (pintype "passive"))
      (node (ref "TR2") (pin "1") (pinfunction "G_1") (pintype "passive"))
    )
    (net (code "224") (name "Net-(TR4-G)") (class "Default")
      (node (ref "R23") (pin "2") (pinfunction "2_2") (pintype "passive"))
      (node (ref "TR4") (pin "1") (pinfunction "G_1") (pintype "passive"))
    )
    (net (code "225") (name "Net-(TR5-G)") (class "Default")
      (node (ref "R42") (pin "2") (pinfunction "2_2") (pintype "passive"))
      (node (ref "TR5") (pin "1") (pinfunction "G_1") (pintype "bidirectional"))
    )
    (net (code "226") (name "Net-(TR7-G)") (class "Default")
      (node (ref "R14") (pin "2") (pinfunction "2_2") (pintype "passive"))
      (node (ref "TR7") (pin "1") (pinfunction "G_1") (pintype "bidirectional"))
    )
    (net (code "227") (name "Net-(TR8-G)") (class "Default")
      (node (ref "R97") (pin "2") (pinfunction "2_2") (pintype "passive"))
      (node (ref "TR8") (pin "1") (pinfunction "G_1") (pintype "passive"))
    )
    (net (code "228") (name "Net-(TR9-G)") (class "Default")
      (node (ref "R43") (pin "2") (pinfunction "2_2") (pintype "passive"))
      (node (ref "TR9") (pin "1") (pinfunction "G_1") (pintype "bidirectional"))
    )
    (net (code "229") (name "Net-(U1-PA18{slash}PGMD6{slash}AFE0_AD1)") (class "Default")
      (node (ref "C84") (pin "1") (pinfunction "1_1") (pintype "passive"))
      (node (ref "R50") (pin "2") (pinfunction "2_2") (pintype "passive"))
      (node (ref "U1") (pin "24") (pinfunction "PA18/PGMD6/AFE0_AD1_24") (pintype "bidirectional"))
    )
    (net (code "230") (name "Net-(U1-PB8{slash}XIN)") (class "Default")
      (node (ref "C44") (pin "1") (pinfunction "1_1") (pintype "passive"))
      (node (ref "U1") (pin "141") (pinfunction "PB8/XIN_141") (pintype "bidirectional"))
      (node (ref "X2") (pin "3") (pinfunction "C2_3") (pintype "passive"))
    )
    (net (code "231") (name "Net-(U1-PB9{slash}XOUT)") (class "Default")
      (node (ref "C45") (pin "1") (pinfunction "1_1") (pintype "passive"))
      (node (ref "U1") (pin "142") (pinfunction "PB9/XOUT_142") (pintype "bidirectional"))
      (node (ref "X2") (pin "1") (pinfunction "C1_1") (pintype "passive"))
    )
    (net (code "232") (name "Net-(U1-PC12{slash}{slash}AFE0_AD8)") (class "Default")
      (node (ref "C53") (pin "1") (pinfunction "1_1") (pintype "passive"))
      (node (ref "R10") (pin "2") (pinfunction "2_2") (pintype "passive"))
      (node (ref "U1") (pin "17") (pinfunction "PC12//AFE0_AD8_17") (pintype "bidirectional"))
    )
    (net (code "233") (name "Net-(U1-PC13{slash}AFE0_AD6)") (class "Default")
      (node (ref "C19") (pin "1") (pinfunction "1_1") (pintype "passive"))
      (node (ref "R12") (pin "2") (pinfunction "2_2") (pintype "passive"))
      (node (ref "U1") (pin "19") (pinfunction "PC13/AFE0_AD6_19") (pintype "bidirectional"))
    )
    (net (code "234") (name "Net-(U1-PC15{slash}AFE0_AD7)") (class "Default")
      (node (ref "C18") (pin "1") (pinfunction "1_1") (pintype "passive"))
      (node (ref "R11") (pin "2") (pinfunction "2_2") (pintype "passive"))
      (node (ref "U1") (pin "18") (pinfunction "PC15/AFE0_AD7_18") (pintype "bidirectional"))
    )
    (net (code "235") (name "Net-(U1-PC27{slash}AFE0_AD13)") (class "Default")
      (node (ref "C65") (pin "1") (pinfunction "1_1") (pintype "passive"))
      (node (ref "R6") (pin "2") (pinfunction "2_2") (pintype "passive"))
      (node (ref "U1") (pin "12") (pinfunction "PC27/AFE0_AD13_12") (pintype "bidirectional"))
    )
    (net (code "236") (name "Net-(U1-PC29{slash}AFE0_AD9)") (class "Default")
      (node (ref "C59") (pin "1") (pinfunction "1_1") (pintype "passive"))
      (node (ref "R9") (pin "2") (pinfunction "2_2") (pintype "passive"))
      (node (ref "U1") (pin "16") (pinfunction "PC29/AFE0_AD9_16") (pintype "bidirectional"))
    )
    (net (code "237") (name "Net-(U1-PC30{slash}AFE0_AD10)") (class "Default")
      (node (ref "C60") (pin "1") (pinfunction "1_1") (pintype "passive"))
      (node (ref "R8") (pin "2") (pinfunction "2_2") (pintype "passive"))
      (node (ref "U1") (pin "15") (pinfunction "PC30/AFE0_AD10_15") (pintype "bidirectional"))
    )
    (net (code "238") (name "Net-(U1-PC31{slash}AFE0_AD11)") (class "Default")
      (node (ref "C63") (pin "1") (pinfunction "1_1") (pintype "passive"))
      (node (ref "R7") (pin "2") (pinfunction "2_2") (pintype "passive"))
      (node (ref "U1") (pin "14") (pinfunction "PC31/AFE0_AD11_14") (pintype "bidirectional"))
    )
    (net (code "239") (name "Net-(U1-VDDCORE1)") (class "Default")
      (node (ref "C10") (pin "1") (pinfunction "1_1") (pintype "passive"))
      (node (ref "C52") (pin "1") (pinfunction "1_1") (pintype "passive"))
      (node (ref "C61") (pin "1") (pinfunction "1_1") (pintype "passive"))
      (node (ref "C62") (pin "1") (pinfunction "1_1") (pintype "passive"))
      (node (ref "C68") (pin "1") (pinfunction "1_1") (pintype "passive"))
      (node (ref "C69") (pin "1") (pinfunction "1_1") (pintype "passive"))
      (node (ref "C70") (pin "1") (pinfunction "1_1") (pintype "passive"))
      (node (ref "C71") (pin "1") (pinfunction "1_1") (pintype "passive"))
      (node (ref "C72") (pin "1") (pinfunction "1_1") (pintype "passive"))
      (node (ref "L6") (pin "1") (pinfunction "1_1") (pintype "passive"))
      (node (ref "U1") (pin "107") (pinfunction "VDDCORE5_107") (pintype "input"))
      (node (ref "U1") (pin "123") (pinfunction "VDDCORE6_123") (pintype "input"))
      (node (ref "U1") (pin "29") (pinfunction "VDDCORE1_29") (pintype "input"))
      (node (ref "U1") (pin "3") (pinfunction "VDDOUT_3") (pintype "output"))
      (node (ref "U1") (pin "33") (pinfunction "VDDCORE2_33") (pintype "input"))
      (node (ref "U1") (pin "50") (pinfunction "VDDCORE3_50") (pintype "input"))
      (node (ref "U1") (pin "81") (pinfunction "VDDCORE4_81") (pintype "input"))
    )
    (net (code "240") (name "Net-(U1-VDDPLL)") (class "Default")
      (node (ref "C67") (pin "1") (pinfunction "1_1") (pintype "passive"))
      (node (ref "L6") (pin "2") (pinfunction "2_2") (pintype "passive"))
      (node (ref "R13") (pin "2") (pinfunction "2_2") (pintype "passive"))
      (node (ref "U1") (pin "139") (pinfunction "VDDPLL_139") (pintype "input"))
    )
    (net (code "241") (name "Net-(U3-BOOT)") (class "Default")
      (node (ref "C96") (pin "1") (pinfunction "1_1") (pintype "passive"))
      (node (ref "U3") (pin "11") (pinfunction "BOOT_11") (pintype "bidirectional"))
    )
    (net (code "242") (name "Net-(U3-DIS)") (class "Default")
      (node (ref "JP9") (pin "2") (pinfunction "2_2") (pintype "passive"))
      (node (ref "U3") (pin "10") (pinfunction "DIS_10") (pintype "bidirectional"))
    )
    (net (code "243") (name "Net-(U3-FB)") (class "Default")
      (node (ref "C81") (pin "2") (pinfunction "2_2") (pintype "passive"))
      (node (ref "R87") (pin "1") (pinfunction "1_1") (pintype "passive"))
      (node (ref "R88") (pin "2") (pinfunction "2_2") (pintype "passive"))
      (node (ref "U3") (pin "5") (pinfunction "FB_5") (pintype "bidirectional"))
    )
    (net (code "244") (name "Net-(U3-ISEN)") (class "Default")
      (node (ref "D2") (pin "A") (pinfunction "A_A") (pintype "passive"))
      (node (ref "R85") (pin "2") (pinfunction "2_2") (pintype "passive"))
      (node (ref "R86") (pin "2") (pinfunction "2_2") (pintype "passive"))
      (node (ref "U3") (pin "8") (pinfunction "ISEN_8") (pintype "bidirectional"))
    )
    (net (code "245") (name "Net-(U3-LX)") (class "Default")
      (node (ref "C96") (pin "2") (pinfunction "2_2") (pintype "passive"))
      (node (ref "D2") (pin "C") (pinfunction "C_C") (pintype "passive"))
      (node (ref "L1") (pin "1") (pinfunction "1_1") (pintype "passive"))
      (node (ref "U3") (pin "12") (pinfunction "LX_12") (pintype "bidirectional"))
    )
    (net (code "246") (name "Net-(U3-SS)") (class "Default")
      (node (ref "C5") (pin "1") (pinfunction "1_1") (pintype "passive"))
      (node (ref "U3") (pin "4") (pinfunction "SS_4") (pintype "bidirectional"))
    )
    (net (code "247") (name "Net-(U3-TON)") (class "Default")
      (node (ref "R84") (pin "1") (pinfunction "1_1") (pintype "passive"))
      (node (ref "U3") (pin "3") (pinfunction "TON_3") (pintype "bidirectional"))
    )
    (net (code "248") (name "Net-(U3-VIN)") (class "Default")
      (node (ref "L4") (pin "1") (pinfunction "1_1") (pintype "passive"))
      (node (ref "R92") (pin "2") (pinfunction "2_2") (pintype "passive"))
      (node (ref "U3") (pin "1") (pinfunction "VIN_1") (pintype "bidirectional"))
    )
    (net (code "249") (name "Net-(U4-RESET)") (class "Default")
      (node (ref "R4") (pin "2") (pinfunction "2_2") (pintype "passive"))
      (node (ref "R5") (pin "1") (pinfunction "1_1") (pintype "passive"))
      (node (ref "U4") (pin "1") (pinfunction "RESET_1") (pintype "input"))
    )
    (net (code "250") (name "Net-(U5-5VOUT)") (class "Default")
      (node (ref "C26") (pin "1") (pinfunction "1_1") (pintype "passive"))
      (node (ref "U5") (pin "13") (pinfunction "5VOUT_13") (pintype "output"))
    )
    (net (code "251") (name "Net-(U5-BRA)") (class "Default")
      (node (ref "R26") (pin "1") (pinfunction "1_1") (pintype "passive"))
      (node (ref "R34") (pin "2") (pinfunction "2_2") (pintype "passive"))
      (node (ref "U5") (pin "9") (pinfunction "BRA_9") (pintype "input"))
    )
    (net (code "252") (name "Net-(U5-BRB)") (class "Default")
      (node (ref "R27") (pin "1") (pinfunction "1_1") (pintype "passive"))
      (node (ref "R32") (pin "2") (pinfunction "2_2") (pintype "passive"))
      (node (ref "U5") (pin "25") (pinfunction "BRB_25") (pintype "input"))
    )
    (net (code "253") (name "Net-(U5-SRA)") (class "Default")
      (node (ref "C14") (pin "1") (pinfunction "1_1") (pintype "passive"))
      (node (ref "R26") (pin "2") (pinfunction "2_2") (pintype "passive"))
      (node (ref "U5") (pin "12") (pinfunction "SRA_12") (pintype "input"))
    )
    (net (code "254") (name "Net-(U5-SRB)") (class "Default")
      (node (ref "C28") (pin "1") (pinfunction "1_1") (pintype "passive"))
      (node (ref "R27") (pin "2") (pinfunction "2_2") (pintype "passive"))
      (node (ref "U5") (pin "22") (pinfunction "SRB_22") (pintype "input"))
    )
    (net (code "255") (name "Net-(U5-VHS)") (class "Default")
      (node (ref "C24") (pin "2") (pinfunction "2_2") (pintype "passive"))
      (node (ref "U5") (pin "35") (pinfunction "VHS_35") (pintype "input"))
    )
    (net (code "256") (name "Net-(U6-5VOUT)") (class "Default")
      (node (ref "C27") (pin "1") (pinfunction "1_1") (pintype "passive"))
      (node (ref "U6") (pin "13") (pinfunction "5VOUT_13") (pintype "output"))
    )
    (net (code "257") (name "Net-(U6-BRA)") (class "Default")
      (node (ref "R28") (pin "1") (pinfunction "1_1") (pintype "passive"))
      (node (ref "R35") (pin "2") (pinfunction "2_2") (pintype "passive"))
      (node (ref "U6") (pin "9") (pinfunction "BRA_9") (pintype "input"))
    )
    (net (code "258") (name "Net-(U6-BRB)") (class "Default")
      (node (ref "R29") (pin "1") (pinfunction "1_1") (pintype "passive"))
      (node (ref "R33") (pin "2") (pinfunction "2_2") (pintype "passive"))
      (node (ref "U6") (pin "25") (pinfunction "BRB_25") (pintype "input"))
    )
    (net (code "259") (name "Net-(U6-SRA)") (class "Default")
      (node (ref "C15") (pin "1") (pinfunction "1_1") (pintype "passive"))
      (node (ref "R28") (pin "2") (pinfunction "2_2") (pintype "passive"))
      (node (ref "U6") (pin "12") (pinfunction "SRA_12") (pintype "input"))
    )
    (net (code "260") (name "Net-(U6-SRB)") (class "Default")
      (node (ref "C29") (pin "1") (pinfunction "1_1") (pintype "passive"))
      (node (ref "R29") (pin "2") (pinfunction "2_2") (pintype "passive"))
      (node (ref "U6") (pin "22") (pinfunction "SRB_22") (pintype "input"))
    )
    (net (code "261") (name "Net-(U6-VHS)") (class "Default")
      (node (ref "C25") (pin "2") (pinfunction "2_2") (pintype "passive"))
      (node (ref "U6") (pin "35") (pinfunction "VHS_35") (pintype "input"))
    )
    (net (code "262") (name "Net-(U7-5VOUT)") (class "Default")
      (node (ref "C36") (pin "1") (pinfunction "1_1") (pintype "passive"))
      (node (ref "U7") (pin "13") (pinfunction "5VOUT_13") (pintype "output"))
    )
    (net (code "263") (name "Net-(U7-BRA)") (class "Default")
      (node (ref "R38") (pin "1") (pinfunction "1_1") (pintype "passive"))
      (node (ref "R46") (pin "2") (pinfunction "2_2") (pintype "passive"))
      (node (ref "U7") (pin "9") (pinfunction "BRA_9") (pintype "input"))
    )
    (net (code "264") (name "Net-(U7-BRB)") (class "Default")
      (node (ref "R39") (pin "1") (pinfunction "1_1") (pintype "passive"))
      (node (ref "R44") (pin "2") (pinfunction "2_2") (pintype "passive"))
      (node (ref "U7") (pin "25") (pinfunction "BRB_25") (pintype "input"))
    )
    (net (code "265") (name "Net-(U7-SRA)") (class "Default")
      (node (ref "C38") (pin "1") (pinfunction "1_1") (pintype "passive"))
      (node (ref "R38") (pin "2") (pinfunction "2_2") (pintype "passive"))
      (node (ref "U7") (pin "12") (pinfunction "SRA_12") (pintype "input"))
    )
    (net (code "266") (name "Net-(U7-SRB)") (class "Default")
      (node (ref "C56") (pin "1") (pinfunction "1_1") (pintype "passive"))
      (node (ref "R39") (pin "2") (pinfunction "2_2") (pintype "passive"))
      (node (ref "U7") (pin "22") (pinfunction "SRB_22") (pintype "input"))
    )
    (net (code "267") (name "Net-(U7-VHS)") (class "Default")
      (node (ref "C34") (pin "2") (pinfunction "2_2") (pintype "passive"))
      (node (ref "U7") (pin "35") (pinfunction "VHS_35") (pintype "input"))
    )
    (net (code "268") (name "Net-(U8-5VOUT)") (class "Default")
      (node (ref "C37") (pin "1") (pinfunction "1_1") (pintype "passive"))
      (node (ref "U8") (pin "13") (pinfunction "5VOUT_13") (pintype "output"))
    )
    (net (code "269") (name "Net-(U8-BRA)") (class "Default")
      (node (ref "R40") (pin "1") (pinfunction "1_1") (pintype "passive"))
      (node (ref "R47") (pin "2") (pinfunction "2_2") (pintype "passive"))
      (node (ref "U8") (pin "9") (pinfunction "BRA_9") (pintype "input"))
    )
    (net (code "270") (name "Net-(U8-BRB)") (class "Default")
      (node (ref "R41") (pin "1") (pinfunction "1_1") (pintype "passive"))
      (node (ref "R45") (pin "2") (pinfunction "2_2") (pintype "passive"))
      (node (ref "U8") (pin "25") (pinfunction "BRB_25") (pintype "input"))
    )
    (net (code "271") (name "Net-(U8-SRA)") (class "Default")
      (node (ref "C39") (pin "1") (pinfunction "1_1") (pintype "passive"))
      (node (ref "R40") (pin "2") (pinfunction "2_2") (pintype "passive"))
      (node (ref "U8") (pin "12") (pinfunction "SRA_12") (pintype "input"))
    )
    (net (code "272") (name "Net-(U8-SRB)") (class "Default")
      (node (ref "C57") (pin "1") (pinfunction "1_1") (pintype "passive"))
      (node (ref "R41") (pin "2") (pinfunction "2_2") (pintype "passive"))
      (node (ref "U8") (pin "22") (pinfunction "SRB_22") (pintype "input"))
    )
    (net (code "273") (name "Net-(U8-VHS)") (class "Default")
      (node (ref "C35") (pin "2") (pinfunction "2_2") (pintype "passive"))
      (node (ref "U8") (pin "35") (pinfunction "VHS_35") (pintype "input"))
    )
    (net (code "274") (name "Net-(U9-5VOUT)") (class "Default")
      (node (ref "C104") (pin "1") (pinfunction "1_1") (pintype "passive"))
      (node (ref "U9") (pin "13") (pinfunction "5VOUT_13") (pintype "output"))
    )
    (net (code "275") (name "Net-(U9-BRA)") (class "Default")
      (node (ref "R89") (pin "1") (pinfunction "1_1") (pintype "passive"))
      (node (ref "R94") (pin "2") (pinfunction "2_2") (pintype "passive"))
      (node (ref "U9") (pin "9") (pinfunction "BRA_9") (pintype "input"))
    )
    (net (code "276") (name "Net-(U9-BRB)") (class "Default")
      (node (ref "R90") (pin "1") (pinfunction "1_1") (pintype "passive"))
      (node (ref "R93") (pin "2") (pinfunction "2_2") (pintype "passive"))
      (node (ref "U9") (pin "25") (pinfunction "BRB_25") (pintype "input"))
    )
    (net (code "277") (name "Net-(U9-SRA)") (class "Default")
      (node (ref "C105") (pin "1") (pinfunction "1_1") (pintype "passive"))
      (node (ref "R89") (pin "2") (pinfunction "2_2") (pintype "passive"))
      (node (ref "U9") (pin "12") (pinfunction "SRA_12") (pintype "input"))
    )
    (net (code "278") (name "Net-(U9-SRB)") (class "Default")
      (node (ref "C110") (pin "1") (pinfunction "1_1") (pintype "passive"))
      (node (ref "R90") (pin "2") (pinfunction "2_2") (pintype "passive"))
      (node (ref "U9") (pin "22") (pinfunction "SRB_22") (pintype "input"))
    )
    (net (code "279") (name "Net-(U9-VHS)") (class "Default")
      (node (ref "C103") (pin "2") (pinfunction "2_2") (pintype "passive"))
      (node (ref "U9") (pin "35") (pinfunction "VHS_35") (pintype "input"))
    )
    (net (code "280") (name "Net-(U11A-O)") (class "Default")
      (node (ref "U11") (pin "1") (pinfunction "O_1") (pintype "output"))
      (node (ref "U11") (pin "12") (pinfunction "I1_12") (pintype "input"))
      (node (ref "U11") (pin "6") (pinfunction "I1_6") (pintype "input"))
      (node (ref "U11") (pin "9") (pinfunction "I1_9") (pintype "input"))
    )
    (net (code "281") (name "Net-(U13A-O)") (class "Default")
      (node (ref "U13") (pin "10") (pinfunction "I1_10") (pintype "input"))
      (node (ref "U13") (pin "3") (pinfunction "O_3") (pintype "output"))
    )
    (net (code "282") (name "Net-(U13B-O)") (class "Default")
      (node (ref "U13") (pin "12") (pinfunction "I0_12") (pintype "input"))
      (node (ref "U13") (pin "6") (pinfunction "O_6") (pintype "output"))
    )
    (net (code "283") (name "Net-(U13C-O)") (class "Default")
      (node (ref "U13") (pin "13") (pinfunction "I1_13") (pintype "input"))
      (node (ref "U13") (pin "8") (pinfunction "O_8") (pintype "output"))
    )
    (net (code "284") (name "PWR_FAIL_DET1") (class "Default")
      (node (ref "C80") (pin "1") (pinfunction "1_1") (pintype "passive"))
      (node (ref "R15") (pin "1") (pinfunction "1_1") (pintype "passive"))
      (node (ref "R16") (pin "2") (pinfunction "2_2") (pintype "passive"))
      (node (ref "U1") (pin "31") (pinfunction "PB3/AFE1_AD1_31") (pintype "bidirectional"))
    )
    (net (code "285") (name "PWR_FAIL_DET2") (class "Default")
      (node (ref "C79") (pin "1") (pinfunction "1_1") (pintype "passive"))
      (node (ref "R80") (pin "1") (pinfunction "1_1") (pintype "passive"))
      (node (ref "R81") (pin "2") (pinfunction "2_2") (pintype "passive"))
      (node (ref "U1") (pin "41") (pinfunction "PC4/AFE1_AD7_41") (pintype "bidirectional"))
    )
    (net (code "286") (name "unconnected-(IC1A-~{Q}-Pad6)") (class "Default")
      (node (ref "IC1") (pin "6") (pinfunction "~{Q}_6") (pintype "output"))
    )
    (net (code "287") (name "unconnected-(IC1B-Q-Pad9)") (class "Default")
      (node (ref "IC1") (pin "9") (pinfunction "Q_9") (pintype "output"))
    )
    (net (code "288") (name "unconnected-(IC1B-~{Q}-Pad8)") (class "Default")
      (node (ref "IC1") (pin "8") (pinfunction "~{Q}_8") (pintype "output"))
    )
    (net (code "289") (name "unconnected-(J21-KEY-Pad7)") (class "Default")
      (node (ref "J21") (pin "7") (pinfunction "KEY_7") (pintype "bidirectional"))
    )
    (net (code "290") (name "unconnected-(J22-PadID)") (class "Default")
      (node (ref "J22") (pin "ID") (pinfunction "ID_ID") (pintype "bidirectional"))
    )
    (net (code "291") (name "unconnected-(J37B-S-Pad10)") (class "Default")
      (node (ref "J37") (pin "10") (pinfunction "S_10") (pintype "passive"))
    )
    (net (code "292") (name "unconnected-(U5-TST_ANA-Pad37)") (class "Default")
      (node (ref "U5") (pin "37") (pinfunction "TST_ANA_37") (pintype "output"))
    )
    (net (code "293") (name "unconnected-(U6-TST_ANA-Pad37)") (class "Default")
      (node (ref "U6") (pin "37") (pinfunction "TST_ANA_37") (pintype "output"))
    )
    (net (code "294") (name "unconnected-(U7-TST_ANA-Pad37)") (class "Default")
      (node (ref "U7") (pin "37") (pinfunction "TST_ANA_37") (pintype "output"))
    )
    (net (code "295") (name "unconnected-(U8-TST_ANA-Pad37)") (class "Default")
      (node (ref "U8") (pin "37") (pinfunction "TST_ANA_37") (pintype "output"))
    )
    (net (code "296") (name "unconnected-(U9-TST_ANA-Pad37)") (class "Default")
      (node (ref "U9") (pin "37") (pinfunction "TST_ANA_37") (pintype "output"))
    )
    (net (code "297") (name "unconnected-(U10D-O-Pad11)") (class "Default")
      (node (ref "U10") (pin "11") (pinfunction "O_11") (pintype "tri_state"))
    )
    (net (code "298") (name "unconnected-(U13D-O-Pad11)") (class "Default")
      (node (ref "U13") (pin "11") (pinfunction "O_11") (pintype "output"))
    )
  )
)
